# ActuatorBoard.net
KiCad netlist of a schematic drawn in EAGLE
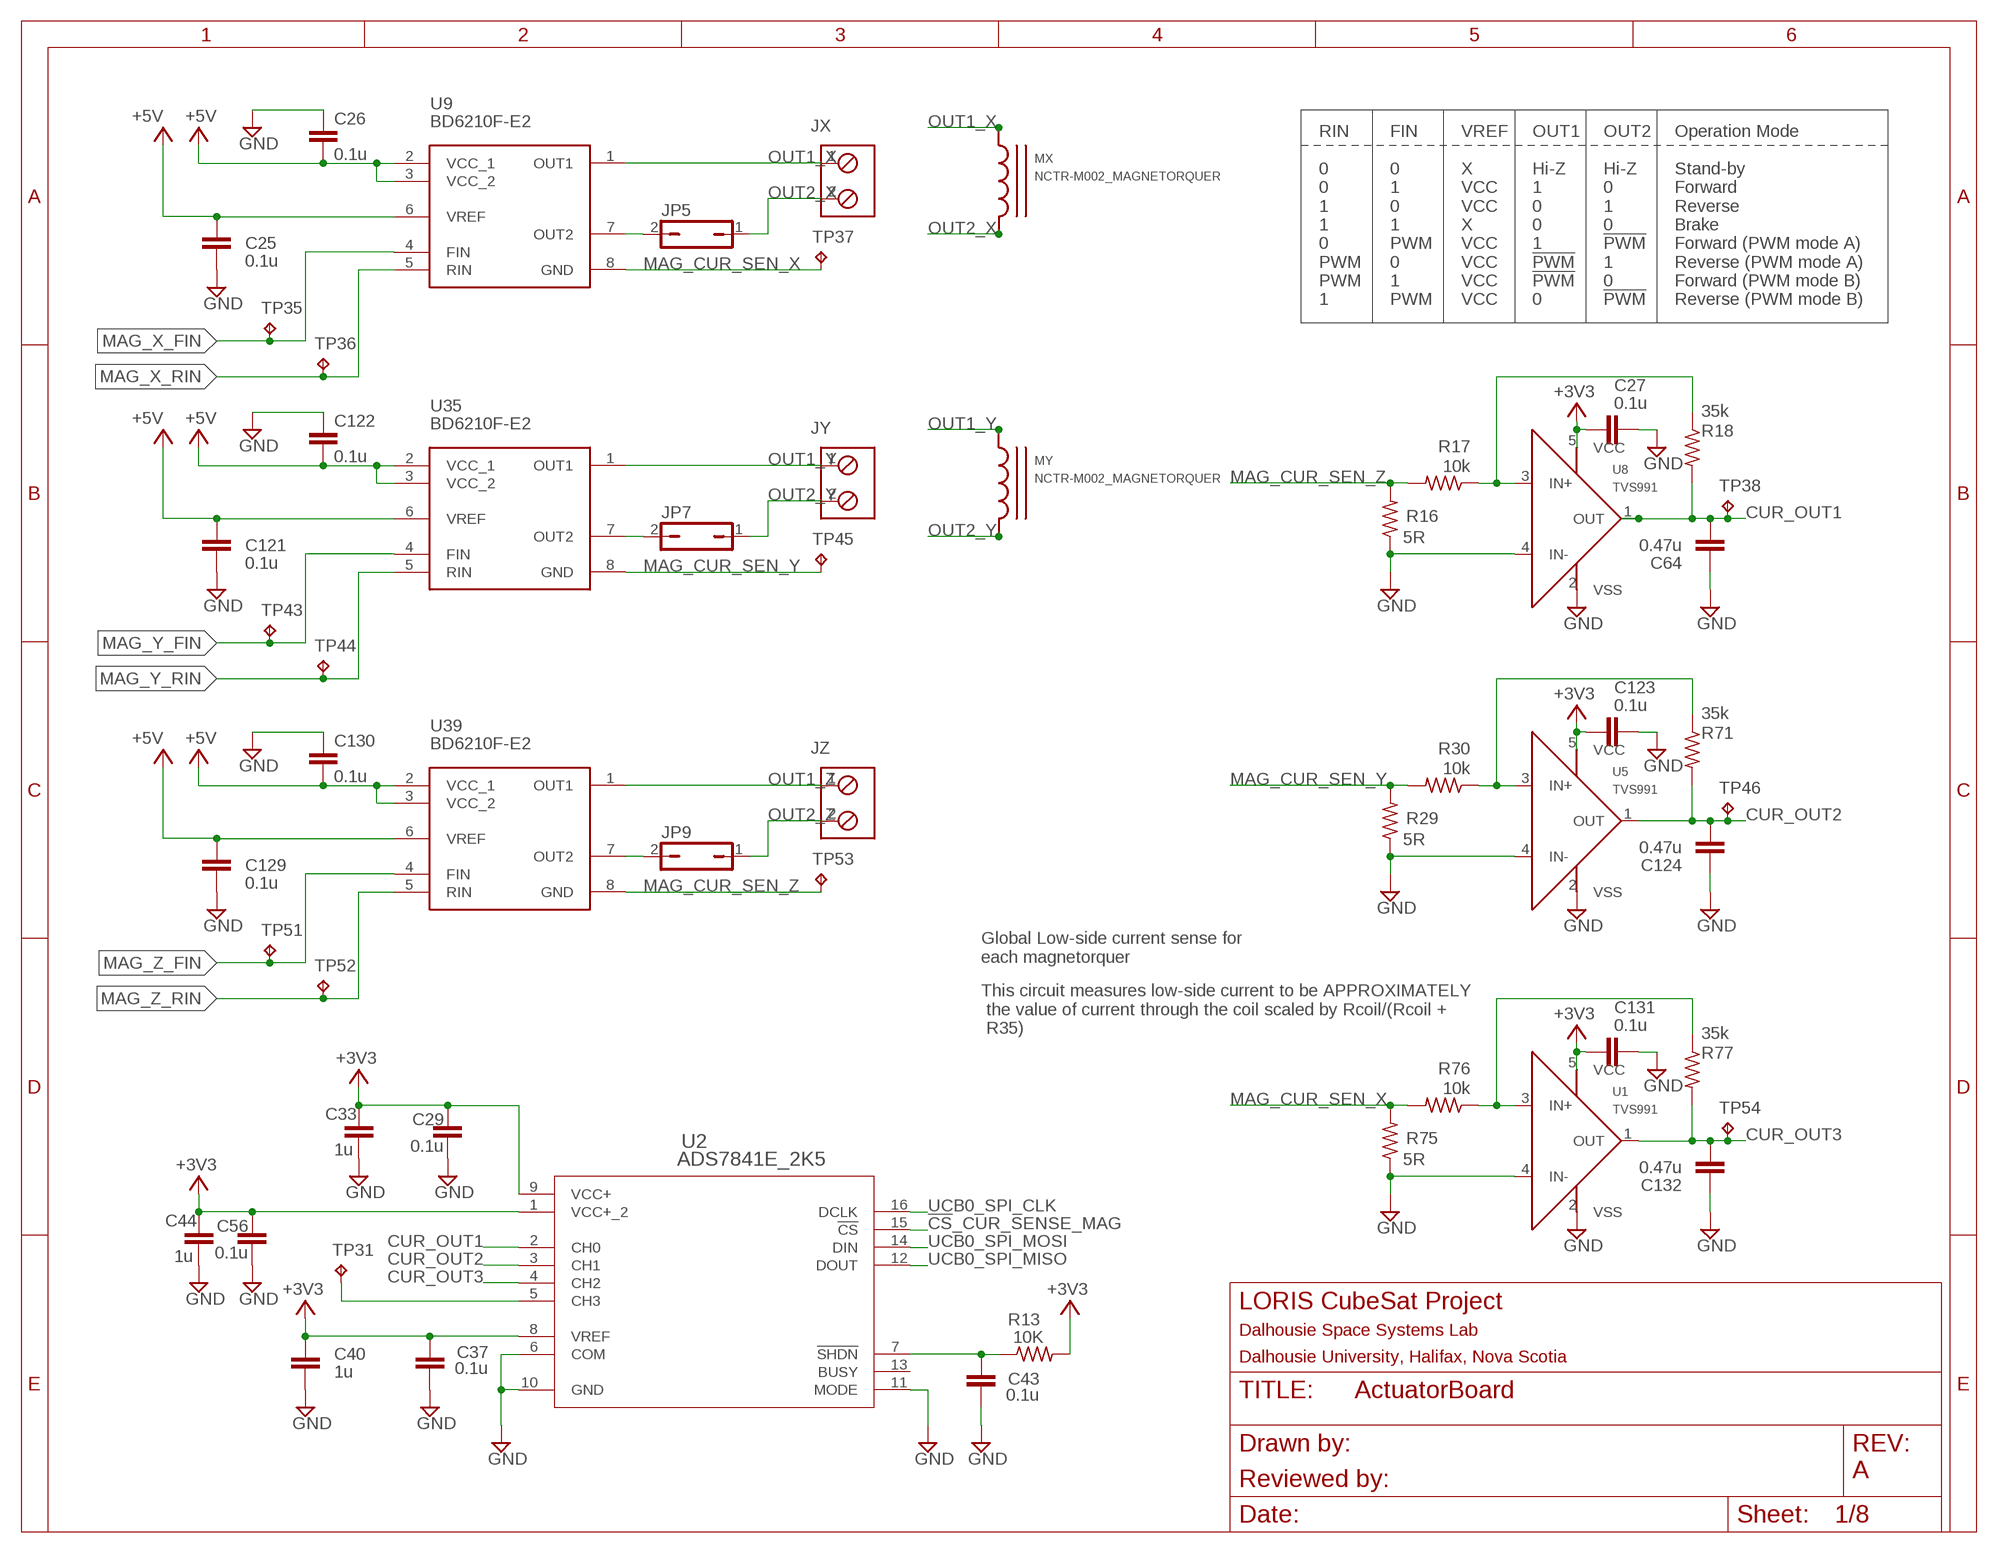
[diagram p0: schematic, sheet 1]
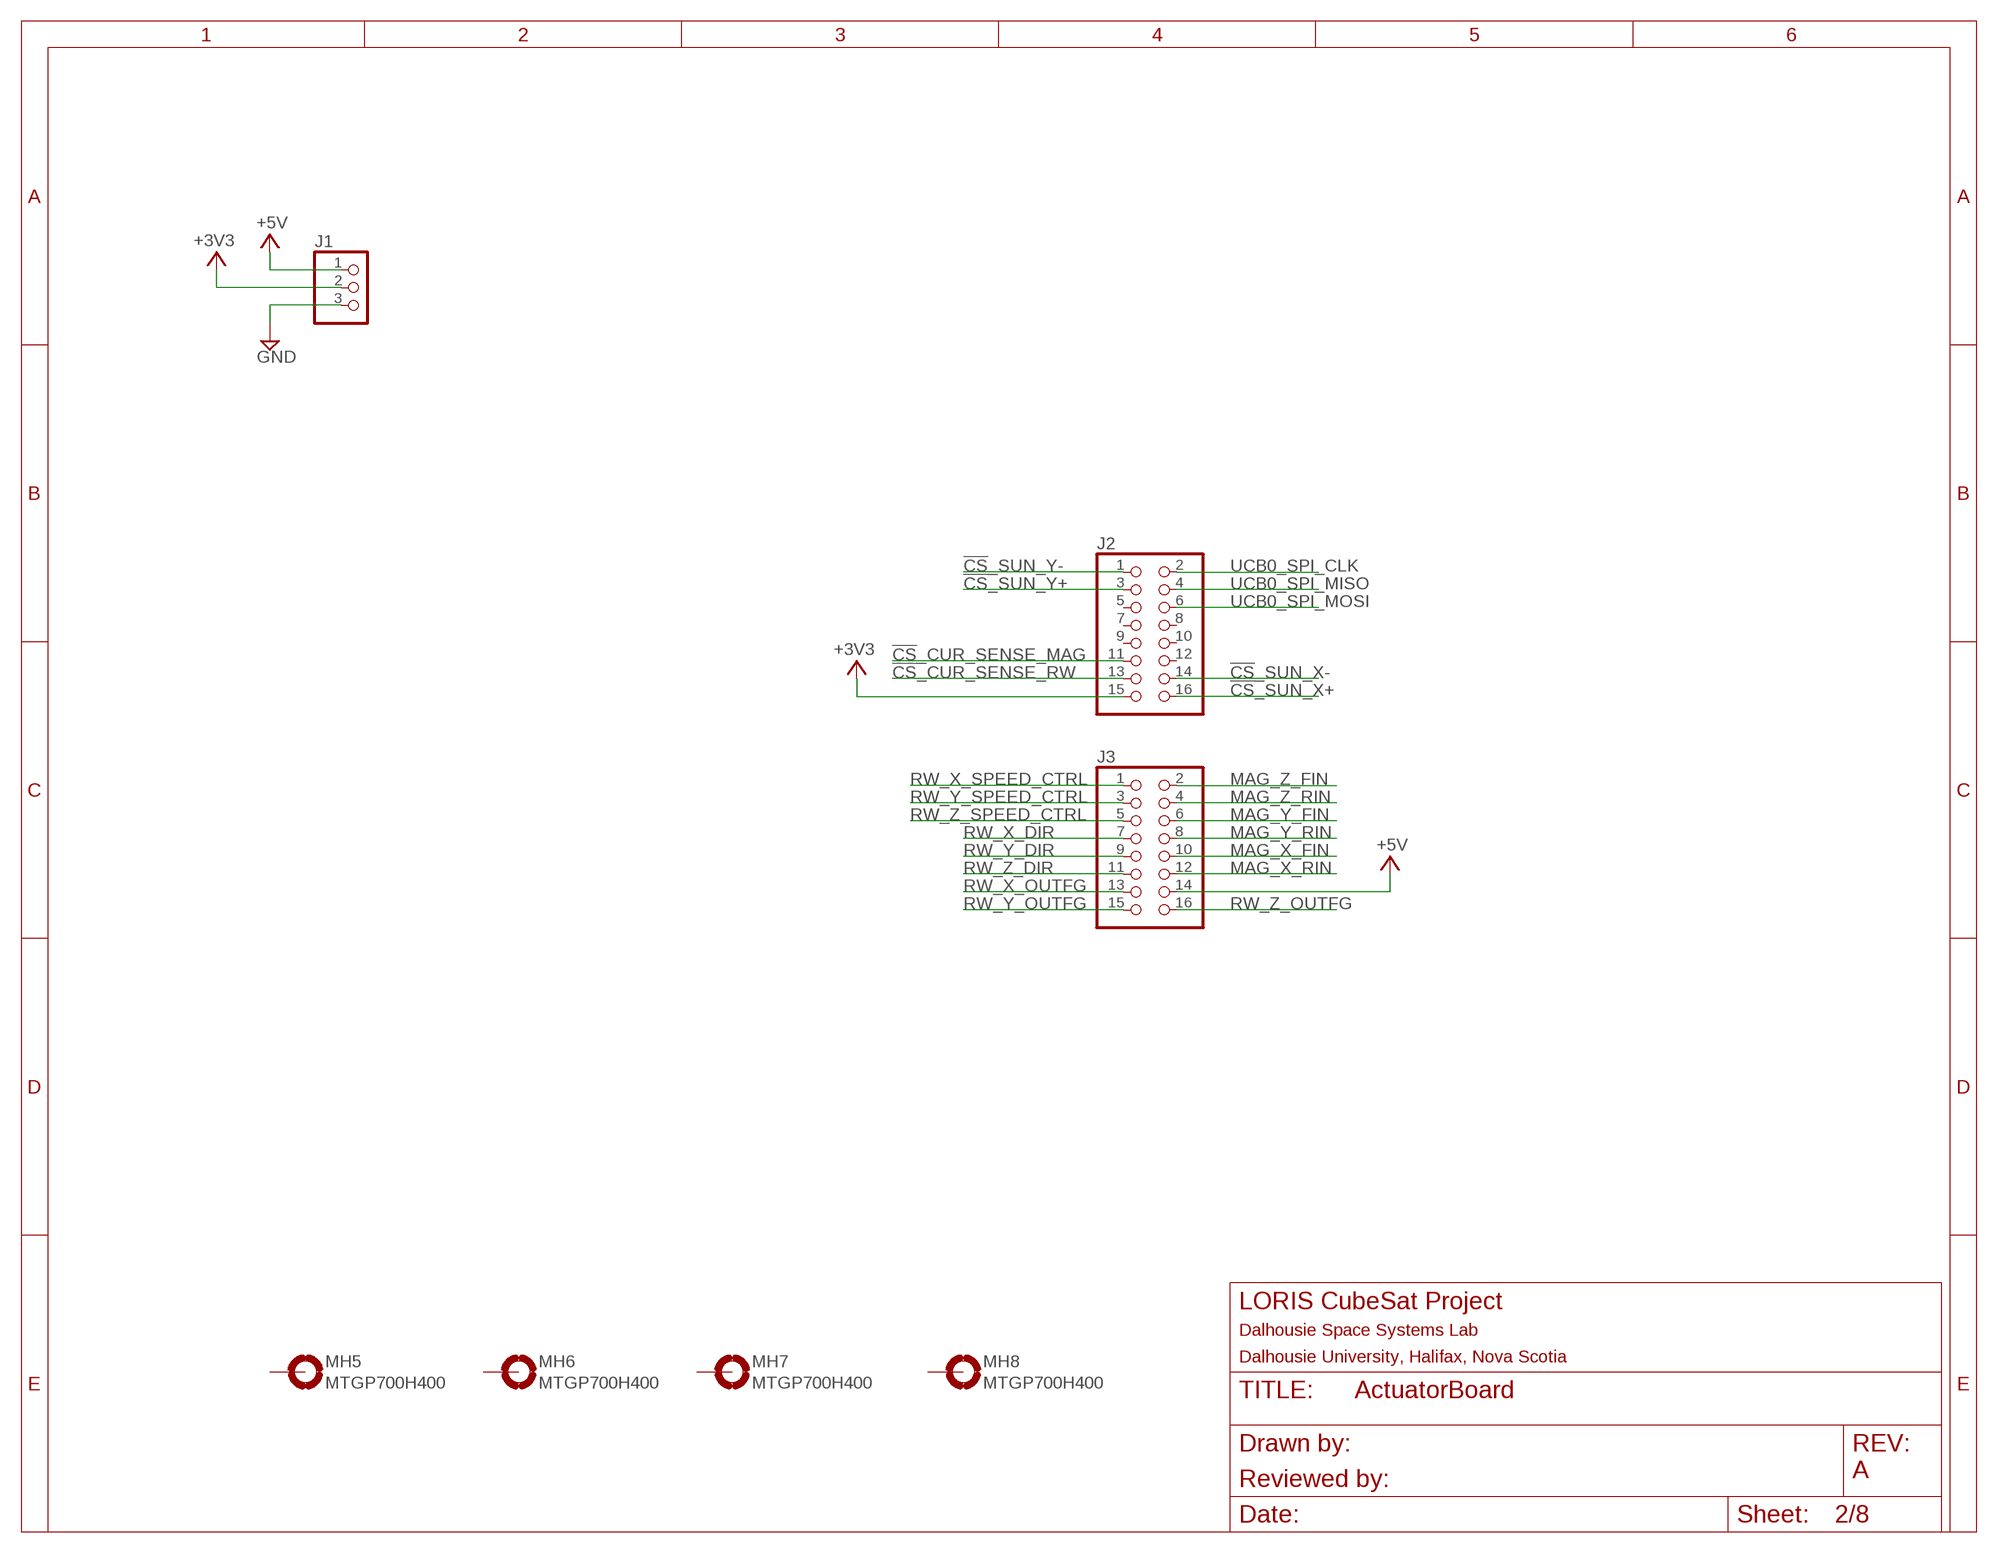
[diagram p1: schematic, sheet 2]
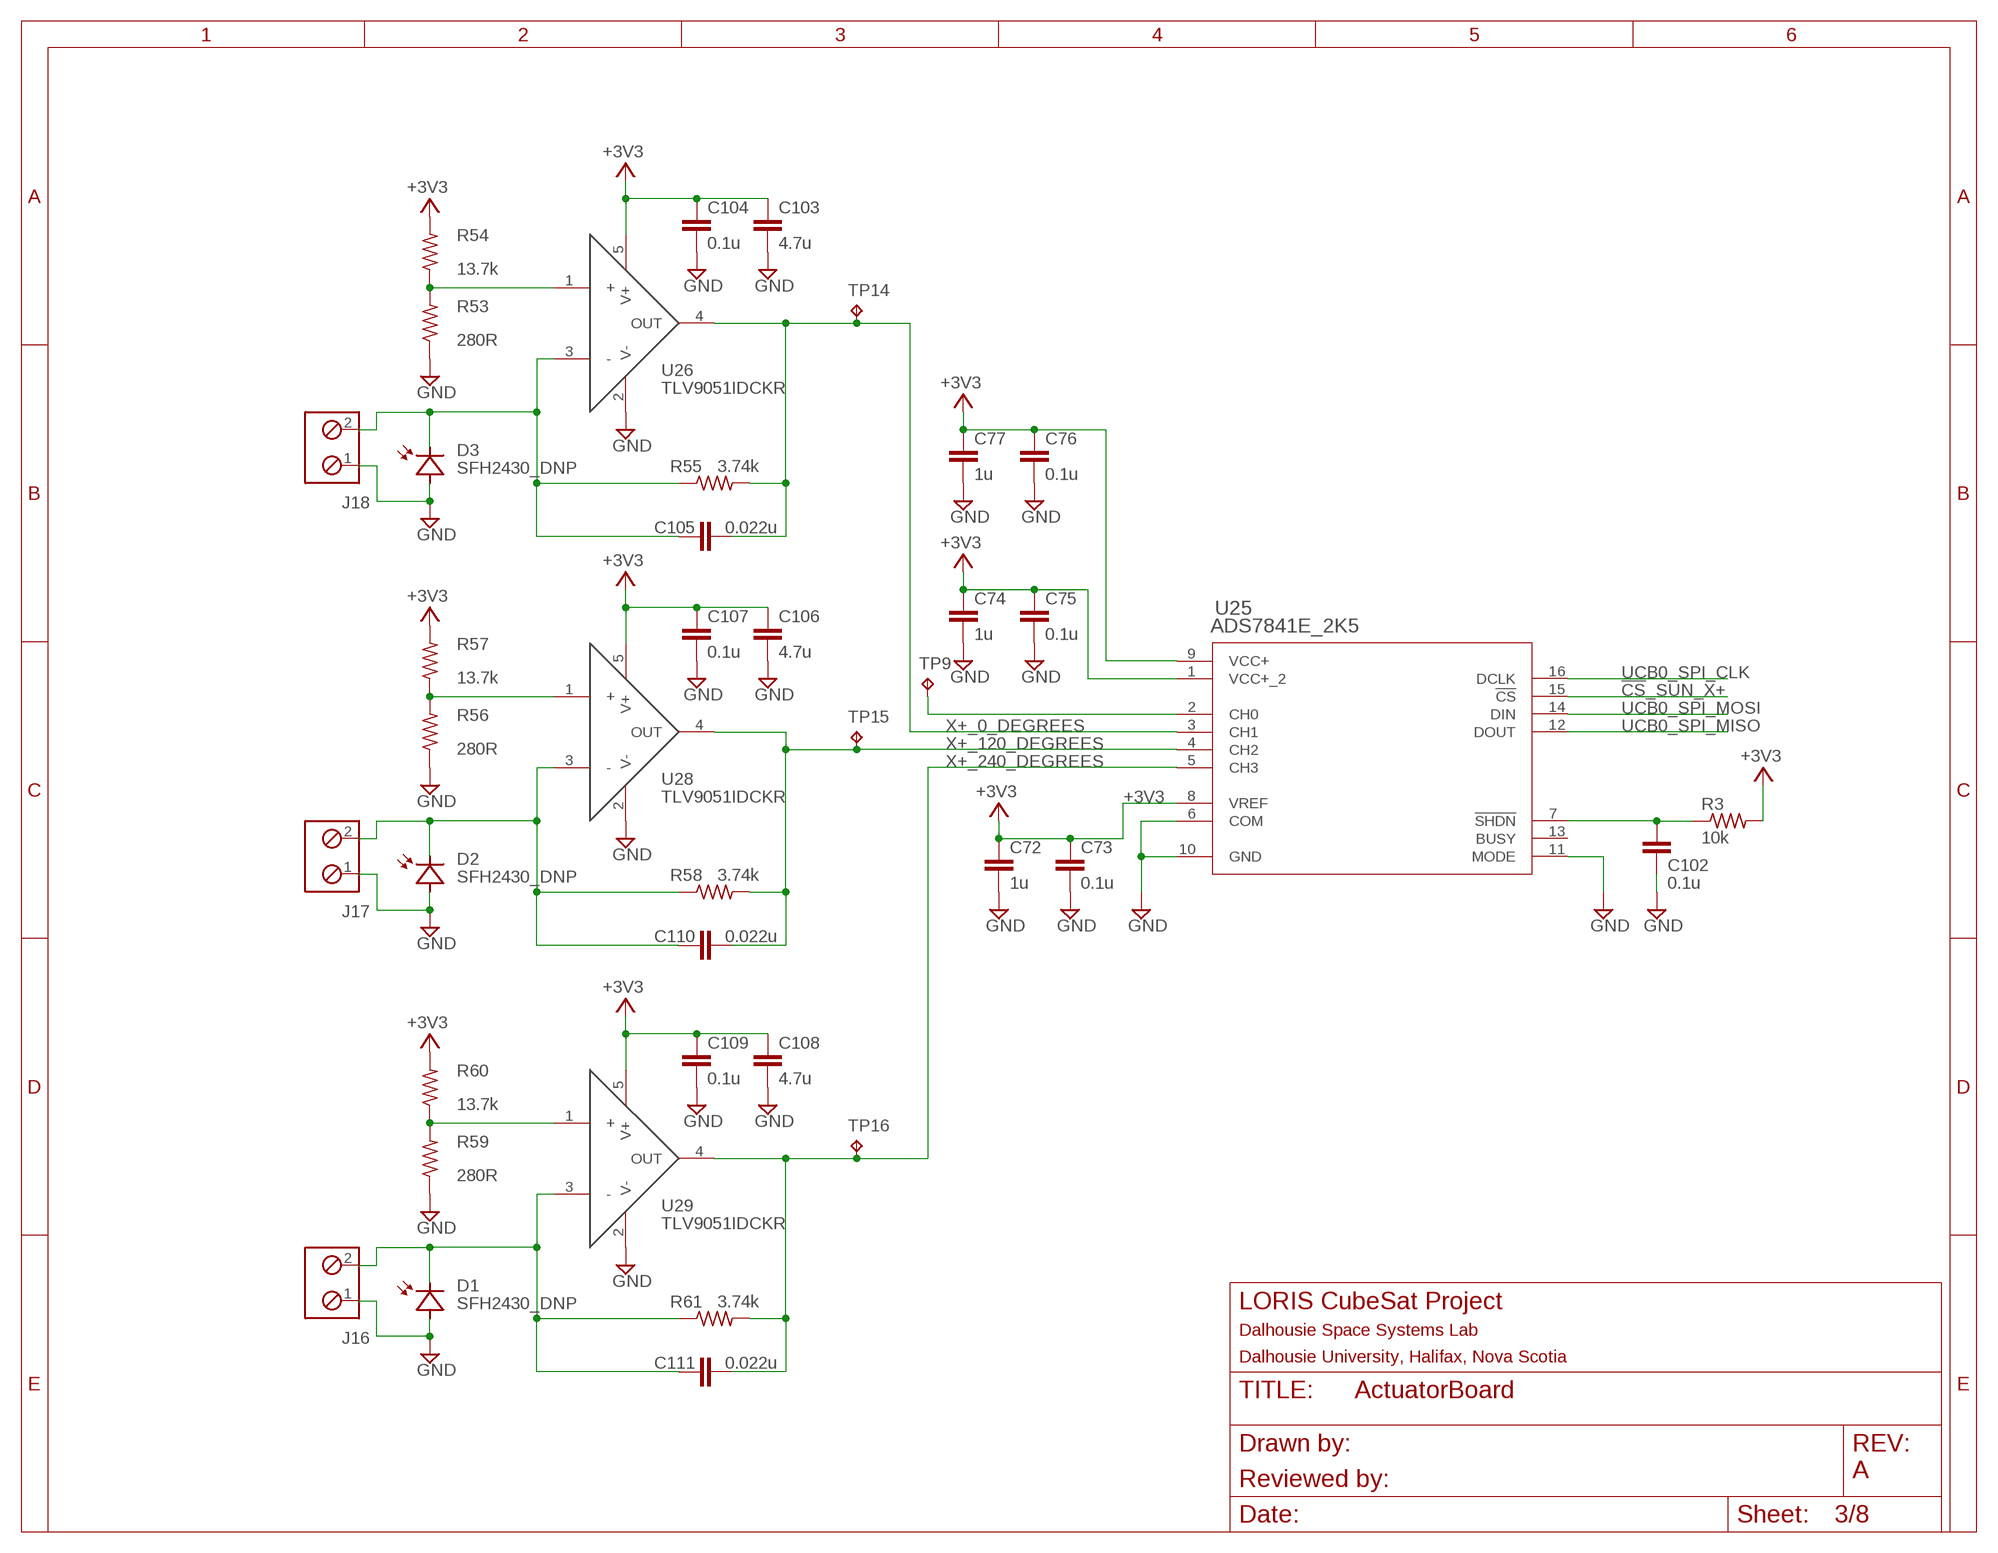
[diagram p2: schematic, sheet 3]
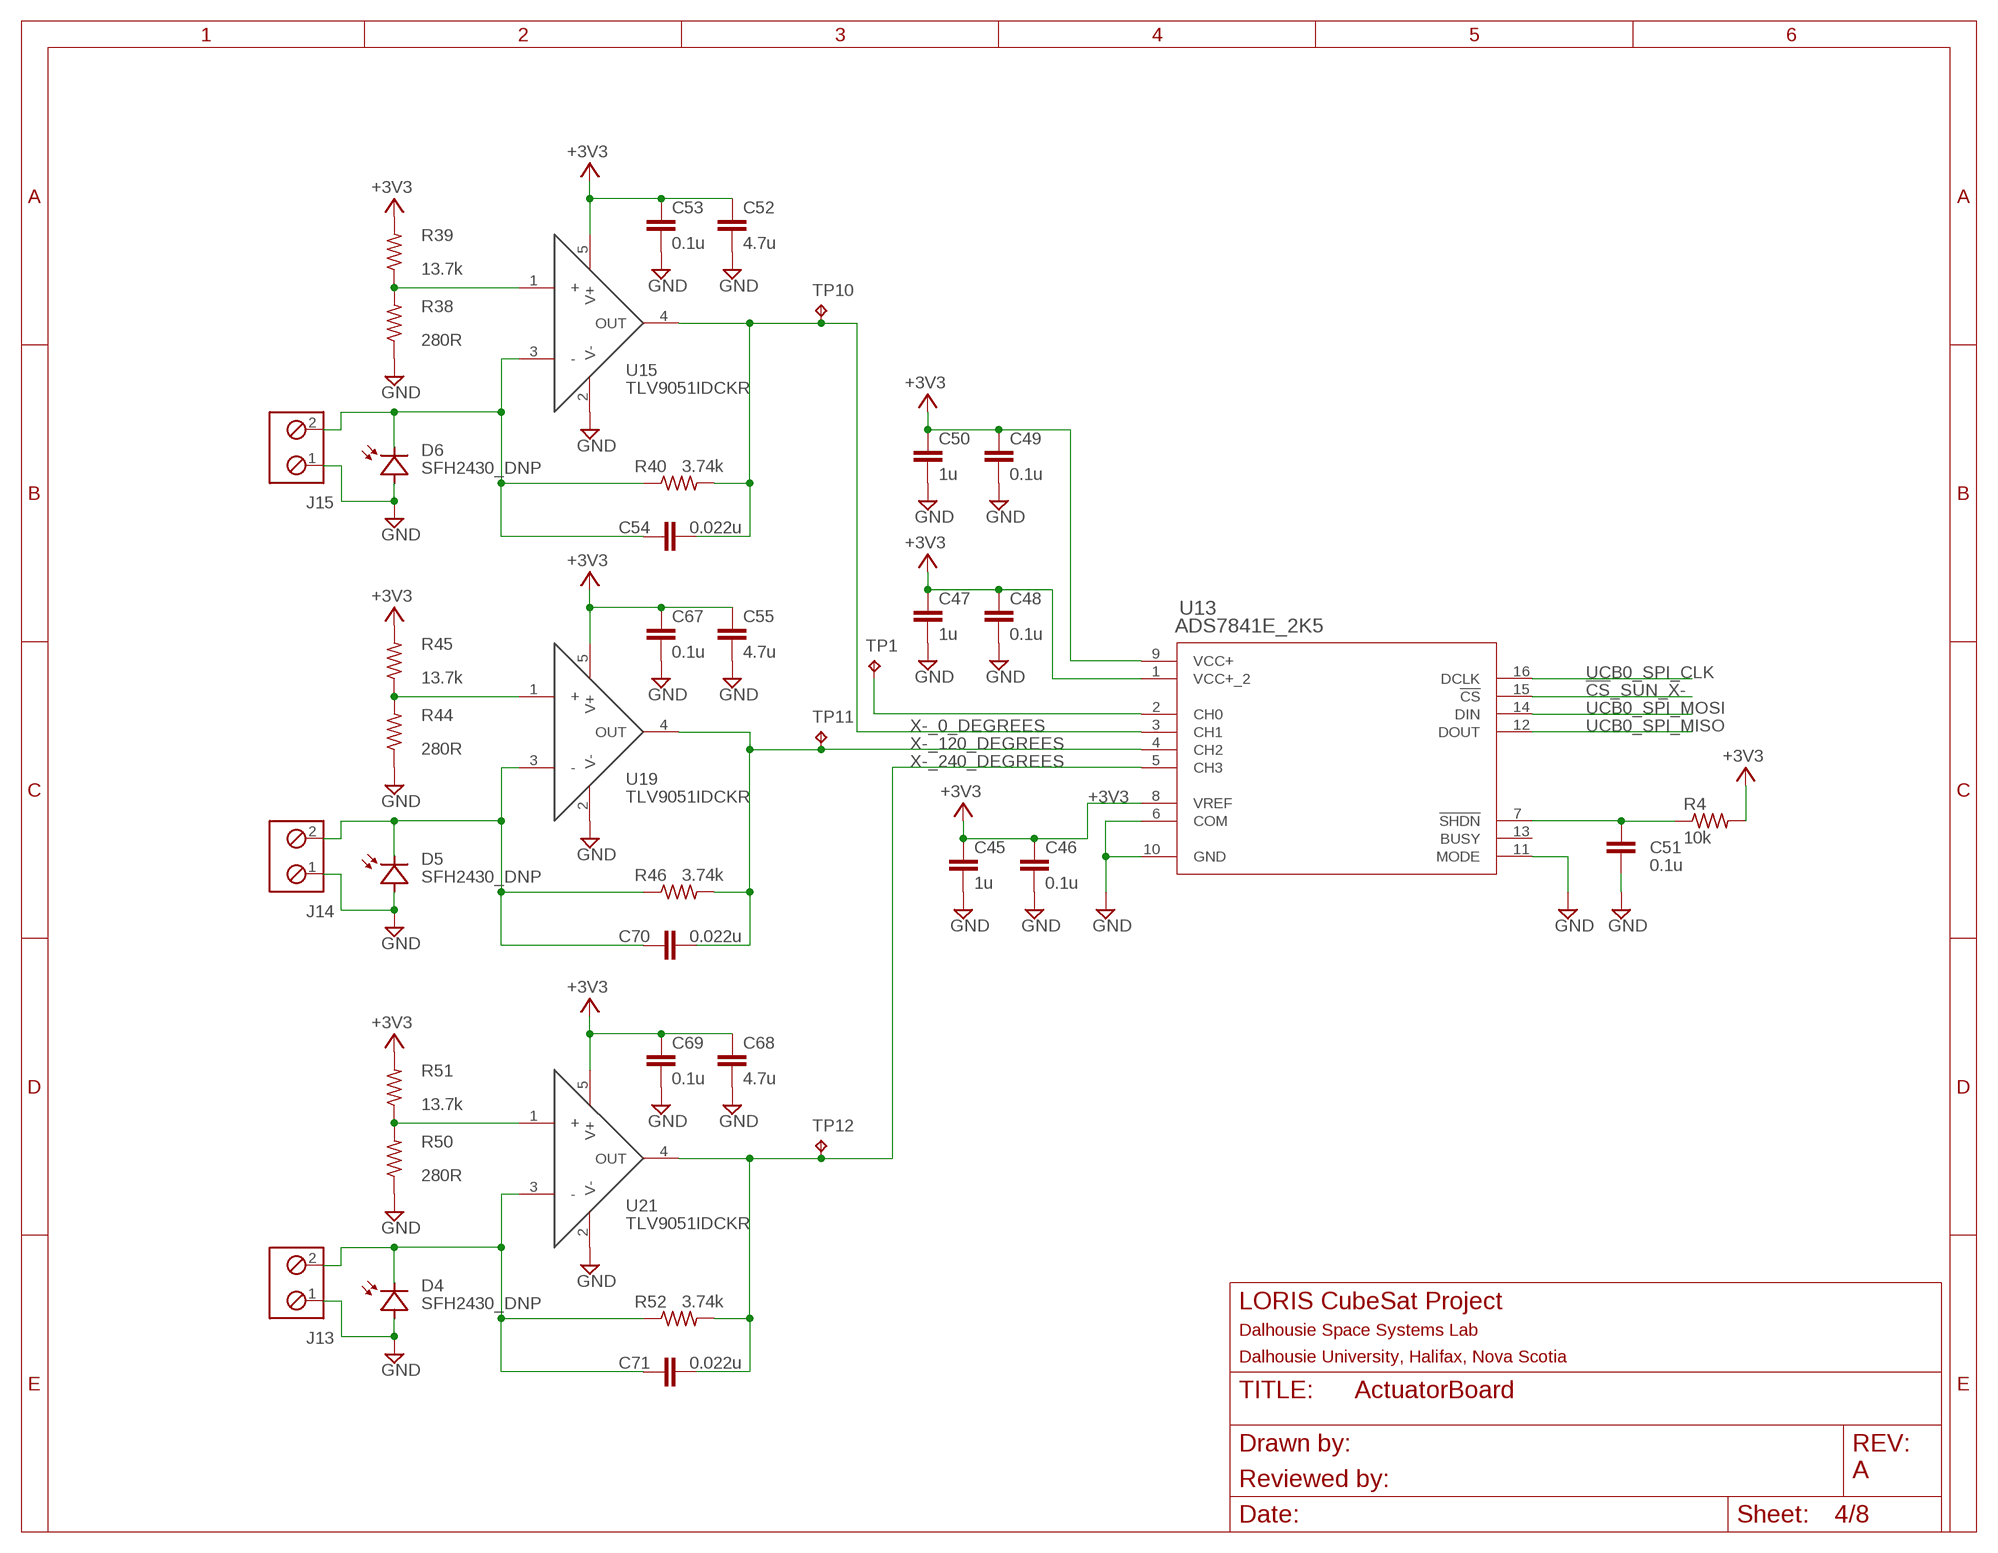
[diagram p3: schematic, sheet 4]
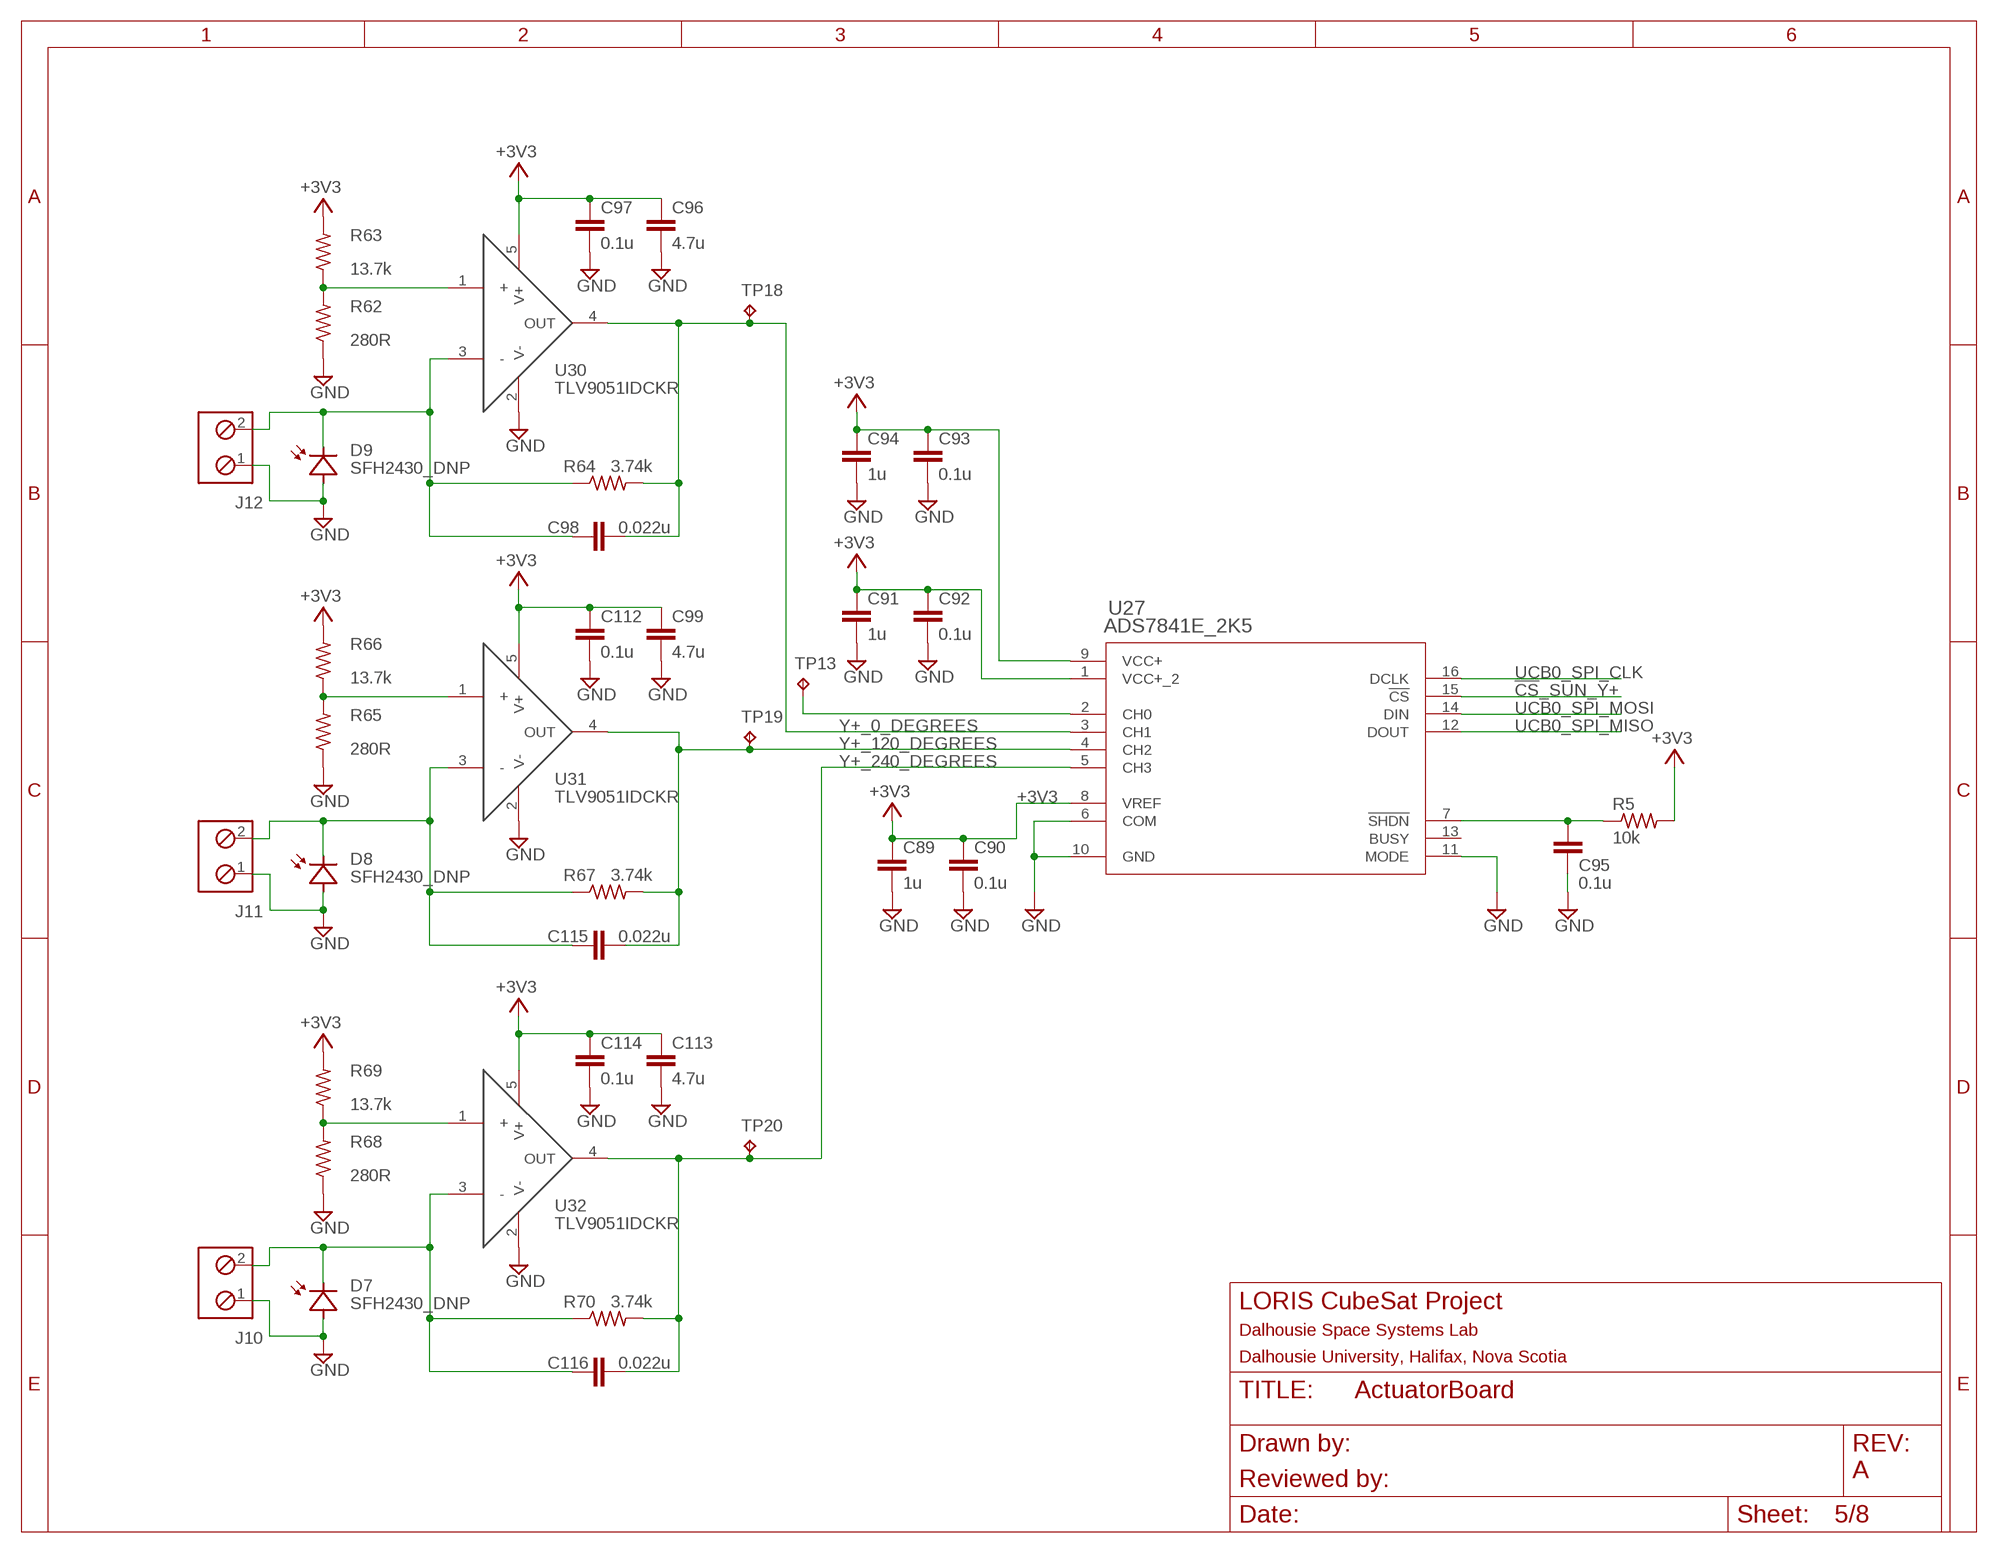
[diagram p4: schematic, sheet 5]
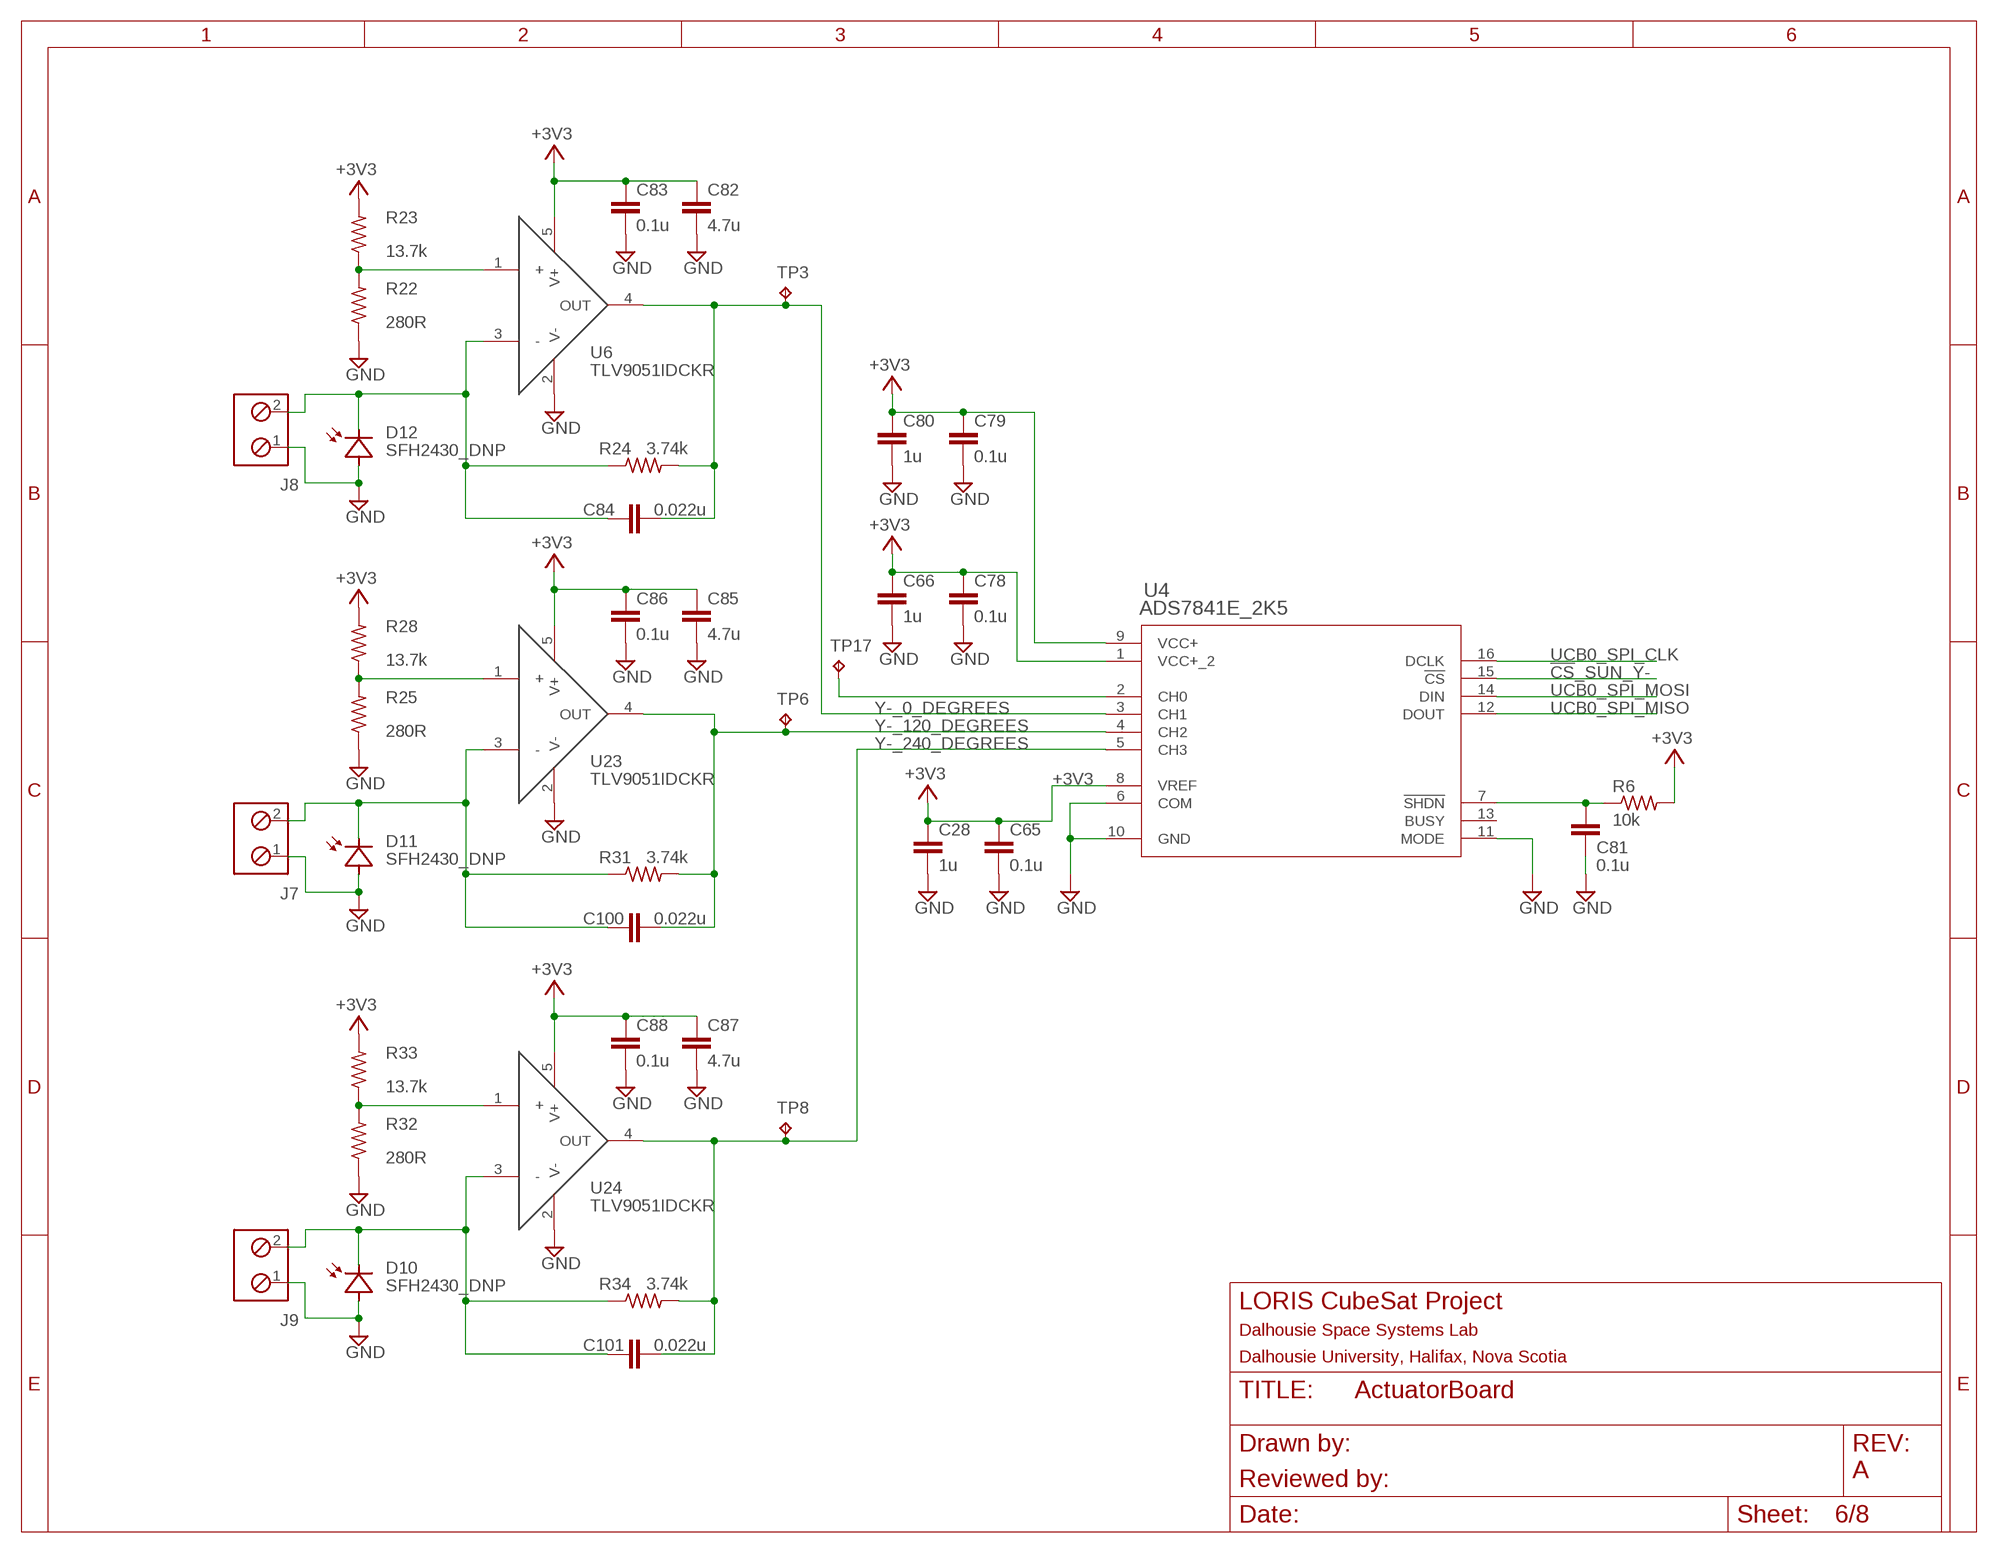
[diagram p5: schematic, sheet 6]
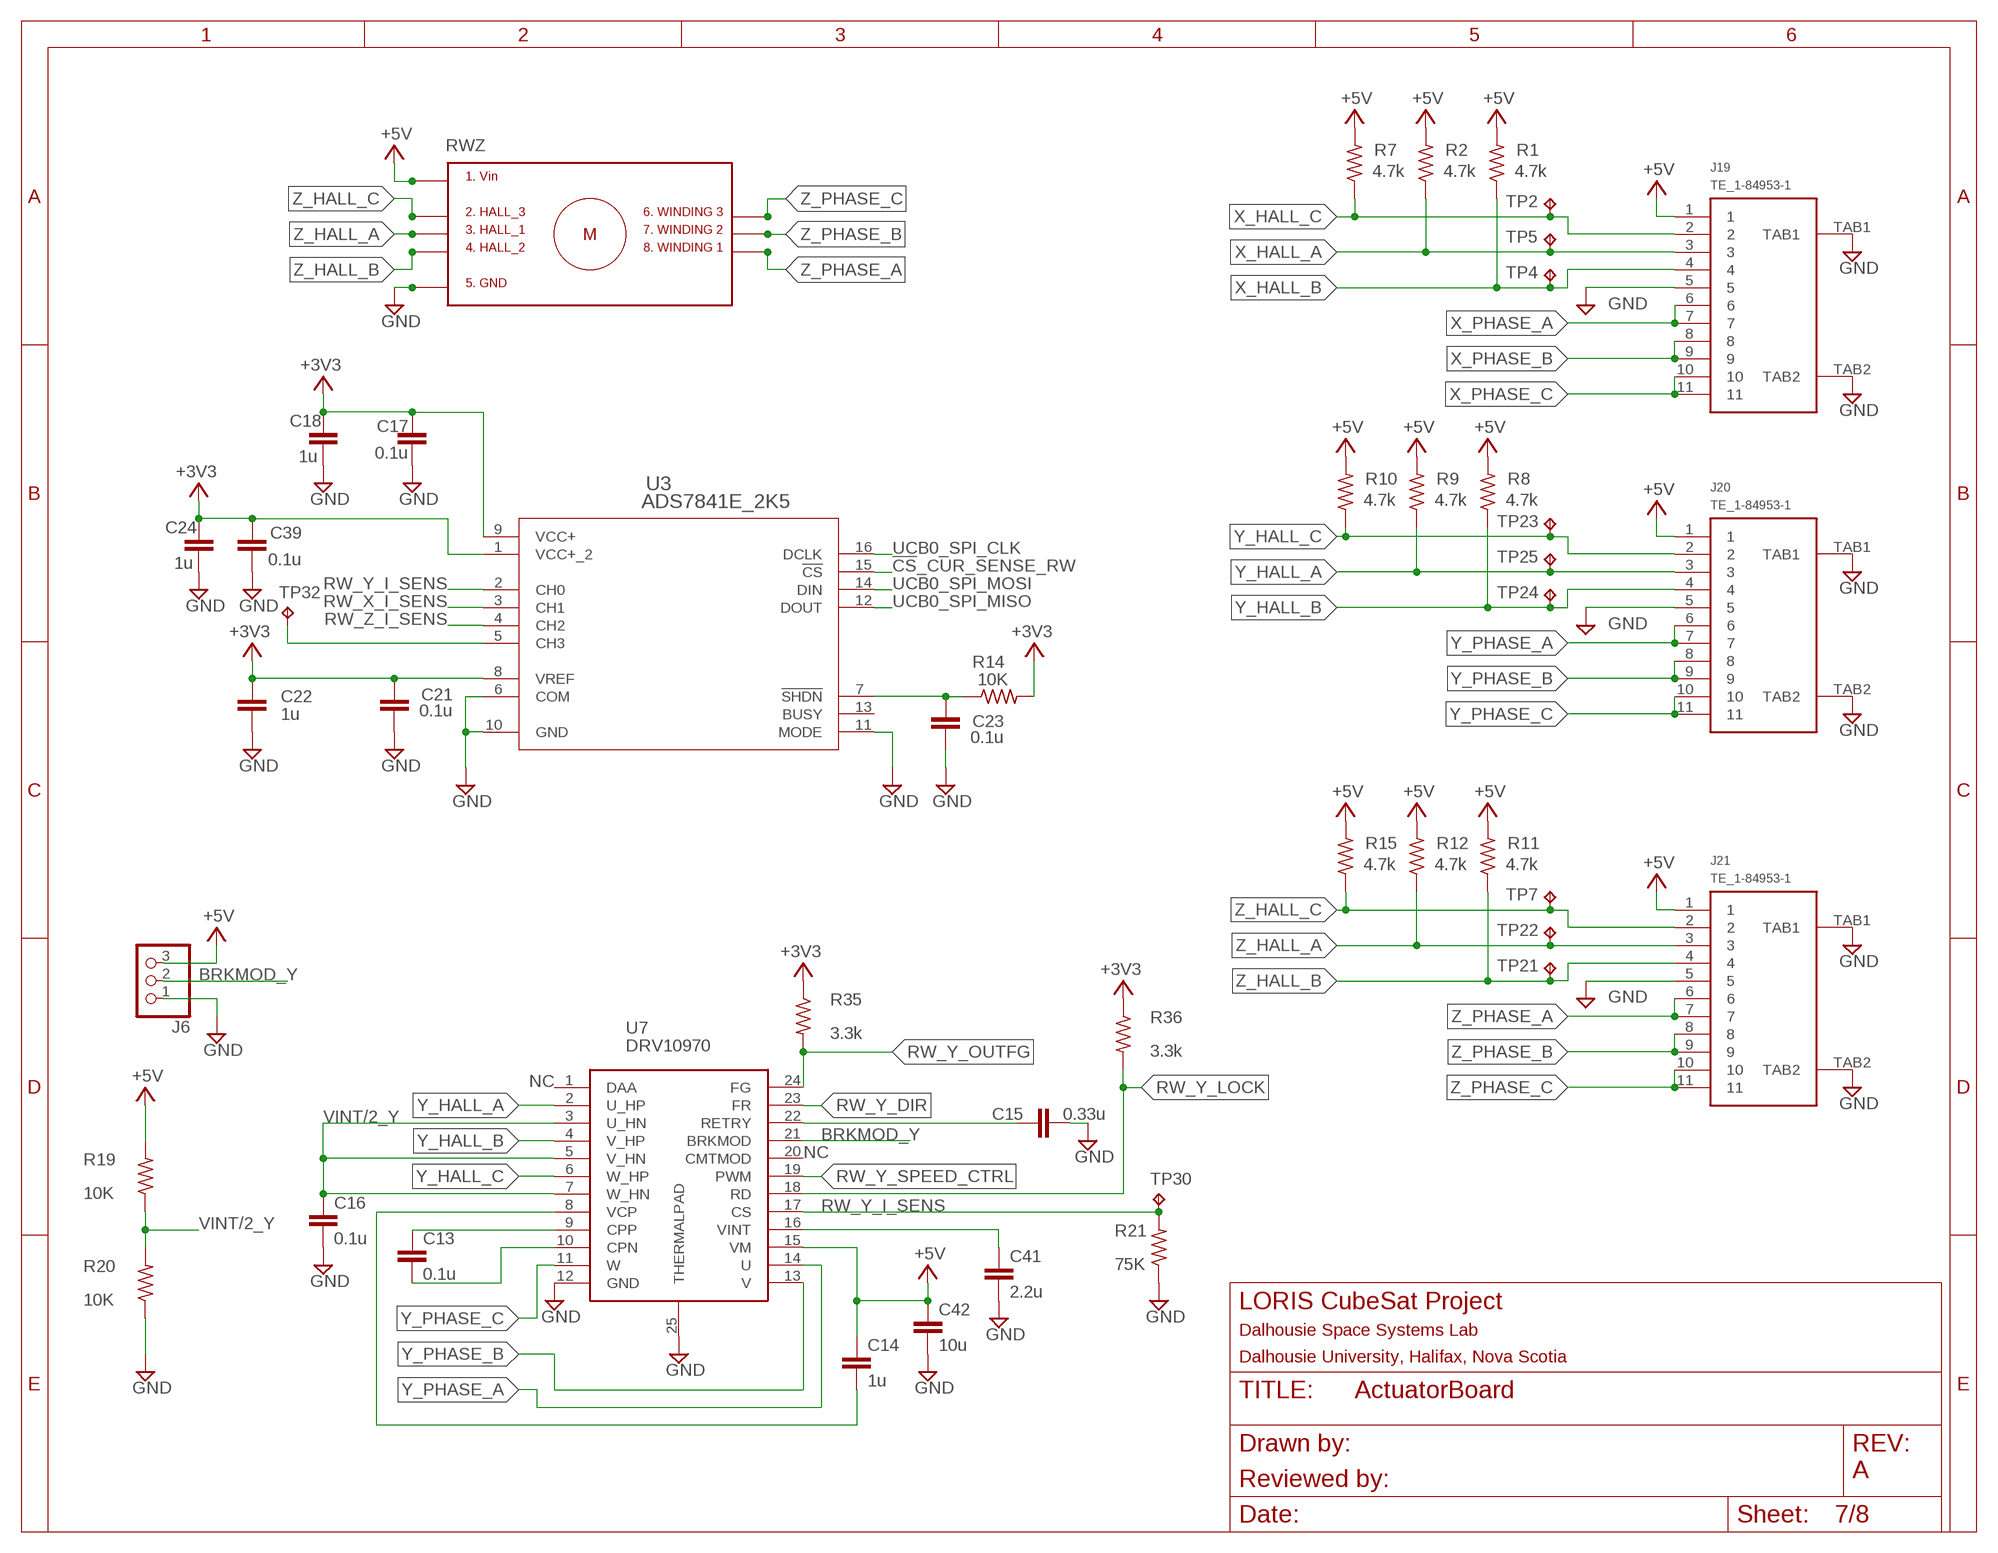
[diagram p6: schematic, sheet 7]
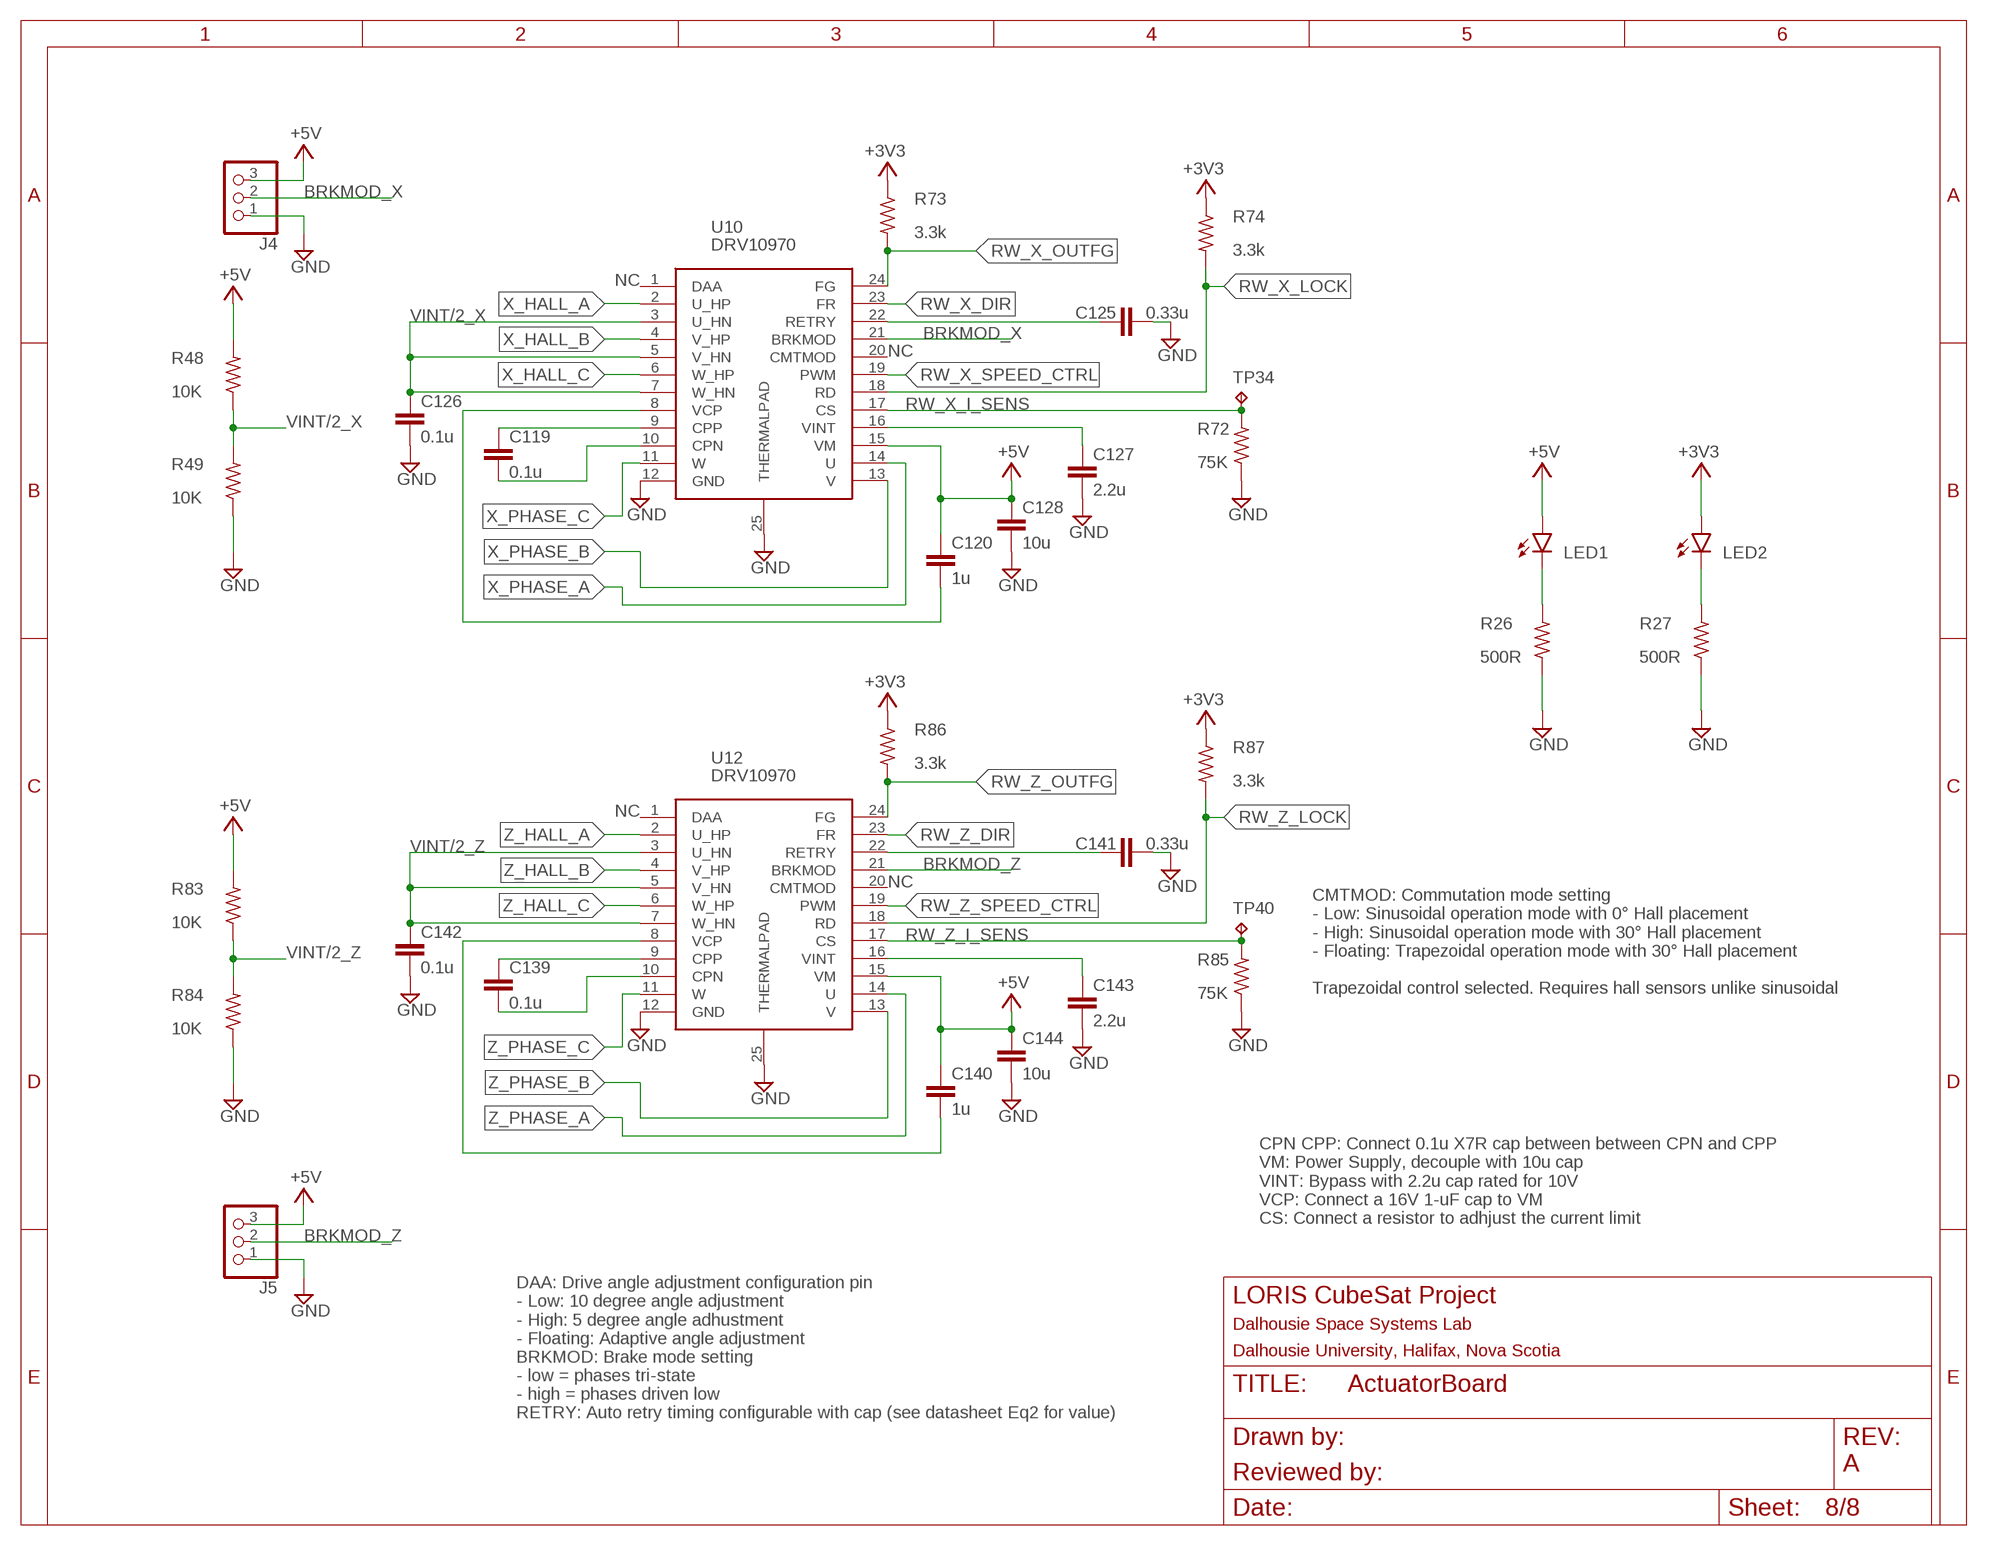
[diagram p7: schematic, sheet 8]

(export (version "E")
  (design (tool "Eeschema 10.0.6"))
  (components
    (comp (ref "C45")
      (value "1u")
      (footprint "eagle-import:C0402")
      (libsource (lib "eagle-import") (part "resistor_348_C-EUC0402"))
    )
    (comp (ref "C46")
      (value "0.1u")
      (footprint "eagle-import:C0402")
      (libsource (lib "eagle-import") (part "resistor_348_C-EUC0402"))
    )
    (comp (ref "C47")
      (value "1u")
      (footprint "eagle-import:C0402")
      (libsource (lib "eagle-import") (part "resistor_348_C-EUC0402"))
    )
    (comp (ref "C48")
      (value "0.1u")
      (footprint "eagle-import:C0402")
      (libsource (lib "eagle-import") (part "resistor_348_C-EUC0402"))
    )
    (comp (ref "C49")
      (value "0.1u")
      (footprint "eagle-import:C0402")
      (libsource (lib "eagle-import") (part "resistor_348_C-EUC0402"))
    )
    (comp (ref "C50")
      (value "1u")
      (footprint "eagle-import:C0402")
      (libsource (lib "eagle-import") (part "resistor_348_C-EUC0402"))
    )
    (comp (ref "C51")
      (value "0.1u")
      (footprint "eagle-import:C0402")
      (libsource (lib "eagle-import") (part "resistor_348_C-EUC0402"))
    )
    (comp (ref "C52")
      (value "4.7u")
      (footprint "eagle-import:C0402")
      (libsource (lib "eagle-import") (part "resistor_348_C-EUC0402"))
    )
    (comp (ref "C53")
      (value "0.1u")
      (footprint "eagle-import:C0402")
      (libsource (lib "eagle-import") (part "resistor_348_C-EUC0402"))
    )
    (comp (ref "C54")
      (value "0.022u")
      (footprint "eagle-import:C0402")
      (libsource (lib "eagle-import") (part "resistor_348_C-EUC0402"))
    )
    (comp (ref "C55")
      (value "4.7u")
      (footprint "eagle-import:C0402")
      (libsource (lib "eagle-import") (part "resistor_348_C-EUC0402"))
    )
    (comp (ref "C67")
      (value "0.1u")
      (footprint "eagle-import:C0402")
      (libsource (lib "eagle-import") (part "resistor_348_C-EUC0402"))
    )
    (comp (ref "C68")
      (value "4.7u")
      (footprint "eagle-import:C0402")
      (libsource (lib "eagle-import") (part "resistor_348_C-EUC0402"))
    )
    (comp (ref "C69")
      (value "0.1u")
      (footprint "eagle-import:C0402")
      (libsource (lib "eagle-import") (part "resistor_348_C-EUC0402"))
    )
    (comp (ref "C70")
      (value "0.022u")
      (footprint "eagle-import:C0402")
      (libsource (lib "eagle-import") (part "resistor_348_C-EUC0402"))
    )
    (comp (ref "C71")
      (value "0.022u")
      (footprint "eagle-import:C0402")
      (libsource (lib "eagle-import") (part "resistor_348_C-EUC0402"))
    )
    (comp (ref "J13")
      (value "TRM_BLK_1X2")
      (footprint "eagle-import:2POL254")
      (libsource (lib "eagle-import") (part "TRM_BLK_1X2"))
    )
    (comp (ref "J14")
      (value "TRM_BLK_1X2")
      (footprint "eagle-import:2POL254")
      (libsource (lib "eagle-import") (part "TRM_BLK_1X2"))
    )
    (comp (ref "J15")
      (value "TRM_BLK_1X2")
      (footprint "eagle-import:2POL254")
      (libsource (lib "eagle-import") (part "TRM_BLK_1X2"))
    )
    (comp (ref "R4")
      (value "10k")
      (footprint "eagle-import:R0402")
      (libsource (lib "eagle-import") (part "R-US_R0402"))
    )
    (comp (ref "R38")
      (value "280R")
      (footprint "eagle-import:R0402")
      (libsource (lib "eagle-import") (part "resistor_348_R-US_R0402"))
    )
    (comp (ref "R39")
      (value "13.7k")
      (footprint "eagle-import:R0402")
      (libsource (lib "eagle-import") (part "resistor_348_R-US_R0402"))
    )
    (comp (ref "R40")
      (value "3.74k")
      (footprint "eagle-import:R0402")
      (libsource (lib "eagle-import") (part "resistor_348_R-US_R0402"))
    )
    (comp (ref "R44")
      (value "280R")
      (footprint "eagle-import:R0402")
      (libsource (lib "eagle-import") (part "resistor_348_R-US_R0402"))
    )
    (comp (ref "R45")
      (value "13.7k")
      (footprint "eagle-import:R0402")
      (libsource (lib "eagle-import") (part "resistor_348_R-US_R0402"))
    )
    (comp (ref "R46")
      (value "3.74k")
      (footprint "eagle-import:R0402")
      (libsource (lib "eagle-import") (part "resistor_348_R-US_R0402"))
    )
    (comp (ref "R50")
      (value "280R")
      (footprint "eagle-import:R0402")
      (libsource (lib "eagle-import") (part "resistor_348_R-US_R0402"))
    )
    (comp (ref "R51")
      (value "13.7k")
      (footprint "eagle-import:R0402")
      (libsource (lib "eagle-import") (part "resistor_348_R-US_R0402"))
    )
    (comp (ref "R52")
      (value "3.74k")
      (footprint "eagle-import:R0402")
      (libsource (lib "eagle-import") (part "resistor_348_R-US_R0402"))
    )
    (comp (ref "TP1")
      (value "TESTPOINT")
      (footprint "eagle-import:TP_P76H50")
      (libsource (lib "eagle-import") (part "TESTPOINT"))
    )
    (comp (ref "TP10")
      (value "TESTPOINT")
      (footprint "eagle-import:TP_P76H50")
      (libsource (lib "eagle-import") (part "TESTPOINT"))
    )
    (comp (ref "TP11")
      (value "TESTPOINT")
      (footprint "eagle-import:TP_P76H50")
      (libsource (lib "eagle-import") (part "TESTPOINT"))
    )
    (comp (ref "TP12")
      (value "TESTPOINT")
      (footprint "eagle-import:TP_P76H50")
      (libsource (lib "eagle-import") (part "TESTPOINT"))
    )
    (comp (ref "U13")
      (value "ADS7841E_2K5")
      (footprint "eagle-import:DBQ16")
      (fields
        (field (name "GENERIC_PART_NUMBER") "ADS7841")
        (field (name "MANUFACTURER") "Texas Instruments")
      )
      (libsource (lib "eagle-import") (part "ADS7841E_2K5"))
    )
    (comp (ref "U15")
      (value "TLV9051IDCKR")
      (footprint "eagle-import:SC70-5P65_210X110L36X22N_TLV9051")
      (libsource (lib "eagle-import") (part "TLV9051IDCKR"))
    )
    (comp (ref "U19")
      (value "TLV9051IDCKR")
      (footprint "eagle-import:SC70-5P65_210X110L36X22N_TLV9051")
      (libsource (lib "eagle-import") (part "TLV9051IDCKR"))
    )
    (comp (ref "U21")
      (value "TLV9051IDCKR")
      (footprint "eagle-import:SC70-5P65_210X110L36X22N_TLV9051")
      (libsource (lib "eagle-import") (part "TLV9051IDCKR"))
    )
    (comp (ref "C13")
      (value "0.1u")
      (footprint "eagle-import:C0603")
      (libsource (lib "eagle-import") (part "C-EUC0603"))
    )
    (comp (ref "C14")
      (value "1u")
      (footprint "eagle-import:C0603")
      (libsource (lib "eagle-import") (part "C-EUC0603"))
    )
    (comp (ref "C15")
      (value "0.33u")
      (footprint "eagle-import:C0603")
      (libsource (lib "eagle-import") (part "C-EUC0603"))
    )
    (comp (ref "C16")
      (value "0.1u")
      (footprint "eagle-import:C0603")
      (libsource (lib "eagle-import") (part "C-EUC0603"))
    )
    (comp (ref "C17")
      (value "0.1u")
      (footprint "eagle-import:C0402")
      (libsource (lib "eagle-import") (part "C-EUC0402"))
    )
    (comp (ref "C18")
      (value "1u")
      (footprint "eagle-import:C0402")
      (libsource (lib "eagle-import") (part "C-EUC0402"))
    )
    (comp (ref "C21")
      (value "0.1u")
      (footprint "eagle-import:C0402")
      (libsource (lib "eagle-import") (part "C-EUC0402"))
    )
    (comp (ref "C22")
      (value "1u")
      (footprint "eagle-import:C0402")
      (libsource (lib "eagle-import") (part "C-EUC0402"))
    )
    (comp (ref "C23")
      (value "0.1u")
      (footprint "eagle-import:C0402")
      (libsource (lib "eagle-import") (part "C-EUC0402"))
    )
    (comp (ref "C24")
      (value "1u")
      (footprint "eagle-import:C0402")
      (libsource (lib "eagle-import") (part "C-EUC0402"))
    )
    (comp (ref "C39")
      (value "0.1u")
      (footprint "eagle-import:C0402")
      (libsource (lib "eagle-import") (part "C-EUC0402"))
    )
    (comp (ref "C41")
      (value "2.2u")
      (footprint "eagle-import:C0603")
      (libsource (lib "eagle-import") (part "C-EUC0603"))
    )
    (comp (ref "C42")
      (value "10u")
      (footprint "eagle-import:C0603")
      (libsource (lib "eagle-import") (part "C-EUC0603"))
    )
    (comp (ref "J6")
      (value "PINHD-1X3")
      (footprint "eagle-import:1X03")
      (libsource (lib "eagle-import") (part "PINHD-1X3"))
    )
    (comp (ref "J19")
      (value "TE_1-84953-1")
      (footprint "eagle-import:TE_1-84953-1")
      (libsource (lib "eagle-import") (part "TE_1-84953-1"))
    )
    (comp (ref "J20")
      (value "TE_1-84953-1")
      (footprint "eagle-import:TE_1-84953-1")
      (libsource (lib "eagle-import") (part "TE_1-84953-1"))
    )
    (comp (ref "J21")
      (value "TE_1-84953-1")
      (footprint "eagle-import:TE_1-84953-1")
      (libsource (lib "eagle-import") (part "TE_1-84953-1"))
    )
    (comp (ref "R1")
      (value "4.7k")
      (footprint "eagle-import:R0402")
      (libsource (lib "eagle-import") (part "R-US_R0402"))
    )
    (comp (ref "R2")
      (value "4.7k")
      (footprint "eagle-import:R0402")
      (libsource (lib "eagle-import") (part "R-US_R0402"))
    )
    (comp (ref "R7")
      (value "4.7k")
      (footprint "eagle-import:R0402")
      (libsource (lib "eagle-import") (part "R-US_R0402"))
    )
    (comp (ref "R8")
      (value "4.7k")
      (footprint "eagle-import:R0402")
      (libsource (lib "eagle-import") (part "R-US_R0402"))
    )
    (comp (ref "R9")
      (value "4.7k")
      (footprint "eagle-import:R0402")
      (libsource (lib "eagle-import") (part "R-US_R0402"))
    )
    (comp (ref "R10")
      (value "4.7k")
      (footprint "eagle-import:R0402")
      (libsource (lib "eagle-import") (part "R-US_R0402"))
    )
    (comp (ref "R11")
      (value "4.7k")
      (footprint "eagle-import:R0402")
      (libsource (lib "eagle-import") (part "R-US_R0402"))
    )
    (comp (ref "R12")
      (value "4.7k")
      (footprint "eagle-import:R0402")
      (libsource (lib "eagle-import") (part "R-US_R0402"))
    )
    (comp (ref "R14")
      (value "10K")
      (footprint "eagle-import:R0402")
      (libsource (lib "eagle-import") (part "R-US_R0402"))
    )
    (comp (ref "R15")
      (value "4.7k")
      (footprint "eagle-import:R0402")
      (libsource (lib "eagle-import") (part "R-US_R0402"))
    )
    (comp (ref "R19")
      (value "10K")
      (footprint "eagle-import:R0603")
      (libsource (lib "eagle-import") (part "R-US_R0603"))
    )
    (comp (ref "R20")
      (value "10K")
      (footprint "eagle-import:R0603")
      (libsource (lib "eagle-import") (part "R-US_R0603"))
    )
    (comp (ref "R21")
      (value "75K")
      (footprint "eagle-import:R0603")
      (libsource (lib "eagle-import") (part "R-US_R0603"))
    )
    (comp (ref "R35")
      (value "3.3k")
      (footprint "eagle-import:R0603")
      (libsource (lib "eagle-import") (part "R-US_R0603"))
    )
    (comp (ref "R36")
      (value "3.3k")
      (footprint "eagle-import:R0603")
      (libsource (lib "eagle-import") (part "R-US_R0603"))
    )
    (comp (ref "RWZ")
      (value "REACTION_WHEEL_NOPINS_MAXON")
      (footprint "eagle-import:RWA_NOPINS")
      (libsource (lib "eagle-import") (part "REACTION_WHEEL_NOPINS_MAXON"))
    )
    (comp (ref "TP2")
      (value "TESTPOINT")
      (footprint "eagle-import:TP_P76H50")
      (libsource (lib "eagle-import") (part "TESTPOINT"))
    )
    (comp (ref "TP4")
      (value "TESTPOINT")
      (footprint "eagle-import:TP_P76H50")
      (libsource (lib "eagle-import") (part "TESTPOINT"))
    )
    (comp (ref "TP5")
      (value "TESTPOINT")
      (footprint "eagle-import:TP_P76H50")
      (libsource (lib "eagle-import") (part "TESTPOINT"))
    )
    (comp (ref "TP7")
      (value "TESTPOINT")
      (footprint "eagle-import:TP_P76H50")
      (libsource (lib "eagle-import") (part "TESTPOINT"))
    )
    (comp (ref "TP21")
      (value "TESTPOINT")
      (footprint "eagle-import:TP_P76H50")
      (libsource (lib "eagle-import") (part "TESTPOINT"))
    )
    (comp (ref "TP22")
      (value "TESTPOINT")
      (footprint "eagle-import:TP_P76H50")
      (libsource (lib "eagle-import") (part "TESTPOINT"))
    )
    (comp (ref "TP23")
      (value "TESTPOINT")
      (footprint "eagle-import:TP_P76H50")
      (libsource (lib "eagle-import") (part "TESTPOINT"))
    )
    (comp (ref "TP24")
      (value "TESTPOINT")
      (footprint "eagle-import:TP_P76H50")
      (libsource (lib "eagle-import") (part "TESTPOINT"))
    )
    (comp (ref "TP25")
      (value "TESTPOINT")
      (footprint "eagle-import:TP_P76H50")
      (libsource (lib "eagle-import") (part "TESTPOINT"))
    )
    (comp (ref "TP30")
      (value "TESTPOINT")
      (footprint "eagle-import:TP_P76H50")
      (libsource (lib "eagle-import") (part "TESTPOINT"))
    )
    (comp (ref "TP32")
      (value "TESTPOINT")
      (footprint "eagle-import:TP_P76H50")
      (libsource (lib "eagle-import") (part "TESTPOINT"))
    )
    (comp (ref "U3")
      (value "ADS7841E_2K5")
      (footprint "eagle-import:DBQ16")
      (fields
        (field (name "GENERIC_PART_NUMBER") "ADS7841")
        (field (name "MANUFACTURER") "Texas Instruments")
      )
      (libsource (lib "eagle-import") (part "ADS7841E_2K5"))
    )
    (comp (ref "U7")
      (value "DRV10970_MOTOR_DRIVERDRV10970")
      (footprint "eagle-import:SOP65P640X120-25T240X328N")
      (libsource (lib "eagle-import") (part "DRV10970_MOTOR_DRIVERDRV10970"))
    )
    (comp (ref "C28")
      (value "1u")
      (footprint "eagle-import:C0402")
      (libsource (lib "eagle-import") (part "resistor_348_C-EUC0402"))
    )
    (comp (ref "C65")
      (value "0.1u")
      (footprint "eagle-import:C0402")
      (libsource (lib "eagle-import") (part "resistor_348_C-EUC0402"))
    )
    (comp (ref "C66")
      (value "1u")
      (footprint "eagle-import:C0402")
      (libsource (lib "eagle-import") (part "resistor_348_C-EUC0402"))
    )
    (comp (ref "C78")
      (value "0.1u")
      (footprint "eagle-import:C0402")
      (libsource (lib "eagle-import") (part "resistor_348_C-EUC0402"))
    )
    (comp (ref "C79")
      (value "0.1u")
      (footprint "eagle-import:C0402")
      (libsource (lib "eagle-import") (part "resistor_348_C-EUC0402"))
    )
    (comp (ref "C80")
      (value "1u")
      (footprint "eagle-import:C0402")
      (libsource (lib "eagle-import") (part "resistor_348_C-EUC0402"))
    )
    (comp (ref "C81")
      (value "0.1u")
      (footprint "eagle-import:C0402")
      (libsource (lib "eagle-import") (part "resistor_348_C-EUC0402"))
    )
    (comp (ref "C82")
      (value "4.7u")
      (footprint "eagle-import:C0402")
      (libsource (lib "eagle-import") (part "resistor_348_C-EUC0402"))
    )
    (comp (ref "C83")
      (value "0.1u")
      (footprint "eagle-import:C0402")
      (libsource (lib "eagle-import") (part "resistor_348_C-EUC0402"))
    )
    (comp (ref "C84")
      (value "0.022u")
      (footprint "eagle-import:C0402")
      (libsource (lib "eagle-import") (part "resistor_348_C-EUC0402"))
    )
    (comp (ref "C85")
      (value "4.7u")
      (footprint "eagle-import:C0402")
      (libsource (lib "eagle-import") (part "resistor_348_C-EUC0402"))
    )
    (comp (ref "C86")
      (value "0.1u")
      (footprint "eagle-import:C0402")
      (libsource (lib "eagle-import") (part "resistor_348_C-EUC0402"))
    )
    (comp (ref "C87")
      (value "4.7u")
      (footprint "eagle-import:C0402")
      (libsource (lib "eagle-import") (part "resistor_348_C-EUC0402"))
    )
    (comp (ref "C88")
      (value "0.1u")
      (footprint "eagle-import:C0402")
      (libsource (lib "eagle-import") (part "resistor_348_C-EUC0402"))
    )
    (comp (ref "C100")
      (value "0.022u")
      (footprint "eagle-import:C0402")
      (libsource (lib "eagle-import") (part "resistor_348_C-EUC0402"))
    )
    (comp (ref "C101")
      (value "0.022u")
      (footprint "eagle-import:C0402")
      (libsource (lib "eagle-import") (part "resistor_348_C-EUC0402"))
    )
    (comp (ref "J7")
      (value "TRM_BLK_1X2")
      (footprint "eagle-import:2POL254")
      (libsource (lib "eagle-import") (part "TRM_BLK_1X2"))
    )
    (comp (ref "J8")
      (value "TRM_BLK_1X2")
      (footprint "eagle-import:2POL254")
      (libsource (lib "eagle-import") (part "TRM_BLK_1X2"))
    )
    (comp (ref "J9")
      (value "TRM_BLK_1X2")
      (footprint "eagle-import:2POL254")
      (libsource (lib "eagle-import") (part "TRM_BLK_1X2"))
    )
    (comp (ref "R6")
      (value "10k")
      (footprint "eagle-import:R0402")
      (libsource (lib "eagle-import") (part "R-US_R0402"))
    )
    (comp (ref "R22")
      (value "280R")
      (footprint "eagle-import:R0402")
      (libsource (lib "eagle-import") (part "resistor_348_R-US_R0402"))
    )
    (comp (ref "R23")
      (value "13.7k")
      (footprint "eagle-import:R0402")
      (libsource (lib "eagle-import") (part "resistor_348_R-US_R0402"))
    )
    (comp (ref "R24")
      (value "3.74k")
      (footprint "eagle-import:R0402")
      (libsource (lib "eagle-import") (part "resistor_348_R-US_R0402"))
    )
    (comp (ref "R25")
      (value "280R")
      (footprint "eagle-import:R0402")
      (libsource (lib "eagle-import") (part "resistor_348_R-US_R0402"))
    )
    (comp (ref "R28")
      (value "13.7k")
      (footprint "eagle-import:R0402")
      (libsource (lib "eagle-import") (part "resistor_348_R-US_R0402"))
    )
    (comp (ref "R31")
      (value "3.74k")
      (footprint "eagle-import:R0402")
      (libsource (lib "eagle-import") (part "resistor_348_R-US_R0402"))
    )
    (comp (ref "R32")
      (value "280R")
      (footprint "eagle-import:R0402")
      (libsource (lib "eagle-import") (part "resistor_348_R-US_R0402"))
    )
    (comp (ref "R33")
      (value "13.7k")
      (footprint "eagle-import:R0402")
      (libsource (lib "eagle-import") (part "resistor_348_R-US_R0402"))
    )
    (comp (ref "R34")
      (value "3.74k")
      (footprint "eagle-import:R0402")
      (libsource (lib "eagle-import") (part "resistor_348_R-US_R0402"))
    )
    (comp (ref "TP3")
      (value "TESTPOINT")
      (footprint "eagle-import:TP_P76H50")
      (libsource (lib "eagle-import") (part "TESTPOINT"))
    )
    (comp (ref "TP6")
      (value "TESTPOINT")
      (footprint "eagle-import:TP_P76H50")
      (libsource (lib "eagle-import") (part "TESTPOINT"))
    )
    (comp (ref "TP8")
      (value "TESTPOINT")
      (footprint "eagle-import:TP_P76H50")
      (libsource (lib "eagle-import") (part "TESTPOINT"))
    )
    (comp (ref "TP17")
      (value "TESTPOINT")
      (footprint "eagle-import:TP_P76H50")
      (libsource (lib "eagle-import") (part "TESTPOINT"))
    )
    (comp (ref "U4")
      (value "ADS7841E_2K5")
      (footprint "eagle-import:DBQ16")
      (fields
        (field (name "GENERIC_PART_NUMBER") "ADS7841")
        (field (name "MANUFACTURER") "Texas Instruments")
      )
      (libsource (lib "eagle-import") (part "ADS7841E_2K5"))
    )
    (comp (ref "U6")
      (value "TLV9051IDCKR")
      (footprint "eagle-import:SC70-5P65_210X110L36X22N_TLV9051")
      (libsource (lib "eagle-import") (part "TLV9051IDCKR"))
    )
    (comp (ref "U23")
      (value "TLV9051IDCKR")
      (footprint "eagle-import:SC70-5P65_210X110L36X22N_TLV9051")
      (libsource (lib "eagle-import") (part "TLV9051IDCKR"))
    )
    (comp (ref "U24")
      (value "TLV9051IDCKR")
      (footprint "eagle-import:SC70-5P65_210X110L36X22N_TLV9051")
      (libsource (lib "eagle-import") (part "TLV9051IDCKR"))
    )
    (comp (ref "C72")
      (value "1u")
      (footprint "eagle-import:C0402")
      (libsource (lib "eagle-import") (part "resistor_348_C-EUC0402"))
    )
    (comp (ref "C73")
      (value "0.1u")
      (footprint "eagle-import:C0402")
      (libsource (lib "eagle-import") (part "resistor_348_C-EUC0402"))
    )
    (comp (ref "C74")
      (value "1u")
      (footprint "eagle-import:C0402")
      (libsource (lib "eagle-import") (part "resistor_348_C-EUC0402"))
    )
    (comp (ref "C75")
      (value "0.1u")
      (footprint "eagle-import:C0402")
      (libsource (lib "eagle-import") (part "resistor_348_C-EUC0402"))
    )
    (comp (ref "C76")
      (value "0.1u")
      (footprint "eagle-import:C0402")
      (libsource (lib "eagle-import") (part "resistor_348_C-EUC0402"))
    )
    (comp (ref "C77")
      (value "1u")
      (footprint "eagle-import:C0402")
      (libsource (lib "eagle-import") (part "resistor_348_C-EUC0402"))
    )
    (comp (ref "C102")
      (value "0.1u")
      (footprint "eagle-import:C0402")
      (libsource (lib "eagle-import") (part "resistor_348_C-EUC0402"))
    )
    (comp (ref "C103")
      (value "4.7u")
      (footprint "eagle-import:C0402")
      (libsource (lib "eagle-import") (part "resistor_348_C-EUC0402"))
    )
    (comp (ref "C104")
      (value "0.1u")
      (footprint "eagle-import:C0402")
      (libsource (lib "eagle-import") (part "resistor_348_C-EUC0402"))
    )
    (comp (ref "C105")
      (value "0.022u")
      (footprint "eagle-import:C0402")
      (libsource (lib "eagle-import") (part "resistor_348_C-EUC0402"))
    )
    (comp (ref "C106")
      (value "4.7u")
      (footprint "eagle-import:C0402")
      (libsource (lib "eagle-import") (part "resistor_348_C-EUC0402"))
    )
    (comp (ref "C107")
      (value "0.1u")
      (footprint "eagle-import:C0402")
      (libsource (lib "eagle-import") (part "resistor_348_C-EUC0402"))
    )
    (comp (ref "C108")
      (value "4.7u")
      (footprint "eagle-import:C0402")
      (libsource (lib "eagle-import") (part "resistor_348_C-EUC0402"))
    )
    (comp (ref "C109")
      (value "0.1u")
      (footprint "eagle-import:C0402")
      (libsource (lib "eagle-import") (part "resistor_348_C-EUC0402"))
    )
    (comp (ref "C110")
      (value "0.022u")
      (footprint "eagle-import:C0402")
      (libsource (lib "eagle-import") (part "resistor_348_C-EUC0402"))
    )
    (comp (ref "C111")
      (value "0.022u")
      (footprint "eagle-import:C0402")
      (libsource (lib "eagle-import") (part "resistor_348_C-EUC0402"))
    )
    (comp (ref "J16")
      (value "TRM_BLK_1X2")
      (footprint "eagle-import:2POL254")
      (libsource (lib "eagle-import") (part "TRM_BLK_1X2"))
    )
    (comp (ref "J17")
      (value "TRM_BLK_1X2")
      (footprint "eagle-import:2POL254")
      (libsource (lib "eagle-import") (part "TRM_BLK_1X2"))
    )
    (comp (ref "J18")
      (value "TRM_BLK_1X2")
      (footprint "eagle-import:2POL254")
      (libsource (lib "eagle-import") (part "TRM_BLK_1X2"))
    )
    (comp (ref "R3")
      (value "10k")
      (footprint "eagle-import:R0402")
      (libsource (lib "eagle-import") (part "R-US_R0402"))
    )
    (comp (ref "R53")
      (value "280R")
      (footprint "eagle-import:R0402")
      (libsource (lib "eagle-import") (part "resistor_348_R-US_R0402"))
    )
    (comp (ref "R54")
      (value "13.7k")
      (footprint "eagle-import:R0402")
      (libsource (lib "eagle-import") (part "resistor_348_R-US_R0402"))
    )
    (comp (ref "R55")
      (value "3.74k")
      (footprint "eagle-import:R0402")
      (libsource (lib "eagle-import") (part "resistor_348_R-US_R0402"))
    )
    (comp (ref "R56")
      (value "280R")
      (footprint "eagle-import:R0402")
      (libsource (lib "eagle-import") (part "resistor_348_R-US_R0402"))
    )
    (comp (ref "R57")
      (value "13.7k")
      (footprint "eagle-import:R0402")
      (libsource (lib "eagle-import") (part "resistor_348_R-US_R0402"))
    )
    (comp (ref "R58")
      (value "3.74k")
      (footprint "eagle-import:R0402")
      (libsource (lib "eagle-import") (part "resistor_348_R-US_R0402"))
    )
    (comp (ref "R59")
      (value "280R")
      (footprint "eagle-import:R0402")
      (libsource (lib "eagle-import") (part "resistor_348_R-US_R0402"))
    )
    (comp (ref "R60")
      (value "13.7k")
      (footprint "eagle-import:R0402")
      (libsource (lib "eagle-import") (part "resistor_348_R-US_R0402"))
    )
    (comp (ref "R61")
      (value "3.74k")
      (footprint "eagle-import:R0402")
      (libsource (lib "eagle-import") (part "resistor_348_R-US_R0402"))
    )
    (comp (ref "TP9")
      (value "TESTPOINT")
      (footprint "eagle-import:TP_P76H50")
      (libsource (lib "eagle-import") (part "TESTPOINT"))
    )
    (comp (ref "TP14")
      (value "TESTPOINT")
      (footprint "eagle-import:TP_P76H50")
      (libsource (lib "eagle-import") (part "TESTPOINT"))
    )
    (comp (ref "TP15")
      (value "TESTPOINT")
      (footprint "eagle-import:TP_P76H50")
      (libsource (lib "eagle-import") (part "TESTPOINT"))
    )
    (comp (ref "TP16")
      (value "TESTPOINT")
      (footprint "eagle-import:TP_P76H50")
      (libsource (lib "eagle-import") (part "TESTPOINT"))
    )
    (comp (ref "U25")
      (value "ADS7841E_2K5")
      (footprint "eagle-import:DBQ16")
      (fields
        (field (name "GENERIC_PART_NUMBER") "ADS7841")
        (field (name "MANUFACTURER") "Texas Instruments")
      )
      (libsource (lib "eagle-import") (part "ADS7841E_2K5"))
    )
    (comp (ref "U26")
      (value "TLV9051IDCKR")
      (footprint "eagle-import:SC70-5P65_210X110L36X22N_TLV9051")
      (libsource (lib "eagle-import") (part "TLV9051IDCKR"))
    )
    (comp (ref "U28")
      (value "TLV9051IDCKR")
      (footprint "eagle-import:SC70-5P65_210X110L36X22N_TLV9051")
      (libsource (lib "eagle-import") (part "TLV9051IDCKR"))
    )
    (comp (ref "U29")
      (value "TLV9051IDCKR")
      (footprint "eagle-import:SC70-5P65_210X110L36X22N_TLV9051")
      (libsource (lib "eagle-import") (part "TLV9051IDCKR"))
    )
    (comp (ref "C25")
      (value "0.1u")
      (footprint "eagle-import:C0603")
      (libsource (lib "eagle-import") (part "C-EUC0603"))
    )
    (comp (ref "C26")
      (value "0.1u")
      (footprint "eagle-import:C0603")
      (libsource (lib "eagle-import") (part "C-EUC0603"))
    )
    (comp (ref "C27")
      (value "0.1u")
      (footprint "eagle-import:C0402")
      (libsource (lib "eagle-import") (part "C-EUC0402"))
    )
    (comp (ref "C29")
      (value "0.1u")
      (footprint "eagle-import:C0402")
      (libsource (lib "eagle-import") (part "C-EUC0402"))
    )
    (comp (ref "C33")
      (value "1u")
      (footprint "eagle-import:C0402")
      (libsource (lib "eagle-import") (part "C-EUC0402"))
    )
    (comp (ref "C37")
      (value "0.1u")
      (footprint "eagle-import:C0402")
      (libsource (lib "eagle-import") (part "C-EUC0402"))
    )
    (comp (ref "C40")
      (value "1u")
      (footprint "eagle-import:C0402")
      (libsource (lib "eagle-import") (part "C-EUC0402"))
    )
    (comp (ref "C43")
      (value "0.1u")
      (footprint "eagle-import:C0402")
      (libsource (lib "eagle-import") (part "C-EUC0402"))
    )
    (comp (ref "C44")
      (value "1u")
      (footprint "eagle-import:C0402")
      (libsource (lib "eagle-import") (part "C-EUC0402"))
    )
    (comp (ref "C56")
      (value "0.1u")
      (footprint "eagle-import:C0402")
      (libsource (lib "eagle-import") (part "C-EUC0402"))
    )
    (comp (ref "C64")
      (value "0.47u")
      (footprint "eagle-import:C0603")
      (libsource (lib "eagle-import") (part "C-EUC0603"))
    )
    (comp (ref "C121")
      (value "0.1u")
      (footprint "eagle-import:C0603")
      (libsource (lib "eagle-import") (part "C-EUC0603"))
    )
    (comp (ref "C122")
      (value "0.1u")
      (footprint "eagle-import:C0603")
      (libsource (lib "eagle-import") (part "C-EUC0603"))
    )
    (comp (ref "C123")
      (value "0.1u")
      (footprint "eagle-import:C0402")
      (libsource (lib "eagle-import") (part "C-EUC0402"))
    )
    (comp (ref "C124")
      (value "0.47u")
      (footprint "eagle-import:C0603")
      (libsource (lib "eagle-import") (part "C-EUC0603"))
    )
    (comp (ref "C129")
      (value "0.1u")
      (footprint "eagle-import:C0603")
      (libsource (lib "eagle-import") (part "C-EUC0603"))
    )
    (comp (ref "C130")
      (value "0.1u")
      (footprint "eagle-import:C0603")
      (libsource (lib "eagle-import") (part "C-EUC0603"))
    )
    (comp (ref "C131")
      (value "0.1u")
      (footprint "eagle-import:C0402")
      (libsource (lib "eagle-import") (part "C-EUC0402"))
    )
    (comp (ref "C132")
      (value "0.47u")
      (footprint "eagle-import:C0603")
      (libsource (lib "eagle-import") (part "C-EUC0603"))
    )
    (comp (ref "JP5")
      (value "JP1Q_")
      (footprint "eagle-import:1X02")
      (libsource (lib "eagle-import") (part "JP1Q_"))
    )
    (comp (ref "JP7")
      (value "JP1Q_")
      (footprint "eagle-import:1X02")
      (libsource (lib "eagle-import") (part "JP1Q_"))
    )
    (comp (ref "JP9")
      (value "JP1Q_")
      (footprint "eagle-import:1X02")
      (libsource (lib "eagle-import") (part "JP1Q_"))
    )
    (comp (ref "JX")
      (value "TRM_BLK_1X2")
      (footprint "eagle-import:2POL254")
      (libsource (lib "eagle-import") (part "TRM_BLK_1X2"))
    )
    (comp (ref "JY")
      (value "TRM_BLK_1X2")
      (footprint "eagle-import:2POL254")
      (libsource (lib "eagle-import") (part "TRM_BLK_1X2"))
    )
    (comp (ref "JZ")
      (value "TRM_BLK_1X2")
      (footprint "eagle-import:2POL254")
      (libsource (lib "eagle-import") (part "TRM_BLK_1X2"))
    )
    (comp (ref "MX")
      (value "NCTR-M002_MAGNETORQUER")
      (footprint "eagle-import:MAG_MOUNT_V3")
      (libsource (lib "eagle-import") (part "NCTR-M002_MAGNETORQUER"))
    )
    (comp (ref "MY")
      (value "NCTR-M002_MAGNETORQUER")
      (footprint "eagle-import:MAG_MOUNT_V3")
      (libsource (lib "eagle-import") (part "NCTR-M002_MAGNETORQUER"))
    )
    (comp (ref "R13")
      (value "10K")
      (footprint "eagle-import:R0402")
      (libsource (lib "eagle-import") (part "R-US_R0402"))
    )
    (comp (ref "R16")
      (value "5R")
      (footprint "eagle-import:R0402")
      (libsource (lib "eagle-import") (part "R-US_R0402"))
    )
    (comp (ref "R17")
      (value "10k")
      (footprint "eagle-import:R0402")
      (libsource (lib "eagle-import") (part "R-US_R0402"))
    )
    (comp (ref "R18")
      (value "35k")
      (footprint "eagle-import:R0402")
      (libsource (lib "eagle-import") (part "R-US_R0402"))
    )
    (comp (ref "R29")
      (value "5R")
      (footprint "eagle-import:R0402")
      (libsource (lib "eagle-import") (part "R-US_R0402"))
    )
    (comp (ref "R30")
      (value "10k")
      (footprint "eagle-import:R0402")
      (libsource (lib "eagle-import") (part "R-US_R0402"))
    )
    (comp (ref "R71")
      (value "35k")
      (footprint "eagle-import:R0402")
      (libsource (lib "eagle-import") (part "R-US_R0402"))
    )
    (comp (ref "R75")
      (value "5R")
      (footprint "eagle-import:R0402")
      (libsource (lib "eagle-import") (part "R-US_R0402"))
    )
    (comp (ref "R76")
      (value "10k")
      (footprint "eagle-import:R0402")
      (libsource (lib "eagle-import") (part "R-US_R0402"))
    )
    (comp (ref "R77")
      (value "35k")
      (footprint "eagle-import:R0402")
      (libsource (lib "eagle-import") (part "R-US_R0402"))
    )
    (comp (ref "TP31")
      (value "TESTPOINT")
      (footprint "eagle-import:TP_P76H50")
      (libsource (lib "eagle-import") (part "TESTPOINT"))
    )
    (comp (ref "TP35")
      (value "TESTPOINT")
      (footprint "eagle-import:TP_P76H50")
      (libsource (lib "eagle-import") (part "TESTPOINT"))
    )
    (comp (ref "TP36")
      (value "TESTPOINT")
      (footprint "eagle-import:TP_P76H50")
      (libsource (lib "eagle-import") (part "TESTPOINT"))
    )
    (comp (ref "TP37")
      (value "TESTPOINT")
      (footprint "eagle-import:TP_P76H50")
      (libsource (lib "eagle-import") (part "TESTPOINT"))
    )
    (comp (ref "TP38")
      (value "TESTPOINT")
      (footprint "eagle-import:TP_P76H50")
      (libsource (lib "eagle-import") (part "TESTPOINT"))
    )
    (comp (ref "TP43")
      (value "TESTPOINT")
      (footprint "eagle-import:TP_P76H50")
      (libsource (lib "eagle-import") (part "TESTPOINT"))
    )
    (comp (ref "TP44")
      (value "TESTPOINT")
      (footprint "eagle-import:TP_P76H50")
      (libsource (lib "eagle-import") (part "TESTPOINT"))
    )
    (comp (ref "TP45")
      (value "TESTPOINT")
      (footprint "eagle-import:TP_P76H50")
      (libsource (lib "eagle-import") (part "TESTPOINT"))
    )
    (comp (ref "TP46")
      (value "TESTPOINT")
      (footprint "eagle-import:TP_P76H50")
      (libsource (lib "eagle-import") (part "TESTPOINT"))
    )
    (comp (ref "TP51")
      (value "TESTPOINT")
      (footprint "eagle-import:TP_P76H50")
      (libsource (lib "eagle-import") (part "TESTPOINT"))
    )
    (comp (ref "TP52")
      (value "TESTPOINT")
      (footprint "eagle-import:TP_P76H50")
      (libsource (lib "eagle-import") (part "TESTPOINT"))
    )
    (comp (ref "TP53")
      (value "TESTPOINT")
      (footprint "eagle-import:TP_P76H50")
      (libsource (lib "eagle-import") (part "TESTPOINT"))
    )
    (comp (ref "TP54")
      (value "TESTPOINT")
      (footprint "eagle-import:TP_P76H50")
      (libsource (lib "eagle-import") (part "TESTPOINT"))
    )
    (comp (ref "U1")
      (value "TVS991")
      (footprint "eagle-import:SOT95P280X145-5N")
      (libsource (lib "eagle-import") (part "TVS991"))
    )
    (comp (ref "U2")
      (value "ADS7841E_2K5")
      (footprint "eagle-import:DBQ16")
      (fields
        (field (name "GENERIC_PART_NUMBER") "ADS7841")
        (field (name "MANUFACTURER") "Texas Instruments")
      )
      (libsource (lib "eagle-import") (part "ADS7841E_2K5"))
    )
    (comp (ref "U5")
      (value "TVS991")
      (footprint "eagle-import:SOT95P280X145-5N")
      (libsource (lib "eagle-import") (part "TVS991"))
    )
    (comp (ref "U8")
      (value "TVS991")
      (footprint "eagle-import:SOT95P280X145-5N")
      (libsource (lib "eagle-import") (part "TVS991"))
    )
    (comp (ref "U9")
      (value "BD6210F-E2")
      (footprint "eagle-import:BD6221F-E2_SOIC8P127_500X620X171L30X42N")
      (libsource (lib "eagle-import") (part "BD6210F-E2"))
    )
    (comp (ref "U35")
      (value "BD6210F-E2")
      (footprint "eagle-import:BD6221F-E2_SOIC8P127_500X620X171L30X42N")
      (libsource (lib "eagle-import") (part "BD6210F-E2"))
    )
    (comp (ref "U39")
      (value "BD6210F-E2")
      (footprint "eagle-import:BD6221F-E2_SOIC8P127_500X620X171L30X42N")
      (libsource (lib "eagle-import") (part "BD6210F-E2"))
    )
    (comp (ref "C89")
      (value "1u")
      (footprint "eagle-import:C0402")
      (libsource (lib "eagle-import") (part "resistor_348_C-EUC0402"))
    )
    (comp (ref "C90")
      (value "0.1u")
      (footprint "eagle-import:C0402")
      (libsource (lib "eagle-import") (part "resistor_348_C-EUC0402"))
    )
    (comp (ref "C91")
      (value "1u")
      (footprint "eagle-import:C0402")
      (libsource (lib "eagle-import") (part "resistor_348_C-EUC0402"))
    )
    (comp (ref "C92")
      (value "0.1u")
      (footprint "eagle-import:C0402")
      (libsource (lib "eagle-import") (part "resistor_348_C-EUC0402"))
    )
    (comp (ref "C93")
      (value "0.1u")
      (footprint "eagle-import:C0402")
      (libsource (lib "eagle-import") (part "resistor_348_C-EUC0402"))
    )
    (comp (ref "C94")
      (value "1u")
      (footprint "eagle-import:C0402")
      (libsource (lib "eagle-import") (part "resistor_348_C-EUC0402"))
    )
    (comp (ref "C95")
      (value "0.1u")
      (footprint "eagle-import:C0402")
      (libsource (lib "eagle-import") (part "resistor_348_C-EUC0402"))
    )
    (comp (ref "C96")
      (value "4.7u")
      (footprint "eagle-import:C0402")
      (libsource (lib "eagle-import") (part "resistor_348_C-EUC0402"))
    )
    (comp (ref "C97")
      (value "0.1u")
      (footprint "eagle-import:C0402")
      (libsource (lib "eagle-import") (part "resistor_348_C-EUC0402"))
    )
    (comp (ref "C98")
      (value "0.022u")
      (footprint "eagle-import:C0402")
      (libsource (lib "eagle-import") (part "resistor_348_C-EUC0402"))
    )
    (comp (ref "C99")
      (value "4.7u")
      (footprint "eagle-import:C0402")
      (libsource (lib "eagle-import") (part "resistor_348_C-EUC0402"))
    )
    (comp (ref "C112")
      (value "0.1u")
      (footprint "eagle-import:C0402")
      (libsource (lib "eagle-import") (part "resistor_348_C-EUC0402"))
    )
    (comp (ref "C113")
      (value "4.7u")
      (footprint "eagle-import:C0402")
      (libsource (lib "eagle-import") (part "resistor_348_C-EUC0402"))
    )
    (comp (ref "C114")
      (value "0.1u")
      (footprint "eagle-import:C0402")
      (libsource (lib "eagle-import") (part "resistor_348_C-EUC0402"))
    )
    (comp (ref "C115")
      (value "0.022u")
      (footprint "eagle-import:C0402")
      (libsource (lib "eagle-import") (part "resistor_348_C-EUC0402"))
    )
    (comp (ref "C116")
      (value "0.022u")
      (footprint "eagle-import:C0402")
      (libsource (lib "eagle-import") (part "resistor_348_C-EUC0402"))
    )
    (comp (ref "J10")
      (value "TRM_BLK_1X2")
      (footprint "eagle-import:2POL254")
      (libsource (lib "eagle-import") (part "TRM_BLK_1X2"))
    )
    (comp (ref "J11")
      (value "TRM_BLK_1X2")
      (footprint "eagle-import:2POL254")
      (libsource (lib "eagle-import") (part "TRM_BLK_1X2"))
    )
    (comp (ref "J12")
      (value "TRM_BLK_1X2")
      (footprint "eagle-import:2POL254")
      (libsource (lib "eagle-import") (part "TRM_BLK_1X2"))
    )
    (comp (ref "R5")
      (value "10k")
      (footprint "eagle-import:R0402")
      (libsource (lib "eagle-import") (part "R-US_R0402"))
    )
    (comp (ref "R62")
      (value "280R")
      (footprint "eagle-import:R0402")
      (libsource (lib "eagle-import") (part "resistor_348_R-US_R0402"))
    )
    (comp (ref "R63")
      (value "13.7k")
      (footprint "eagle-import:R0402")
      (libsource (lib "eagle-import") (part "resistor_348_R-US_R0402"))
    )
    (comp (ref "R64")
      (value "3.74k")
      (footprint "eagle-import:R0402")
      (libsource (lib "eagle-import") (part "resistor_348_R-US_R0402"))
    )
    (comp (ref "R65")
      (value "280R")
      (footprint "eagle-import:R0402")
      (libsource (lib "eagle-import") (part "resistor_348_R-US_R0402"))
    )
    (comp (ref "R66")
      (value "13.7k")
      (footprint "eagle-import:R0402")
      (libsource (lib "eagle-import") (part "resistor_348_R-US_R0402"))
    )
    (comp (ref "R67")
      (value "3.74k")
      (footprint "eagle-import:R0402")
      (libsource (lib "eagle-import") (part "resistor_348_R-US_R0402"))
    )
    (comp (ref "R68")
      (value "280R")
      (footprint "eagle-import:R0402")
      (libsource (lib "eagle-import") (part "resistor_348_R-US_R0402"))
    )
    (comp (ref "R69")
      (value "13.7k")
      (footprint "eagle-import:R0402")
      (libsource (lib "eagle-import") (part "resistor_348_R-US_R0402"))
    )
    (comp (ref "R70")
      (value "3.74k")
      (footprint "eagle-import:R0402")
      (libsource (lib "eagle-import") (part "resistor_348_R-US_R0402"))
    )
    (comp (ref "TP13")
      (value "TESTPOINT")
      (footprint "eagle-import:TP_P76H50")
      (libsource (lib "eagle-import") (part "TESTPOINT"))
    )
    (comp (ref "TP18")
      (value "TESTPOINT")
      (footprint "eagle-import:TP_P76H50")
      (libsource (lib "eagle-import") (part "TESTPOINT"))
    )
    (comp (ref "TP19")
      (value "TESTPOINT")
      (footprint "eagle-import:TP_P76H50")
      (libsource (lib "eagle-import") (part "TESTPOINT"))
    )
    (comp (ref "TP20")
      (value "TESTPOINT")
      (footprint "eagle-import:TP_P76H50")
      (libsource (lib "eagle-import") (part "TESTPOINT"))
    )
    (comp (ref "U27")
      (value "ADS7841E_2K5")
      (footprint "eagle-import:DBQ16")
      (fields
        (field (name "GENERIC_PART_NUMBER") "ADS7841")
        (field (name "MANUFACTURER") "Texas Instruments")
      )
      (libsource (lib "eagle-import") (part "ADS7841E_2K5"))
    )
    (comp (ref "U30")
      (value "TLV9051IDCKR")
      (footprint "eagle-import:SC70-5P65_210X110L36X22N_TLV9051")
      (libsource (lib "eagle-import") (part "TLV9051IDCKR"))
    )
    (comp (ref "U31")
      (value "TLV9051IDCKR")
      (footprint "eagle-import:SC70-5P65_210X110L36X22N_TLV9051")
      (libsource (lib "eagle-import") (part "TLV9051IDCKR"))
    )
    (comp (ref "U32")
      (value "TLV9051IDCKR")
      (footprint "eagle-import:SC70-5P65_210X110L36X22N_TLV9051")
      (libsource (lib "eagle-import") (part "TLV9051IDCKR"))
    )
    (comp (ref "C119")
      (value "0.1u")
      (footprint "eagle-import:C0603")
      (libsource (lib "eagle-import") (part "C-EUC0603"))
    )
    (comp (ref "C120")
      (value "1u")
      (footprint "eagle-import:C0603")
      (libsource (lib "eagle-import") (part "C-EUC0603"))
    )
    (comp (ref "C125")
      (value "0.33u")
      (footprint "eagle-import:C0603")
      (libsource (lib "eagle-import") (part "C-EUC0603"))
    )
    (comp (ref "C126")
      (value "0.1u")
      (footprint "eagle-import:C0603")
      (libsource (lib "eagle-import") (part "C-EUC0603"))
    )
    (comp (ref "C127")
      (value "2.2u")
      (footprint "eagle-import:C0603")
      (libsource (lib "eagle-import") (part "C-EUC0603"))
    )
    (comp (ref "C128")
      (value "10u")
      (footprint "eagle-import:C0603")
      (libsource (lib "eagle-import") (part "C-EUC0603"))
    )
    (comp (ref "C139")
      (value "0.1u")
      (footprint "eagle-import:C0603")
      (libsource (lib "eagle-import") (part "C-EUC0603"))
    )
    (comp (ref "C140")
      (value "1u")
      (footprint "eagle-import:C0603")
      (libsource (lib "eagle-import") (part "C-EUC0603"))
    )
    (comp (ref "C141")
      (value "0.33u")
      (footprint "eagle-import:C0603")
      (libsource (lib "eagle-import") (part "C-EUC0603"))
    )
    (comp (ref "C142")
      (value "0.1u")
      (footprint "eagle-import:C0603")
      (libsource (lib "eagle-import") (part "C-EUC0603"))
    )
    (comp (ref "C143")
      (value "2.2u")
      (footprint "eagle-import:C0603")
      (libsource (lib "eagle-import") (part "C-EUC0603"))
    )
    (comp (ref "C144")
      (value "10u")
      (footprint "eagle-import:C0603")
      (libsource (lib "eagle-import") (part "C-EUC0603"))
    )
    (comp (ref "J4")
      (value "PINHD-1X3")
      (footprint "eagle-import:1X03")
      (libsource (lib "eagle-import") (part "PINHD-1X3"))
    )
    (comp (ref "J5")
      (value "PINHD-1X3")
      (footprint "eagle-import:1X03")
      (libsource (lib "eagle-import") (part "PINHD-1X3"))
    )
    (comp (ref "LED1")
      (value "LEDCHIPLED_0603")
      (footprint "eagle-import:CHIPLED_0603")
      (libsource (lib "eagle-import") (part "LEDCHIPLED_0603"))
    )
    (comp (ref "LED2")
      (value "LEDCHIPLED_0603")
      (footprint "eagle-import:CHIPLED_0603")
      (libsource (lib "eagle-import") (part "LEDCHIPLED_0603"))
    )
    (comp (ref "R26")
      (value "500R")
      (footprint "eagle-import:R0603")
      (libsource (lib "eagle-import") (part "R-US_R0603"))
    )
    (comp (ref "R27")
      (value "500R")
      (footprint "eagle-import:R0603")
      (libsource (lib "eagle-import") (part "R-US_R0603"))
    )
    (comp (ref "R48")
      (value "10K")
      (footprint "eagle-import:R0603")
      (libsource (lib "eagle-import") (part "R-US_R0603"))
    )
    (comp (ref "R49")
      (value "10K")
      (footprint "eagle-import:R0603")
      (libsource (lib "eagle-import") (part "R-US_R0603"))
    )
    (comp (ref "R72")
      (value "75K")
      (footprint "eagle-import:R0603")
      (libsource (lib "eagle-import") (part "R-US_R0603"))
    )
    (comp (ref "R73")
      (value "3.3k")
      (footprint "eagle-import:R0603")
      (libsource (lib "eagle-import") (part "R-US_R0603"))
    )
    (comp (ref "R74")
      (value "3.3k")
      (footprint "eagle-import:R0603")
      (libsource (lib "eagle-import") (part "R-US_R0603"))
    )
    (comp (ref "R83")
      (value "10K")
      (footprint "eagle-import:R0603")
      (libsource (lib "eagle-import") (part "R-US_R0603"))
    )
    (comp (ref "R84")
      (value "10K")
      (footprint "eagle-import:R0603")
      (libsource (lib "eagle-import") (part "R-US_R0603"))
    )
    (comp (ref "R85")
      (value "75K")
      (footprint "eagle-import:R0603")
      (libsource (lib "eagle-import") (part "R-US_R0603"))
    )
    (comp (ref "R86")
      (value "3.3k")
      (footprint "eagle-import:R0603")
      (libsource (lib "eagle-import") (part "R-US_R0603"))
    )
    (comp (ref "R87")
      (value "3.3k")
      (footprint "eagle-import:R0603")
      (libsource (lib "eagle-import") (part "R-US_R0603"))
    )
    (comp (ref "TP34")
      (value "TESTPOINT")
      (footprint "eagle-import:TP_P76H50")
      (libsource (lib "eagle-import") (part "TESTPOINT"))
    )
    (comp (ref "TP40")
      (value "TESTPOINT")
      (footprint "eagle-import:TP_P76H50")
      (libsource (lib "eagle-import") (part "TESTPOINT"))
    )
    (comp (ref "U10")
      (value "DRV10970_MOTOR_DRIVERDRV10970")
      (footprint "eagle-import:SOP65P640X120-25T240X328N")
      (libsource (lib "eagle-import") (part "DRV10970_MOTOR_DRIVERDRV10970"))
    )
    (comp (ref "U12")
      (value "DRV10970_MOTOR_DRIVERDRV10970")
      (footprint "eagle-import:SOP65P640X120-25T240X328N")
      (libsource (lib "eagle-import") (part "DRV10970_MOTOR_DRIVERDRV10970"))
    )
    (comp (ref "J1")
      (value "PINHD-1X3")
      (footprint "eagle-import:1X03")
      (libsource (lib "eagle-import") (part "PINHD-1X3"))
    )
    (comp (ref "J2")
      (value "PINHD-2X8_TXT-MOVED")
      (footprint "eagle-import:2X08_TXT-MOVED")
      (libsource (lib "eagle-import") (part "PINHD-2X8_TXT-MOVED"))
    )
    (comp (ref "J3")
      (value "PINHD-2X8_TXT-MOVED")
      (footprint "eagle-import:2X08_TXT-MOVED")
      (libsource (lib "eagle-import") (part "PINHD-2X8_TXT-MOVED"))
    )
    (comp (ref "MH5")
      (value "MTGP700H400")
      (footprint "eagle-import:MTGP700H400")
      (libsource (lib "eagle-import") (part "MTGP700H400"))
    )
    (comp (ref "MH6")
      (value "MTGP700H400")
      (footprint "eagle-import:MTGP700H400")
      (libsource (lib "eagle-import") (part "MTGP700H400"))
    )
    (comp (ref "MH7")
      (value "MTGP700H400")
      (footprint "eagle-import:MTGP700H400")
      (libsource (lib "eagle-import") (part "MTGP700H400"))
    )
    (comp (ref "MH8")
      (value "MTGP700H400")
      (footprint "eagle-import:MTGP700H400")
      (libsource (lib "eagle-import") (part "MTGP700H400"))
    )
  )
  (nets
    (net (code "1") (name "+3V3") (class "Default")
      (node (ref "C103") (pin "1") (pinfunction "1_1") (pintype "passive"))
      (node (ref "C104") (pin "1") (pinfunction "1_1") (pintype "passive"))
      (node (ref "C106") (pin "1") (pinfunction "1_1") (pintype "passive"))
      (node (ref "C107") (pin "1") (pinfunction "1_1") (pintype "passive"))
      (node (ref "C108") (pin "1") (pinfunction "1_1") (pintype "passive"))
      (node (ref "C109") (pin "1") (pinfunction "1_1") (pintype "passive"))
      (node (ref "C112") (pin "1") (pinfunction "1_1") (pintype "passive"))
      (node (ref "C113") (pin "1") (pinfunction "1_1") (pintype "passive"))
      (node (ref "C114") (pin "1") (pinfunction "1_1") (pintype "passive"))
      (node (ref "C123") (pin "1") (pinfunction "1_1") (pintype "passive"))
      (node (ref "C131") (pin "1") (pinfunction "1_1") (pintype "passive"))
      (node (ref "C17") (pin "1") (pinfunction "1_1") (pintype "passive"))
      (node (ref "C18") (pin "1") (pinfunction "1_1") (pintype "passive"))
      (node (ref "C21") (pin "1") (pinfunction "1_1") (pintype "passive"))
      (node (ref "C22") (pin "1") (pinfunction "1_1") (pintype "passive"))
      (node (ref "C24") (pin "1") (pinfunction "1_1") (pintype "passive"))
      (node (ref "C27") (pin "1") (pinfunction "1_1") (pintype "passive"))
      (node (ref "C28") (pin "1") (pinfunction "1_1") (pintype "passive"))
      (node (ref "C29") (pin "1") (pinfunction "1_1") (pintype "passive"))
      (node (ref "C33") (pin "1") (pinfunction "1_1") (pintype "passive"))
      (node (ref "C37") (pin "1") (pinfunction "1_1") (pintype "passive"))
      (node (ref "C39") (pin "1") (pinfunction "1_1") (pintype "passive"))
      (node (ref "C40") (pin "1") (pinfunction "1_1") (pintype "passive"))
      (node (ref "C44") (pin "1") (pinfunction "1_1") (pintype "passive"))
      (node (ref "C45") (pin "1") (pinfunction "1_1") (pintype "passive"))
      (node (ref "C46") (pin "1") (pinfunction "1_1") (pintype "passive"))
      (node (ref "C47") (pin "1") (pinfunction "1_1") (pintype "passive"))
      (node (ref "C48") (pin "1") (pinfunction "1_1") (pintype "passive"))
      (node (ref "C49") (pin "1") (pinfunction "1_1") (pintype "passive"))
      (node (ref "C50") (pin "1") (pinfunction "1_1") (pintype "passive"))
      (node (ref "C52") (pin "1") (pinfunction "1_1") (pintype "passive"))
      (node (ref "C53") (pin "1") (pinfunction "1_1") (pintype "passive"))
      (node (ref "C55") (pin "1") (pinfunction "1_1") (pintype "passive"))
      (node (ref "C56") (pin "1") (pinfunction "1_1") (pintype "passive"))
      (node (ref "C65") (pin "1") (pinfunction "1_1") (pintype "passive"))
      (node (ref "C66") (pin "1") (pinfunction "1_1") (pintype "passive"))
      (node (ref "C67") (pin "1") (pinfunction "1_1") (pintype "passive"))
      (node (ref "C68") (pin "1") (pinfunction "1_1") (pintype "passive"))
      (node (ref "C69") (pin "1") (pinfunction "1_1") (pintype "passive"))
      (node (ref "C72") (pin "1") (pinfunction "1_1") (pintype "passive"))
      (node (ref "C73") (pin "1") (pinfunction "1_1") (pintype "passive"))
      (node (ref "C74") (pin "1") (pinfunction "1_1") (pintype "passive"))
      (node (ref "C75") (pin "1") (pinfunction "1_1") (pintype "passive"))
      (node (ref "C76") (pin "1") (pinfunction "1_1") (pintype "passive"))
      (node (ref "C77") (pin "1") (pinfunction "1_1") (pintype "passive"))
      (node (ref "C78") (pin "1") (pinfunction "1_1") (pintype "passive"))
      (node (ref "C79") (pin "1") (pinfunction "1_1") (pintype "passive"))
      (node (ref "C80") (pin "1") (pinfunction "1_1") (pintype "passive"))
      (node (ref "C82") (pin "1") (pinfunction "1_1") (pintype "passive"))
      (node (ref "C83") (pin "1") (pinfunction "1_1") (pintype "passive"))
      (node (ref "C85") (pin "1") (pinfunction "1_1") (pintype "passive"))
      (node (ref "C86") (pin "1") (pinfunction "1_1") (pintype "passive"))
      (node (ref "C87") (pin "1") (pinfunction "1_1") (pintype "passive"))
      (node (ref "C88") (pin "1") (pinfunction "1_1") (pintype "passive"))
      (node (ref "C89") (pin "1") (pinfunction "1_1") (pintype "passive"))
      (node (ref "C90") (pin "1") (pinfunction "1_1") (pintype "passive"))
      (node (ref "C91") (pin "1") (pinfunction "1_1") (pintype "passive"))
      (node (ref "C92") (pin "1") (pinfunction "1_1") (pintype "passive"))
      (node (ref "C93") (pin "1") (pinfunction "1_1") (pintype "passive"))
      (node (ref "C94") (pin "1") (pinfunction "1_1") (pintype "passive"))
      (node (ref "C96") (pin "1") (pinfunction "1_1") (pintype "passive"))
      (node (ref "C97") (pin "1") (pinfunction "1_1") (pintype "passive"))
      (node (ref "C99") (pin "1") (pinfunction "1_1") (pintype "passive"))
      (node (ref "J1") (pin "2") (pinfunction "2_2") (pintype "passive"))
      (node (ref "J2") (pin "15") (pinfunction "15_15") (pintype "passive"))
      (node (ref "LED2") (pin "A") (pinfunction "A_A") (pintype "passive"))
      (node (ref "R13") (pin "2") (pinfunction "2_2") (pintype "passive"))
      (node (ref "R14") (pin "2") (pinfunction "2_2") (pintype "passive"))
      (node (ref "R23") (pin "2") (pinfunction "2_2") (pintype "passive"))
      (node (ref "R28") (pin "2") (pinfunction "2_2") (pintype "passive"))
      (node (ref "R3") (pin "2") (pinfunction "2_2") (pintype "passive"))
      (node (ref "R33") (pin "2") (pinfunction "2_2") (pintype "passive"))
      (node (ref "R35") (pin "1") (pinfunction "1_1") (pintype "passive"))
      (node (ref "R36") (pin "1") (pinfunction "1_1") (pintype "passive"))
      (node (ref "R39") (pin "2") (pinfunction "2_2") (pintype "passive"))
      (node (ref "R4") (pin "2") (pinfunction "2_2") (pintype "passive"))
      (node (ref "R45") (pin "2") (pinfunction "2_2") (pintype "passive"))
      (node (ref "R5") (pin "2") (pinfunction "2_2") (pintype "passive"))
      (node (ref "R51") (pin "2") (pinfunction "2_2") (pintype "passive"))
      (node (ref "R54") (pin "2") (pinfunction "2_2") (pintype "passive"))
      (node (ref "R57") (pin "2") (pinfunction "2_2") (pintype "passive"))
      (node (ref "R6") (pin "2") (pinfunction "2_2") (pintype "passive"))
      (node (ref "R60") (pin "2") (pinfunction "2_2") (pintype "passive"))
      (node (ref "R63") (pin "2") (pinfunction "2_2") (pintype "passive"))
      (node (ref "R66") (pin "2") (pinfunction "2_2") (pintype "passive"))
      (node (ref "R69") (pin "2") (pinfunction "2_2") (pintype "passive"))
      (node (ref "R73") (pin "1") (pinfunction "1_1") (pintype "passive"))
      (node (ref "R74") (pin "1") (pinfunction "1_1") (pintype "passive"))
      (node (ref "R86") (pin "1") (pinfunction "1_1") (pintype "passive"))
      (node (ref "R87") (pin "1") (pinfunction "1_1") (pintype "passive"))
      (node (ref "U1") (pin "5") (pinfunction "VCC_5") (pintype "power_in"))
      (node (ref "U13") (pin "1") (pinfunction "VCC+_2_1") (pintype "power_in"))
      (node (ref "U13") (pin "8") (pinfunction "VREF_8") (pintype "input"))
      (node (ref "U13") (pin "9") (pinfunction "VCC+_9") (pintype "power_in"))
      (node (ref "U15") (pin "5") (pinfunction "V+_5") (pintype "bidirectional"))
      (node (ref "U19") (pin "5") (pinfunction "V+_5") (pintype "bidirectional"))
      (node (ref "U2") (pin "1") (pinfunction "VCC+_2_1") (pintype "power_in"))
      (node (ref "U2") (pin "8") (pinfunction "VREF_8") (pintype "input"))
      (node (ref "U2") (pin "9") (pinfunction "VCC+_9") (pintype "power_in"))
      (node (ref "U21") (pin "5") (pinfunction "V+_5") (pintype "bidirectional"))
      (node (ref "U23") (pin "5") (pinfunction "V+_5") (pintype "bidirectional"))
      (node (ref "U24") (pin "5") (pinfunction "V+_5") (pintype "bidirectional"))
      (node (ref "U25") (pin "1") (pinfunction "VCC+_2_1") (pintype "power_in"))
      (node (ref "U25") (pin "8") (pinfunction "VREF_8") (pintype "input"))
      (node (ref "U25") (pin "9") (pinfunction "VCC+_9") (pintype "power_in"))
      (node (ref "U26") (pin "5") (pinfunction "V+_5") (pintype "bidirectional"))
      (node (ref "U27") (pin "1") (pinfunction "VCC+_2_1") (pintype "power_in"))
      (node (ref "U27") (pin "8") (pinfunction "VREF_8") (pintype "input"))
      (node (ref "U27") (pin "9") (pinfunction "VCC+_9") (pintype "power_in"))
      (node (ref "U28") (pin "5") (pinfunction "V+_5") (pintype "bidirectional"))
      (node (ref "U29") (pin "5") (pinfunction "V+_5") (pintype "bidirectional"))
      (node (ref "U3") (pin "1") (pinfunction "VCC+_2_1") (pintype "power_in"))
      (node (ref "U3") (pin "8") (pinfunction "VREF_8") (pintype "input"))
      (node (ref "U3") (pin "9") (pinfunction "VCC+_9") (pintype "power_in"))
      (node (ref "U30") (pin "5") (pinfunction "V+_5") (pintype "bidirectional"))
      (node (ref "U31") (pin "5") (pinfunction "V+_5") (pintype "bidirectional"))
      (node (ref "U32") (pin "5") (pinfunction "V+_5") (pintype "bidirectional"))
      (node (ref "U4") (pin "1") (pinfunction "VCC+_2_1") (pintype "power_in"))
      (node (ref "U4") (pin "8") (pinfunction "VREF_8") (pintype "input"))
      (node (ref "U4") (pin "9") (pinfunction "VCC+_9") (pintype "power_in"))
      (node (ref "U5") (pin "5") (pinfunction "VCC_5") (pintype "power_in"))
      (node (ref "U6") (pin "5") (pinfunction "V+_5") (pintype "bidirectional"))
      (node (ref "U8") (pin "5") (pinfunction "VCC_5") (pintype "power_in"))
    )
    (net (code "2") (name "+5V") (class "Default")
      (node (ref "C120") (pin "1") (pinfunction "1_1") (pintype "passive"))
      (node (ref "C121") (pin "1") (pinfunction "1_1") (pintype "passive"))
      (node (ref "C122") (pin "2") (pinfunction "2_2") (pintype "passive"))
      (node (ref "C128") (pin "1") (pinfunction "1_1") (pintype "passive"))
      (node (ref "C129") (pin "1") (pinfunction "1_1") (pintype "passive"))
      (node (ref "C130") (pin "2") (pinfunction "2_2") (pintype "passive"))
      (node (ref "C14") (pin "1") (pinfunction "1_1") (pintype "passive"))
      (node (ref "C140") (pin "1") (pinfunction "1_1") (pintype "passive"))
      (node (ref "C144") (pin "1") (pinfunction "1_1") (pintype "passive"))
      (node (ref "C25") (pin "1") (pinfunction "1_1") (pintype "passive"))
      (node (ref "C26") (pin "2") (pinfunction "2_2") (pintype "passive"))
      (node (ref "C42") (pin "1") (pinfunction "1_1") (pintype "passive"))
      (node (ref "J1") (pin "1") (pinfunction "1_1") (pintype "passive"))
      (node (ref "J19") (pin "1") (pinfunction "1_1") (pintype "bidirectional"))
      (node (ref "J20") (pin "1") (pinfunction "1_1") (pintype "bidirectional"))
      (node (ref "J21") (pin "1") (pinfunction "1_1") (pintype "bidirectional"))
      (node (ref "J3") (pin "14") (pinfunction "14_14") (pintype "passive"))
      (node (ref "J4") (pin "3") (pinfunction "3_3") (pintype "passive"))
      (node (ref "J5") (pin "3") (pinfunction "3_3") (pintype "passive"))
      (node (ref "J6") (pin "3") (pinfunction "3_3") (pintype "passive"))
      (node (ref "LED1") (pin "A") (pinfunction "A_A") (pintype "passive"))
      (node (ref "R1") (pin "2") (pinfunction "2_2") (pintype "passive"))
      (node (ref "R10") (pin "2") (pinfunction "2_2") (pintype "passive"))
      (node (ref "R11") (pin "2") (pinfunction "2_2") (pintype "passive"))
      (node (ref "R12") (pin "2") (pinfunction "2_2") (pintype "passive"))
      (node (ref "R15") (pin "2") (pinfunction "2_2") (pintype "passive"))
      (node (ref "R19") (pin "2") (pinfunction "2_2") (pintype "passive"))
      (node (ref "R2") (pin "2") (pinfunction "2_2") (pintype "passive"))
      (node (ref "R48") (pin "2") (pinfunction "2_2") (pintype "passive"))
      (node (ref "R7") (pin "2") (pinfunction "2_2") (pintype "passive"))
      (node (ref "R8") (pin "2") (pinfunction "2_2") (pintype "passive"))
      (node (ref "R83") (pin "2") (pinfunction "2_2") (pintype "passive"))
      (node (ref "R9") (pin "2") (pinfunction "2_2") (pintype "passive"))
      (node (ref "U10") (pin "15") (pinfunction "VM_15") (pintype "bidirectional"))
      (node (ref "U12") (pin "15") (pinfunction "VM_15") (pintype "bidirectional"))
      (node (ref "U35") (pin "2") (pinfunction "VCC_1_2") (pintype "bidirectional"))
      (node (ref "U35") (pin "3") (pinfunction "VCC_2_3") (pintype "bidirectional"))
      (node (ref "U35") (pin "6") (pinfunction "VREF_6") (pintype "bidirectional"))
      (node (ref "U39") (pin "2") (pinfunction "VCC_1_2") (pintype "bidirectional"))
      (node (ref "U39") (pin "3") (pinfunction "VCC_2_3") (pintype "bidirectional"))
      (node (ref "U39") (pin "6") (pinfunction "VREF_6") (pintype "bidirectional"))
      (node (ref "U7") (pin "15") (pinfunction "VM_15") (pintype "bidirectional"))
      (node (ref "U9") (pin "2") (pinfunction "VCC_1_2") (pintype "bidirectional"))
      (node (ref "U9") (pin "3") (pinfunction "VCC_2_3") (pintype "bidirectional"))
      (node (ref "U9") (pin "6") (pinfunction "VREF_6") (pintype "bidirectional"))
    )
    (net (code "3") (name "BRKMOD_X") (class "Default")
      (node (ref "J4") (pin "2") (pinfunction "2_2") (pintype "passive"))
      (node (ref "U10") (pin "21") (pinfunction "BRKMOD_21") (pintype "bidirectional"))
    )
    (net (code "4") (name "BRKMOD_Y") (class "Default")
      (node (ref "J6") (pin "2") (pinfunction "2_2") (pintype "passive"))
      (node (ref "U7") (pin "21") (pinfunction "BRKMOD_21") (pintype "bidirectional"))
    )
    (net (code "5") (name "BRKMOD_Z") (class "Default")
      (node (ref "J5") (pin "2") (pinfunction "2_2") (pintype "passive"))
      (node (ref "U12") (pin "21") (pinfunction "BRKMOD_21") (pintype "bidirectional"))
    )
    (net (code "6") (name "CUR_OUT1") (class "Default")
      (node (ref "C64") (pin "2") (pinfunction "2_2") (pintype "passive"))
      (node (ref "R18") (pin "2") (pinfunction "2_2") (pintype "passive"))
      (node (ref "TP38") (pin "1") (pinfunction "TP_1") (pintype "input"))
      (node (ref "U2") (pin "2") (pinfunction "CH0_2") (pintype "input"))
      (node (ref "U8") (pin "1") (pinfunction "OUT_1") (pintype "output"))
    )
    (net (code "7") (name "CUR_OUT2") (class "Default")
      (node (ref "C124") (pin "2") (pinfunction "2_2") (pintype "passive"))
      (node (ref "R71") (pin "2") (pinfunction "2_2") (pintype "passive"))
      (node (ref "TP46") (pin "1") (pinfunction "TP_1") (pintype "input"))
      (node (ref "U2") (pin "3") (pinfunction "CH1_3") (pintype "input"))
      (node (ref "U5") (pin "1") (pinfunction "OUT_1") (pintype "output"))
    )
    (net (code "8") (name "CUR_OUT3") (class "Default")
      (node (ref "C132") (pin "2") (pinfunction "2_2") (pintype "passive"))
      (node (ref "R77") (pin "2") (pinfunction "2_2") (pintype "passive"))
      (node (ref "TP54") (pin "1") (pinfunction "TP_1") (pintype "input"))
      (node (ref "U1") (pin "1") (pinfunction "OUT_1") (pintype "output"))
      (node (ref "U2") (pin "4") (pinfunction "CH2_4") (pintype "input"))
    )
    (net (code "9") (name "GND") (class "Default")
      (node (ref "C102") (pin "2") (pinfunction "2_2") (pintype "passive"))
      (node (ref "C103") (pin "2") (pinfunction "2_2") (pintype "passive"))
      (node (ref "C104") (pin "2") (pinfunction "2_2") (pintype "passive"))
      (node (ref "C106") (pin "2") (pinfunction "2_2") (pintype "passive"))
      (node (ref "C107") (pin "2") (pinfunction "2_2") (pintype "passive"))
      (node (ref "C108") (pin "2") (pinfunction "2_2") (pintype "passive"))
      (node (ref "C109") (pin "2") (pinfunction "2_2") (pintype "passive"))
      (node (ref "C112") (pin "2") (pinfunction "2_2") (pintype "passive"))
      (node (ref "C113") (pin "2") (pinfunction "2_2") (pintype "passive"))
      (node (ref "C114") (pin "2") (pinfunction "2_2") (pintype "passive"))
      (node (ref "C121") (pin "2") (pinfunction "2_2") (pintype "passive"))
      (node (ref "C122") (pin "1") (pinfunction "1_1") (pintype "passive"))
      (node (ref "C123") (pin "2") (pinfunction "2_2") (pintype "passive"))
      (node (ref "C124") (pin "1") (pinfunction "1_1") (pintype "passive"))
      (node (ref "C125") (pin "2") (pinfunction "2_2") (pintype "passive"))
      (node (ref "C126") (pin "2") (pinfunction "2_2") (pintype "passive"))
      (node (ref "C127") (pin "2") (pinfunction "2_2") (pintype "passive"))
      (node (ref "C128") (pin "2") (pinfunction "2_2") (pintype "passive"))
      (node (ref "C129") (pin "2") (pinfunction "2_2") (pintype "passive"))
      (node (ref "C130") (pin "1") (pinfunction "1_1") (pintype "passive"))
      (node (ref "C131") (pin "2") (pinfunction "2_2") (pintype "passive"))
      (node (ref "C132") (pin "1") (pinfunction "1_1") (pintype "passive"))
      (node (ref "C141") (pin "2") (pinfunction "2_2") (pintype "passive"))
      (node (ref "C142") (pin "2") (pinfunction "2_2") (pintype "passive"))
      (node (ref "C143") (pin "2") (pinfunction "2_2") (pintype "passive"))
      (node (ref "C144") (pin "2") (pinfunction "2_2") (pintype "passive"))
      (node (ref "C15") (pin "2") (pinfunction "2_2") (pintype "passive"))
      (node (ref "C16") (pin "2") (pinfunction "2_2") (pintype "passive"))
      (node (ref "C17") (pin "2") (pinfunction "2_2") (pintype "passive"))
      (node (ref "C18") (pin "2") (pinfunction "2_2") (pintype "passive"))
      (node (ref "C21") (pin "2") (pinfunction "2_2") (pintype "passive"))
      (node (ref "C22") (pin "2") (pinfunction "2_2") (pintype "passive"))
      (node (ref "C23") (pin "2") (pinfunction "2_2") (pintype "passive"))
      (node (ref "C24") (pin "2") (pinfunction "2_2") (pintype "passive"))
      (node (ref "C25") (pin "2") (pinfunction "2_2") (pintype "passive"))
      (node (ref "C26") (pin "1") (pinfunction "1_1") (pintype "passive"))
      (node (ref "C27") (pin "2") (pinfunction "2_2") (pintype "passive"))
      (node (ref "C28") (pin "2") (pinfunction "2_2") (pintype "passive"))
      (node (ref "C29") (pin "2") (pinfunction "2_2") (pintype "passive"))
      (node (ref "C33") (pin "2") (pinfunction "2_2") (pintype "passive"))
      (node (ref "C37") (pin "2") (pinfunction "2_2") (pintype "passive"))
      (node (ref "C39") (pin "2") (pinfunction "2_2") (pintype "passive"))
      (node (ref "C40") (pin "2") (pinfunction "2_2") (pintype "passive"))
      (node (ref "C41") (pin "2") (pinfunction "2_2") (pintype "passive"))
      (node (ref "C42") (pin "2") (pinfunction "2_2") (pintype "passive"))
      (node (ref "C43") (pin "2") (pinfunction "2_2") (pintype "passive"))
      (node (ref "C44") (pin "2") (pinfunction "2_2") (pintype "passive"))
      (node (ref "C45") (pin "2") (pinfunction "2_2") (pintype "passive"))
      (node (ref "C46") (pin "2") (pinfunction "2_2") (pintype "passive"))
      (node (ref "C47") (pin "2") (pinfunction "2_2") (pintype "passive"))
      (node (ref "C48") (pin "2") (pinfunction "2_2") (pintype "passive"))
      (node (ref "C49") (pin "2") (pinfunction "2_2") (pintype "passive"))
      (node (ref "C50") (pin "2") (pinfunction "2_2") (pintype "passive"))
      (node (ref "C51") (pin "2") (pinfunction "2_2") (pintype "passive"))
      (node (ref "C52") (pin "2") (pinfunction "2_2") (pintype "passive"))
      (node (ref "C53") (pin "2") (pinfunction "2_2") (pintype "passive"))
      (node (ref "C55") (pin "2") (pinfunction "2_2") (pintype "passive"))
      (node (ref "C56") (pin "2") (pinfunction "2_2") (pintype "passive"))
      (node (ref "C64") (pin "1") (pinfunction "1_1") (pintype "passive"))
      (node (ref "C65") (pin "2") (pinfunction "2_2") (pintype "passive"))
      (node (ref "C66") (pin "2") (pinfunction "2_2") (pintype "passive"))
      (node (ref "C67") (pin "2") (pinfunction "2_2") (pintype "passive"))
      (node (ref "C68") (pin "2") (pinfunction "2_2") (pintype "passive"))
      (node (ref "C69") (pin "2") (pinfunction "2_2") (pintype "passive"))
      (node (ref "C72") (pin "2") (pinfunction "2_2") (pintype "passive"))
      (node (ref "C73") (pin "2") (pinfunction "2_2") (pintype "passive"))
      (node (ref "C74") (pin "2") (pinfunction "2_2") (pintype "passive"))
      (node (ref "C75") (pin "2") (pinfunction "2_2") (pintype "passive"))
      (node (ref "C76") (pin "2") (pinfunction "2_2") (pintype "passive"))
      (node (ref "C77") (pin "2") (pinfunction "2_2") (pintype "passive"))
      (node (ref "C78") (pin "2") (pinfunction "2_2") (pintype "passive"))
      (node (ref "C79") (pin "2") (pinfunction "2_2") (pintype "passive"))
      (node (ref "C80") (pin "2") (pinfunction "2_2") (pintype "passive"))
      (node (ref "C81") (pin "2") (pinfunction "2_2") (pintype "passive"))
      (node (ref "C82") (pin "2") (pinfunction "2_2") (pintype "passive"))
      (node (ref "C83") (pin "2") (pinfunction "2_2") (pintype "passive"))
      (node (ref "C85") (pin "2") (pinfunction "2_2") (pintype "passive"))
      (node (ref "C86") (pin "2") (pinfunction "2_2") (pintype "passive"))
      (node (ref "C87") (pin "2") (pinfunction "2_2") (pintype "passive"))
      (node (ref "C88") (pin "2") (pinfunction "2_2") (pintype "passive"))
      (node (ref "C89") (pin "2") (pinfunction "2_2") (pintype "passive"))
      (node (ref "C90") (pin "2") (pinfunction "2_2") (pintype "passive"))
      (node (ref "C91") (pin "2") (pinfunction "2_2") (pintype "passive"))
      (node (ref "C92") (pin "2") (pinfunction "2_2") (pintype "passive"))
      (node (ref "C93") (pin "2") (pinfunction "2_2") (pintype "passive"))
      (node (ref "C94") (pin "2") (pinfunction "2_2") (pintype "passive"))
      (node (ref "C95") (pin "2") (pinfunction "2_2") (pintype "passive"))
      (node (ref "C96") (pin "2") (pinfunction "2_2") (pintype "passive"))
      (node (ref "C97") (pin "2") (pinfunction "2_2") (pintype "passive"))
      (node (ref "C99") (pin "2") (pinfunction "2_2") (pintype "passive"))
      (node (ref "J1") (pin "3") (pinfunction "3_3") (pintype "passive"))
      (node (ref "J10") (pin "1") (pinfunction "1_1") (pintype "passive"))
      (node (ref "J11") (pin "1") (pinfunction "1_1") (pintype "passive"))
      (node (ref "J12") (pin "1") (pinfunction "1_1") (pintype "passive"))
      (node (ref "J13") (pin "1") (pinfunction "1_1") (pintype "passive"))
      (node (ref "J14") (pin "1") (pinfunction "1_1") (pintype "passive"))
      (node (ref "J15") (pin "1") (pinfunction "1_1") (pintype "passive"))
      (node (ref "J16") (pin "1") (pinfunction "1_1") (pintype "passive"))
      (node (ref "J17") (pin "1") (pinfunction "1_1") (pintype "passive"))
      (node (ref "J18") (pin "1") (pinfunction "1_1") (pintype "passive"))
      (node (ref "J19") (pin "5") (pinfunction "5_5") (pintype "bidirectional"))
      (node (ref "J19") (pin "TAB1") (pinfunction "TAB1_TAB1") (pintype "bidirectional"))
      (node (ref "J19") (pin "TAB2") (pinfunction "TAB2_TAB2") (pintype "bidirectional"))
      (node (ref "J20") (pin "5") (pinfunction "5_5") (pintype "bidirectional"))
      (node (ref "J20") (pin "TAB1") (pinfunction "TAB1_TAB1") (pintype "bidirectional"))
      (node (ref "J20") (pin "TAB2") (pinfunction "TAB2_TAB2") (pintype "bidirectional"))
      (node (ref "J21") (pin "5") (pinfunction "5_5") (pintype "bidirectional"))
      (node (ref "J21") (pin "TAB1") (pinfunction "TAB1_TAB1") (pintype "bidirectional"))
      (node (ref "J21") (pin "TAB2") (pinfunction "TAB2_TAB2") (pintype "bidirectional"))
      (node (ref "J4") (pin "1") (pinfunction "1_1") (pintype "passive"))
      (node (ref "J5") (pin "1") (pinfunction "1_1") (pintype "passive"))
      (node (ref "J6") (pin "1") (pinfunction "1_1") (pintype "passive"))
      (node (ref "J7") (pin "1") (pinfunction "1_1") (pintype "passive"))
      (node (ref "J8") (pin "1") (pinfunction "1_1") (pintype "passive"))
      (node (ref "J9") (pin "1") (pinfunction "1_1") (pintype "passive"))
      (node (ref "R16") (pin "1") (pinfunction "1_1") (pintype "passive"))
      (node (ref "R20") (pin "1") (pinfunction "1_1") (pintype "passive"))
      (node (ref "R21") (pin "1") (pinfunction "1_1") (pintype "passive"))
      (node (ref "R22") (pin "1") (pinfunction "1_1") (pintype "passive"))
      (node (ref "R25") (pin "1") (pinfunction "1_1") (pintype "passive"))
      (node (ref "R26") (pin "1") (pinfunction "1_1") (pintype "passive"))
      (node (ref "R27") (pin "1") (pinfunction "1_1") (pintype "passive"))
      (node (ref "R29") (pin "1") (pinfunction "1_1") (pintype "passive"))
      (node (ref "R32") (pin "1") (pinfunction "1_1") (pintype "passive"))
      (node (ref "R38") (pin "1") (pinfunction "1_1") (pintype "passive"))
      (node (ref "R44") (pin "1") (pinfunction "1_1") (pintype "passive"))
      (node (ref "R49") (pin "1") (pinfunction "1_1") (pintype "passive"))
      (node (ref "R50") (pin "1") (pinfunction "1_1") (pintype "passive"))
      (node (ref "R53") (pin "1") (pinfunction "1_1") (pintype "passive"))
      (node (ref "R56") (pin "1") (pinfunction "1_1") (pintype "passive"))
      (node (ref "R59") (pin "1") (pinfunction "1_1") (pintype "passive"))
      (node (ref "R62") (pin "1") (pinfunction "1_1") (pintype "passive"))
      (node (ref "R65") (pin "1") (pinfunction "1_1") (pintype "passive"))
      (node (ref "R68") (pin "1") (pinfunction "1_1") (pintype "passive"))
      (node (ref "R72") (pin "1") (pinfunction "1_1") (pintype "passive"))
      (node (ref "R75") (pin "1") (pinfunction "1_1") (pintype "passive"))
      (node (ref "R84") (pin "1") (pinfunction "1_1") (pintype "passive"))
      (node (ref "R85") (pin "1") (pinfunction "1_1") (pintype "passive"))
      (node (ref "U1") (pin "2") (pinfunction "VSS_2") (pintype "power_in"))
      (node (ref "U1") (pin "4") (pinfunction "IN-_4") (pintype "input"))
      (node (ref "U10") (pin "12") (pinfunction "GND_12") (pintype "bidirectional"))
      (node (ref "U10") (pin "25") (pinfunction "THERMALPAD_25") (pintype "bidirectional"))
      (node (ref "U12") (pin "12") (pinfunction "GND_12") (pintype "bidirectional"))
      (node (ref "U12") (pin "25") (pinfunction "THERMALPAD_25") (pintype "bidirectional"))
      (node (ref "U13") (pin "10") (pinfunction "GND_10") (pintype "power_in"))
      (node (ref "U13") (pin "11") (pinfunction "MODE_11") (pintype "passive"))
      (node (ref "U13") (pin "6") (pinfunction "COM_6") (pintype "input"))
      (node (ref "U15") (pin "2") (pinfunction "V-_2") (pintype "bidirectional"))
      (node (ref "U19") (pin "2") (pinfunction "V-_2") (pintype "bidirectional"))
      (node (ref "U2") (pin "10") (pinfunction "GND_10") (pintype "power_in"))
      (node (ref "U2") (pin "11") (pinfunction "MODE_11") (pintype "passive"))
      (node (ref "U2") (pin "6") (pinfunction "COM_6") (pintype "input"))
      (node (ref "U21") (pin "2") (pinfunction "V-_2") (pintype "bidirectional"))
      (node (ref "U23") (pin "2") (pinfunction "V-_2") (pintype "bidirectional"))
      (node (ref "U24") (pin "2") (pinfunction "V-_2") (pintype "bidirectional"))
      (node (ref "U25") (pin "10") (pinfunction "GND_10") (pintype "power_in"))
      (node (ref "U25") (pin "11") (pinfunction "MODE_11") (pintype "passive"))
      (node (ref "U25") (pin "6") (pinfunction "COM_6") (pintype "input"))
      (node (ref "U26") (pin "2") (pinfunction "V-_2") (pintype "bidirectional"))
      (node (ref "U27") (pin "10") (pinfunction "GND_10") (pintype "power_in"))
      (node (ref "U27") (pin "11") (pinfunction "MODE_11") (pintype "passive"))
      (node (ref "U27") (pin "6") (pinfunction "COM_6") (pintype "input"))
      (node (ref "U28") (pin "2") (pinfunction "V-_2") (pintype "bidirectional"))
      (node (ref "U29") (pin "2") (pinfunction "V-_2") (pintype "bidirectional"))
      (node (ref "U3") (pin "10") (pinfunction "GND_10") (pintype "power_in"))
      (node (ref "U3") (pin "11") (pinfunction "MODE_11") (pintype "passive"))
      (node (ref "U3") (pin "6") (pinfunction "COM_6") (pintype "input"))
      (node (ref "U30") (pin "2") (pinfunction "V-_2") (pintype "bidirectional"))
      (node (ref "U31") (pin "2") (pinfunction "V-_2") (pintype "bidirectional"))
      (node (ref "U32") (pin "2") (pinfunction "V-_2") (pintype "bidirectional"))
      (node (ref "U4") (pin "10") (pinfunction "GND_10") (pintype "power_in"))
      (node (ref "U4") (pin "11") (pinfunction "MODE_11") (pintype "passive"))
      (node (ref "U4") (pin "6") (pinfunction "COM_6") (pintype "input"))
      (node (ref "U5") (pin "2") (pinfunction "VSS_2") (pintype "power_in"))
      (node (ref "U5") (pin "4") (pinfunction "IN-_4") (pintype "input"))
      (node (ref "U6") (pin "2") (pinfunction "V-_2") (pintype "bidirectional"))
      (node (ref "U7") (pin "12") (pinfunction "GND_12") (pintype "bidirectional"))
      (node (ref "U7") (pin "25") (pinfunction "THERMALPAD_25") (pintype "bidirectional"))
      (node (ref "U8") (pin "2") (pinfunction "VSS_2") (pintype "power_in"))
      (node (ref "U8") (pin "4") (pinfunction "IN-_4") (pintype "input"))
    )
    (net (code "10") (name "MAG_CUR_SEN_X") (class "Default")
      (node (ref "R75") (pin "2") (pinfunction "2_2") (pintype "passive"))
      (node (ref "R76") (pin "2") (pinfunction "2_2") (pintype "passive"))
      (node (ref "TP37") (pin "1") (pinfunction "TP_1") (pintype "input"))
      (node (ref "U9") (pin "8") (pinfunction "GND_8") (pintype "bidirectional"))
    )
    (net (code "11") (name "MAG_CUR_SEN_Y") (class "Default")
      (node (ref "R29") (pin "2") (pinfunction "2_2") (pintype "passive"))
      (node (ref "R30") (pin "2") (pinfunction "2_2") (pintype "passive"))
      (node (ref "TP45") (pin "1") (pinfunction "TP_1") (pintype "input"))
      (node (ref "U35") (pin "8") (pinfunction "GND_8") (pintype "bidirectional"))
    )
    (net (code "12") (name "MAG_CUR_SEN_Z") (class "Default")
      (node (ref "R16") (pin "2") (pinfunction "2_2") (pintype "passive"))
      (node (ref "R17") (pin "2") (pinfunction "2_2") (pintype "passive"))
      (node (ref "TP53") (pin "1") (pinfunction "TP_1") (pintype "input"))
      (node (ref "U39") (pin "8") (pinfunction "GND_8") (pintype "bidirectional"))
    )
    (net (code "13") (name "MAG_X_FIN") (class "Default")
      (node (ref "J3") (pin "10") (pinfunction "10_10") (pintype "passive"))
      (node (ref "TP35") (pin "1") (pinfunction "TP_1") (pintype "input"))
      (node (ref "U9") (pin "4") (pinfunction "FIN_4") (pintype "bidirectional"))
    )
    (net (code "14") (name "MAG_X_RIN") (class "Default")
      (node (ref "J3") (pin "12") (pinfunction "12_12") (pintype "passive"))
      (node (ref "TP36") (pin "1") (pinfunction "TP_1") (pintype "input"))
      (node (ref "U9") (pin "5") (pinfunction "RIN_5") (pintype "bidirectional"))
    )
    (net (code "15") (name "MAG_Y_FIN") (class "Default")
      (node (ref "J3") (pin "6") (pinfunction "6_6") (pintype "passive"))
      (node (ref "TP43") (pin "1") (pinfunction "TP_1") (pintype "input"))
      (node (ref "U35") (pin "4") (pinfunction "FIN_4") (pintype "bidirectional"))
    )
    (net (code "16") (name "MAG_Y_RIN") (class "Default")
      (node (ref "J3") (pin "8") (pinfunction "8_8") (pintype "passive"))
      (node (ref "TP44") (pin "1") (pinfunction "TP_1") (pintype "input"))
      (node (ref "U35") (pin "5") (pinfunction "RIN_5") (pintype "bidirectional"))
    )
    (net (code "17") (name "MAG_Z_FIN") (class "Default")
      (node (ref "J3") (pin "2") (pinfunction "2_2") (pintype "passive"))
      (node (ref "TP51") (pin "1") (pinfunction "TP_1") (pintype "input"))
      (node (ref "U39") (pin "4") (pinfunction "FIN_4") (pintype "bidirectional"))
    )
    (net (code "18") (name "MAG_Z_RIN") (class "Default")
      (node (ref "J3") (pin "4") (pinfunction "4_4") (pintype "passive"))
      (node (ref "TP52") (pin "1") (pinfunction "TP_1") (pintype "input"))
      (node (ref "U39") (pin "5") (pinfunction "RIN_5") (pintype "bidirectional"))
    )
    (net (code "19") (name "Net-(LED1-PadC)") (class "Default")
      (node (ref "LED1") (pin "C") (pinfunction "C_C") (pintype "passive"))
      (node (ref "R26") (pin "2") (pinfunction "2_2") (pintype "passive"))
    )
    (net (code "20") (name "Net-(LED2-PadC)") (class "Default")
      (node (ref "LED2") (pin "C") (pinfunction "C_C") (pintype "passive"))
      (node (ref "R27") (pin "2") (pinfunction "2_2") (pintype "passive"))
    )
    (net (code "21") (name "Net-(TP1-TP)") (class "Default")
      (node (ref "TP1") (pin "1") (pinfunction "TP_1") (pintype "input"))
      (node (ref "U13") (pin "2") (pinfunction "CH0_2") (pintype "input"))
    )
    (net (code "22") (name "Net-(TP9-TP)") (class "Default")
      (node (ref "TP9") (pin "1") (pinfunction "TP_1") (pintype "input"))
      (node (ref "U25") (pin "2") (pinfunction "CH0_2") (pintype "input"))
    )
    (net (code "23") (name "Net-(TP13-TP)") (class "Default")
      (node (ref "TP13") (pin "1") (pinfunction "TP_1") (pintype "input"))
      (node (ref "U27") (pin "2") (pinfunction "CH0_2") (pintype "input"))
    )
    (net (code "24") (name "Net-(TP17-TP)") (class "Default")
      (node (ref "TP17") (pin "1") (pinfunction "TP_1") (pintype "input"))
      (node (ref "U4") (pin "2") (pinfunction "CH0_2") (pintype "input"))
    )
    (net (code "25") (name "Net-(TP31-TP)") (class "Default")
      (node (ref "TP31") (pin "1") (pinfunction "TP_1") (pintype "input"))
      (node (ref "U2") (pin "5") (pinfunction "CH3_5") (pintype "input"))
    )
    (net (code "26") (name "Net-(TP32-TP)") (class "Default")
      (node (ref "TP32") (pin "1") (pinfunction "TP_1") (pintype "input"))
      (node (ref "U3") (pin "5") (pinfunction "CH3_5") (pintype "input"))
    )
    (net (code "27") (name "Net-(U1-IN+)") (class "Default")
      (node (ref "R76") (pin "1") (pinfunction "1_1") (pintype "passive"))
      (node (ref "R77") (pin "1") (pinfunction "1_1") (pintype "passive"))
      (node (ref "U1") (pin "3") (pinfunction "IN+_3") (pintype "input"))
    )
    (net (code "28") (name "Net-(U2-~{SHDN})") (class "Default")
      (node (ref "C43") (pin "1") (pinfunction "1_1") (pintype "passive"))
      (node (ref "R13") (pin "1") (pinfunction "1_1") (pintype "passive"))
      (node (ref "U2") (pin "7") (pinfunction "~{SHDN}_7") (pintype "passive"))
    )
    (net (code "29") (name "Net-(U3-~{SHDN})") (class "Default")
      (node (ref "C23") (pin "1") (pinfunction "1_1") (pintype "passive"))
      (node (ref "R14") (pin "1") (pinfunction "1_1") (pintype "passive"))
      (node (ref "U3") (pin "7") (pinfunction "~{SHDN}_7") (pintype "passive"))
    )
    (net (code "30") (name "Net-(U4-~{SHDN})") (class "Default")
      (node (ref "C81") (pin "1") (pinfunction "1_1") (pintype "passive"))
      (node (ref "R6") (pin "1") (pinfunction "1_1") (pintype "passive"))
      (node (ref "U4") (pin "7") (pinfunction "~{SHDN}_7") (pintype "passive"))
    )
    (net (code "31") (name "Net-(U5-IN+)") (class "Default")
      (node (ref "R30") (pin "1") (pinfunction "1_1") (pintype "passive"))
      (node (ref "R71") (pin "1") (pinfunction "1_1") (pintype "passive"))
      (node (ref "U5") (pin "3") (pinfunction "IN+_3") (pintype "input"))
    )
    (net (code "32") (name "Net-(U6-+)") (class "Default")
      (node (ref "R22") (pin "2") (pinfunction "2_2") (pintype "passive"))
      (node (ref "R23") (pin "1") (pinfunction "1_1") (pintype "passive"))
      (node (ref "U6") (pin "1") (pinfunction "+_1") (pintype "bidirectional"))
    )
    (net (code "33") (name "Net-(U6--)") (class "Default")
      (node (ref "C84") (pin "1") (pinfunction "1_1") (pintype "passive"))
      (node (ref "J8") (pin "2") (pinfunction "2_2") (pintype "passive"))
      (node (ref "R24") (pin "1") (pinfunction "1_1") (pintype "passive"))
      (node (ref "U6") (pin "3") (pinfunction "-_3") (pintype "bidirectional"))
    )
    (net (code "34") (name "Net-(U7-CPN)") (class "Default")
      (node (ref "C13") (pin "2") (pinfunction "2_2") (pintype "passive"))
      (node (ref "U7") (pin "10") (pinfunction "CPN_10") (pintype "bidirectional"))
    )
    (net (code "35") (name "Net-(U7-CPP)") (class "Default")
      (node (ref "C13") (pin "1") (pinfunction "1_1") (pintype "passive"))
      (node (ref "U7") (pin "9") (pinfunction "CPP_9") (pintype "bidirectional"))
    )
    (net (code "36") (name "Net-(U7-RETRY)") (class "Default")
      (node (ref "C15") (pin "1") (pinfunction "1_1") (pintype "passive"))
      (node (ref "U7") (pin "22") (pinfunction "RETRY_22") (pintype "bidirectional"))
    )
    (net (code "37") (name "Net-(U7-VCP)") (class "Default")
      (node (ref "C14") (pin "2") (pinfunction "2_2") (pintype "passive"))
      (node (ref "U7") (pin "8") (pinfunction "VCP_8") (pintype "bidirectional"))
    )
    (net (code "38") (name "Net-(U7-VINT)") (class "Default")
      (node (ref "C41") (pin "1") (pinfunction "1_1") (pintype "passive"))
      (node (ref "U7") (pin "16") (pinfunction "VINT_16") (pintype "bidirectional"))
    )
    (net (code "39") (name "Net-(U8-IN+)") (class "Default")
      (node (ref "R17") (pin "1") (pinfunction "1_1") (pintype "passive"))
      (node (ref "R18") (pin "1") (pinfunction "1_1") (pintype "passive"))
      (node (ref "U8") (pin "3") (pinfunction "IN+_3") (pintype "input"))
    )
    (net (code "40") (name "Net-(U9-OUT2)") (class "Default")
      (node (ref "JP5") (pin "2") (pinfunction "2_2") (pintype "passive"))
      (node (ref "U9") (pin "7") (pinfunction "OUT2_7") (pintype "bidirectional"))
    )
    (net (code "41") (name "Net-(U10-CPN)") (class "Default")
      (node (ref "C119") (pin "2") (pinfunction "2_2") (pintype "passive"))
      (node (ref "U10") (pin "10") (pinfunction "CPN_10") (pintype "bidirectional"))
    )
    (net (code "42") (name "Net-(U10-CPP)") (class "Default")
      (node (ref "C119") (pin "1") (pinfunction "1_1") (pintype "passive"))
      (node (ref "U10") (pin "9") (pinfunction "CPP_9") (pintype "bidirectional"))
    )
    (net (code "43") (name "Net-(U10-RETRY)") (class "Default")
      (node (ref "C125") (pin "1") (pinfunction "1_1") (pintype "passive"))
      (node (ref "U10") (pin "22") (pinfunction "RETRY_22") (pintype "bidirectional"))
    )
    (net (code "44") (name "Net-(U10-VCP)") (class "Default")
      (node (ref "C120") (pin "2") (pinfunction "2_2") (pintype "passive"))
      (node (ref "U10") (pin "8") (pinfunction "VCP_8") (pintype "bidirectional"))
    )
    (net (code "45") (name "Net-(U10-VINT)") (class "Default")
      (node (ref "C127") (pin "1") (pinfunction "1_1") (pintype "passive"))
      (node (ref "U10") (pin "16") (pinfunction "VINT_16") (pintype "bidirectional"))
    )
    (net (code "46") (name "Net-(U12-CPN)") (class "Default")
      (node (ref "C139") (pin "2") (pinfunction "2_2") (pintype "passive"))
      (node (ref "U12") (pin "10") (pinfunction "CPN_10") (pintype "bidirectional"))
    )
    (net (code "47") (name "Net-(U12-CPP)") (class "Default")
      (node (ref "C139") (pin "1") (pinfunction "1_1") (pintype "passive"))
      (node (ref "U12") (pin "9") (pinfunction "CPP_9") (pintype "bidirectional"))
    )
    (net (code "48") (name "Net-(U12-RETRY)") (class "Default")
      (node (ref "C141") (pin "1") (pinfunction "1_1") (pintype "passive"))
      (node (ref "U12") (pin "22") (pinfunction "RETRY_22") (pintype "bidirectional"))
    )
    (net (code "49") (name "Net-(U12-VCP)") (class "Default")
      (node (ref "C140") (pin "2") (pinfunction "2_2") (pintype "passive"))
      (node (ref "U12") (pin "8") (pinfunction "VCP_8") (pintype "bidirectional"))
    )
    (net (code "50") (name "Net-(U12-VINT)") (class "Default")
      (node (ref "C143") (pin "1") (pinfunction "1_1") (pintype "passive"))
      (node (ref "U12") (pin "16") (pinfunction "VINT_16") (pintype "bidirectional"))
    )
    (net (code "51") (name "Net-(U13-~{SHDN})") (class "Default")
      (node (ref "C51") (pin "1") (pinfunction "1_1") (pintype "passive"))
      (node (ref "R4") (pin "1") (pinfunction "1_1") (pintype "passive"))
      (node (ref "U13") (pin "7") (pinfunction "~{SHDN}_7") (pintype "passive"))
    )
    (net (code "52") (name "Net-(U15-+)") (class "Default")
      (node (ref "R38") (pin "2") (pinfunction "2_2") (pintype "passive"))
      (node (ref "R39") (pin "1") (pinfunction "1_1") (pintype "passive"))
      (node (ref "U15") (pin "1") (pinfunction "+_1") (pintype "bidirectional"))
    )
    (net (code "53") (name "Net-(U15--)") (class "Default")
      (node (ref "C54") (pin "1") (pinfunction "1_1") (pintype "passive"))
      (node (ref "J15") (pin "2") (pinfunction "2_2") (pintype "passive"))
      (node (ref "R40") (pin "1") (pinfunction "1_1") (pintype "passive"))
      (node (ref "U15") (pin "3") (pinfunction "-_3") (pintype "bidirectional"))
    )
    (net (code "54") (name "Net-(U19-+)") (class "Default")
      (node (ref "R44") (pin "2") (pinfunction "2_2") (pintype "passive"))
      (node (ref "R45") (pin "1") (pinfunction "1_1") (pintype "passive"))
      (node (ref "U19") (pin "1") (pinfunction "+_1") (pintype "bidirectional"))
    )
    (net (code "55") (name "Net-(U19--)") (class "Default")
      (node (ref "C70") (pin "1") (pinfunction "1_1") (pintype "passive"))
      (node (ref "J14") (pin "2") (pinfunction "2_2") (pintype "passive"))
      (node (ref "R46") (pin "1") (pinfunction "1_1") (pintype "passive"))
      (node (ref "U19") (pin "3") (pinfunction "-_3") (pintype "bidirectional"))
    )
    (net (code "56") (name "Net-(U21-+)") (class "Default")
      (node (ref "R50") (pin "2") (pinfunction "2_2") (pintype "passive"))
      (node (ref "R51") (pin "1") (pinfunction "1_1") (pintype "passive"))
      (node (ref "U21") (pin "1") (pinfunction "+_1") (pintype "bidirectional"))
    )
    (net (code "57") (name "Net-(U21--)") (class "Default")
      (node (ref "C71") (pin "1") (pinfunction "1_1") (pintype "passive"))
      (node (ref "J13") (pin "2") (pinfunction "2_2") (pintype "passive"))
      (node (ref "R52") (pin "1") (pinfunction "1_1") (pintype "passive"))
      (node (ref "U21") (pin "3") (pinfunction "-_3") (pintype "bidirectional"))
    )
    (net (code "58") (name "Net-(U23-+)") (class "Default")
      (node (ref "R25") (pin "2") (pinfunction "2_2") (pintype "passive"))
      (node (ref "R28") (pin "1") (pinfunction "1_1") (pintype "passive"))
      (node (ref "U23") (pin "1") (pinfunction "+_1") (pintype "bidirectional"))
    )
    (net (code "59") (name "Net-(U23--)") (class "Default")
      (node (ref "C100") (pin "1") (pinfunction "1_1") (pintype "passive"))
      (node (ref "J7") (pin "2") (pinfunction "2_2") (pintype "passive"))
      (node (ref "R31") (pin "1") (pinfunction "1_1") (pintype "passive"))
      (node (ref "U23") (pin "3") (pinfunction "-_3") (pintype "bidirectional"))
    )
    (net (code "60") (name "Net-(U24-+)") (class "Default")
      (node (ref "R32") (pin "2") (pinfunction "2_2") (pintype "passive"))
      (node (ref "R33") (pin "1") (pinfunction "1_1") (pintype "passive"))
      (node (ref "U24") (pin "1") (pinfunction "+_1") (pintype "bidirectional"))
    )
    (net (code "61") (name "Net-(U24--)") (class "Default")
      (node (ref "C101") (pin "1") (pinfunction "1_1") (pintype "passive"))
      (node (ref "J9") (pin "2") (pinfunction "2_2") (pintype "passive"))
      (node (ref "R34") (pin "1") (pinfunction "1_1") (pintype "passive"))
      (node (ref "U24") (pin "3") (pinfunction "-_3") (pintype "bidirectional"))
    )
    (net (code "62") (name "Net-(U25-~{SHDN})") (class "Default")
      (node (ref "C102") (pin "1") (pinfunction "1_1") (pintype "passive"))
      (node (ref "R3") (pin "1") (pinfunction "1_1") (pintype "passive"))
      (node (ref "U25") (pin "7") (pinfunction "~{SHDN}_7") (pintype "passive"))
    )
    (net (code "63") (name "Net-(U26-+)") (class "Default")
      (node (ref "R53") (pin "2") (pinfunction "2_2") (pintype "passive"))
      (node (ref "R54") (pin "1") (pinfunction "1_1") (pintype "passive"))
      (node (ref "U26") (pin "1") (pinfunction "+_1") (pintype "bidirectional"))
    )
    (net (code "64") (name "Net-(U26--)") (class "Default")
      (node (ref "C105") (pin "1") (pinfunction "1_1") (pintype "passive"))
      (node (ref "J18") (pin "2") (pinfunction "2_2") (pintype "passive"))
      (node (ref "R55") (pin "1") (pinfunction "1_1") (pintype "passive"))
      (node (ref "U26") (pin "3") (pinfunction "-_3") (pintype "bidirectional"))
    )
    (net (code "65") (name "Net-(U27-~{SHDN})") (class "Default")
      (node (ref "C95") (pin "1") (pinfunction "1_1") (pintype "passive"))
      (node (ref "R5") (pin "1") (pinfunction "1_1") (pintype "passive"))
      (node (ref "U27") (pin "7") (pinfunction "~{SHDN}_7") (pintype "passive"))
    )
    (net (code "66") (name "Net-(U28-+)") (class "Default")
      (node (ref "R56") (pin "2") (pinfunction "2_2") (pintype "passive"))
      (node (ref "R57") (pin "1") (pinfunction "1_1") (pintype "passive"))
      (node (ref "U28") (pin "1") (pinfunction "+_1") (pintype "bidirectional"))
    )
    (net (code "67") (name "Net-(U28--)") (class "Default")
      (node (ref "C110") (pin "1") (pinfunction "1_1") (pintype "passive"))
      (node (ref "J17") (pin "2") (pinfunction "2_2") (pintype "passive"))
      (node (ref "R58") (pin "1") (pinfunction "1_1") (pintype "passive"))
      (node (ref "U28") (pin "3") (pinfunction "-_3") (pintype "bidirectional"))
    )
    (net (code "68") (name "Net-(U29-+)") (class "Default")
      (node (ref "R59") (pin "2") (pinfunction "2_2") (pintype "passive"))
      (node (ref "R60") (pin "1") (pinfunction "1_1") (pintype "passive"))
      (node (ref "U29") (pin "1") (pinfunction "+_1") (pintype "bidirectional"))
    )
    (net (code "69") (name "Net-(U29--)") (class "Default")
      (node (ref "C111") (pin "1") (pinfunction "1_1") (pintype "passive"))
      (node (ref "J16") (pin "2") (pinfunction "2_2") (pintype "passive"))
      (node (ref "R61") (pin "1") (pinfunction "1_1") (pintype "passive"))
      (node (ref "U29") (pin "3") (pinfunction "-_3") (pintype "bidirectional"))
    )
    (net (code "70") (name "Net-(U30-+)") (class "Default")
      (node (ref "R62") (pin "2") (pinfunction "2_2") (pintype "passive"))
      (node (ref "R63") (pin "1") (pinfunction "1_1") (pintype "passive"))
      (node (ref "U30") (pin "1") (pinfunction "+_1") (pintype "bidirectional"))
    )
    (net (code "71") (name "Net-(U30--)") (class "Default")
      (node (ref "C98") (pin "1") (pinfunction "1_1") (pintype "passive"))
      (node (ref "J12") (pin "2") (pinfunction "2_2") (pintype "passive"))
      (node (ref "R64") (pin "1") (pinfunction "1_1") (pintype "passive"))
      (node (ref "U30") (pin "3") (pinfunction "-_3") (pintype "bidirectional"))
    )
    (net (code "72") (name "Net-(U31-+)") (class "Default")
      (node (ref "R65") (pin "2") (pinfunction "2_2") (pintype "passive"))
      (node (ref "R66") (pin "1") (pinfunction "1_1") (pintype "passive"))
      (node (ref "U31") (pin "1") (pinfunction "+_1") (pintype "bidirectional"))
    )
    (net (code "73") (name "Net-(U31--)") (class "Default")
      (node (ref "C115") (pin "1") (pinfunction "1_1") (pintype "passive"))
      (node (ref "J11") (pin "2") (pinfunction "2_2") (pintype "passive"))
      (node (ref "R67") (pin "1") (pinfunction "1_1") (pintype "passive"))
      (node (ref "U31") (pin "3") (pinfunction "-_3") (pintype "bidirectional"))
    )
    (net (code "74") (name "Net-(U32-+)") (class "Default")
      (node (ref "R68") (pin "2") (pinfunction "2_2") (pintype "passive"))
      (node (ref "R69") (pin "1") (pinfunction "1_1") (pintype "passive"))
      (node (ref "U32") (pin "1") (pinfunction "+_1") (pintype "bidirectional"))
    )
    (net (code "75") (name "Net-(U32--)") (class "Default")
      (node (ref "C116") (pin "1") (pinfunction "1_1") (pintype "passive"))
      (node (ref "J10") (pin "2") (pinfunction "2_2") (pintype "passive"))
      (node (ref "R70") (pin "1") (pinfunction "1_1") (pintype "passive"))
      (node (ref "U32") (pin "3") (pinfunction "-_3") (pintype "bidirectional"))
    )
    (net (code "76") (name "Net-(U35-OUT2)") (class "Default")
      (node (ref "JP7") (pin "2") (pinfunction "2_2") (pintype "passive"))
      (node (ref "U35") (pin "7") (pinfunction "OUT2_7") (pintype "bidirectional"))
    )
    (net (code "77") (name "Net-(U39-OUT2)") (class "Default")
      (node (ref "JP9") (pin "2") (pinfunction "2_2") (pintype "passive"))
      (node (ref "U39") (pin "7") (pinfunction "OUT2_7") (pintype "bidirectional"))
    )
    (net (code "78") (name "OUT1_X") (class "Default")
      (node (ref "JX") (pin "1") (pinfunction "1_1") (pintype "passive"))
      (node (ref "U9") (pin "1") (pinfunction "OUT1_1") (pintype "bidirectional"))
    )
    (net (code "79") (name "OUT1_Y") (class "Default")
      (node (ref "JY") (pin "1") (pinfunction "1_1") (pintype "passive"))
      (node (ref "U35") (pin "1") (pinfunction "OUT1_1") (pintype "bidirectional"))
    )
    (net (code "80") (name "OUT1_Z") (class "Default")
      (node (ref "JZ") (pin "1") (pinfunction "1_1") (pintype "passive"))
      (node (ref "U39") (pin "1") (pinfunction "OUT1_1") (pintype "bidirectional"))
    )
    (net (code "81") (name "OUT2_X") (class "Default")
      (node (ref "JP5") (pin "1") (pinfunction "1_1") (pintype "passive"))
      (node (ref "JX") (pin "2") (pinfunction "2_2") (pintype "passive"))
    )
    (net (code "82") (name "OUT2_Y") (class "Default")
      (node (ref "JP7") (pin "1") (pinfunction "1_1") (pintype "passive"))
      (node (ref "JY") (pin "2") (pinfunction "2_2") (pintype "passive"))
    )
    (net (code "83") (name "OUT2_Z") (class "Default")
      (node (ref "JP9") (pin "1") (pinfunction "1_1") (pintype "passive"))
      (node (ref "JZ") (pin "2") (pinfunction "2_2") (pintype "passive"))
    )
    (net (code "84") (name "RW_X_DIR") (class "Default")
      (node (ref "J3") (pin "7") (pinfunction "7_7") (pintype "passive"))
      (node (ref "U10") (pin "23") (pinfunction "FR_23") (pintype "bidirectional"))
    )
    (net (code "85") (name "RW_X_I_SENS") (class "Default")
      (node (ref "R72") (pin "2") (pinfunction "2_2") (pintype "passive"))
      (node (ref "TP34") (pin "1") (pinfunction "TP_1") (pintype "input"))
      (node (ref "U10") (pin "17") (pinfunction "CS_17") (pintype "bidirectional"))
      (node (ref "U3") (pin "3") (pinfunction "CH1_3") (pintype "input"))
    )
    (net (code "86") (name "RW_X_LOCK") (class "Default")
      (node (ref "R74") (pin "2") (pinfunction "2_2") (pintype "passive"))
      (node (ref "U10") (pin "18") (pinfunction "RD_18") (pintype "bidirectional"))
    )
    (net (code "87") (name "RW_X_OUTFG") (class "Default")
      (node (ref "J3") (pin "13") (pinfunction "13_13") (pintype "passive"))
      (node (ref "R73") (pin "2") (pinfunction "2_2") (pintype "passive"))
      (node (ref "U10") (pin "24") (pinfunction "FG_24") (pintype "bidirectional"))
    )
    (net (code "88") (name "RW_X_SPEED_CTRL") (class "Default")
      (node (ref "J3") (pin "1") (pinfunction "1_1") (pintype "passive"))
      (node (ref "U10") (pin "19") (pinfunction "PWM_19") (pintype "bidirectional"))
    )
    (net (code "89") (name "RW_Y_DIR") (class "Default")
      (node (ref "J3") (pin "9") (pinfunction "9_9") (pintype "passive"))
      (node (ref "U7") (pin "23") (pinfunction "FR_23") (pintype "bidirectional"))
    )
    (net (code "90") (name "RW_Y_I_SENS") (class "Default")
      (node (ref "R21") (pin "2") (pinfunction "2_2") (pintype "passive"))
      (node (ref "TP30") (pin "1") (pinfunction "TP_1") (pintype "input"))
      (node (ref "U3") (pin "2") (pinfunction "CH0_2") (pintype "input"))
      (node (ref "U7") (pin "17") (pinfunction "CS_17") (pintype "bidirectional"))
    )
    (net (code "91") (name "RW_Y_LOCK") (class "Default")
      (node (ref "R36") (pin "2") (pinfunction "2_2") (pintype "passive"))
      (node (ref "U7") (pin "18") (pinfunction "RD_18") (pintype "bidirectional"))
    )
    (net (code "92") (name "RW_Y_OUTFG") (class "Default")
      (node (ref "J3") (pin "15") (pinfunction "15_15") (pintype "passive"))
      (node (ref "R35") (pin "2") (pinfunction "2_2") (pintype "passive"))
      (node (ref "U7") (pin "24") (pinfunction "FG_24") (pintype "bidirectional"))
    )
    (net (code "93") (name "RW_Y_SPEED_CTRL") (class "Default")
      (node (ref "J3") (pin "3") (pinfunction "3_3") (pintype "passive"))
      (node (ref "U7") (pin "19") (pinfunction "PWM_19") (pintype "bidirectional"))
    )
    (net (code "94") (name "RW_Z_DIR") (class "Default")
      (node (ref "J3") (pin "11") (pinfunction "11_11") (pintype "passive"))
      (node (ref "U12") (pin "23") (pinfunction "FR_23") (pintype "bidirectional"))
    )
    (net (code "95") (name "RW_Z_I_SENS") (class "Default")
      (node (ref "R85") (pin "2") (pinfunction "2_2") (pintype "passive"))
      (node (ref "TP40") (pin "1") (pinfunction "TP_1") (pintype "input"))
      (node (ref "U12") (pin "17") (pinfunction "CS_17") (pintype "bidirectional"))
      (node (ref "U3") (pin "4") (pinfunction "CH2_4") (pintype "input"))
    )
    (net (code "96") (name "RW_Z_LOCK") (class "Default")
      (node (ref "R87") (pin "2") (pinfunction "2_2") (pintype "passive"))
      (node (ref "U12") (pin "18") (pinfunction "RD_18") (pintype "bidirectional"))
    )
    (net (code "97") (name "RW_Z_OUTFG") (class "Default")
      (node (ref "J3") (pin "16") (pinfunction "16_16") (pintype "passive"))
      (node (ref "R86") (pin "2") (pinfunction "2_2") (pintype "passive"))
      (node (ref "U12") (pin "24") (pinfunction "FG_24") (pintype "bidirectional"))
    )
    (net (code "98") (name "RW_Z_SPEED_CTRL") (class "Default")
      (node (ref "J3") (pin "5") (pinfunction "5_5") (pintype "passive"))
      (node (ref "U12") (pin "19") (pinfunction "PWM_19") (pintype "bidirectional"))
    )
    (net (code "99") (name "UCB0_SPI_CLK") (class "Default")
      (node (ref "J2") (pin "2") (pinfunction "2_2") (pintype "passive"))
      (node (ref "U13") (pin "16") (pinfunction "DCLK_16") (pintype "input"))
      (node (ref "U2") (pin "16") (pinfunction "DCLK_16") (pintype "input"))
      (node (ref "U25") (pin "16") (pinfunction "DCLK_16") (pintype "input"))
      (node (ref "U27") (pin "16") (pinfunction "DCLK_16") (pintype "input"))
      (node (ref "U3") (pin "16") (pinfunction "DCLK_16") (pintype "input"))
      (node (ref "U4") (pin "16") (pinfunction "DCLK_16") (pintype "input"))
    )
    (net (code "100") (name "UCB0_SPI_MISO") (class "Default")
      (node (ref "J2") (pin "4") (pinfunction "4_4") (pintype "passive"))
      (node (ref "U13") (pin "12") (pinfunction "DOUT_12") (pintype "output"))
      (node (ref "U2") (pin "12") (pinfunction "DOUT_12") (pintype "output"))
      (node (ref "U25") (pin "12") (pinfunction "DOUT_12") (pintype "output"))
      (node (ref "U27") (pin "12") (pinfunction "DOUT_12") (pintype "output"))
      (node (ref "U3") (pin "12") (pinfunction "DOUT_12") (pintype "output"))
      (node (ref "U4") (pin "12") (pinfunction "DOUT_12") (pintype "output"))
    )
    (net (code "101") (name "UCB0_SPI_MOSI") (class "Default")
      (node (ref "J2") (pin "6") (pinfunction "6_6") (pintype "passive"))
      (node (ref "U13") (pin "14") (pinfunction "DIN_14") (pintype "input"))
      (node (ref "U2") (pin "14") (pinfunction "DIN_14") (pintype "input"))
      (node (ref "U25") (pin "14") (pinfunction "DIN_14") (pintype "input"))
      (node (ref "U27") (pin "14") (pinfunction "DIN_14") (pintype "input"))
      (node (ref "U3") (pin "14") (pinfunction "DIN_14") (pintype "input"))
      (node (ref "U4") (pin "14") (pinfunction "DIN_14") (pintype "input"))
    )
    (net (code "102") (name "VINT{slash}2_X") (class "Default")
      (node (ref "C126") (pin "1") (pinfunction "1_1") (pintype "passive"))
      (node (ref "R48") (pin "1") (pinfunction "1_1") (pintype "passive"))
      (node (ref "R49") (pin "2") (pinfunction "2_2") (pintype "passive"))
      (node (ref "U10") (pin "3") (pinfunction "U_HN_3") (pintype "bidirectional"))
      (node (ref "U10") (pin "5") (pinfunction "V_HN_5") (pintype "bidirectional"))
      (node (ref "U10") (pin "7") (pinfunction "W_HN_7") (pintype "bidirectional"))
    )
    (net (code "103") (name "VINT{slash}2_Y") (class "Default")
      (node (ref "C16") (pin "1") (pinfunction "1_1") (pintype "passive"))
      (node (ref "R19") (pin "1") (pinfunction "1_1") (pintype "passive"))
      (node (ref "R20") (pin "2") (pinfunction "2_2") (pintype "passive"))
      (node (ref "U7") (pin "3") (pinfunction "U_HN_3") (pintype "bidirectional"))
      (node (ref "U7") (pin "5") (pinfunction "V_HN_5") (pintype "bidirectional"))
      (node (ref "U7") (pin "7") (pinfunction "W_HN_7") (pintype "bidirectional"))
    )
    (net (code "104") (name "VINT{slash}2_Z") (class "Default")
      (node (ref "C142") (pin "1") (pinfunction "1_1") (pintype "passive"))
      (node (ref "R83") (pin "1") (pinfunction "1_1") (pintype "passive"))
      (node (ref "R84") (pin "2") (pinfunction "2_2") (pintype "passive"))
      (node (ref "U12") (pin "3") (pinfunction "U_HN_3") (pintype "bidirectional"))
      (node (ref "U12") (pin "5") (pinfunction "V_HN_5") (pintype "bidirectional"))
      (node (ref "U12") (pin "7") (pinfunction "W_HN_7") (pintype "bidirectional"))
    )
    (net (code "105") (name "X+_0_DEGREES") (class "Default")
      (node (ref "C105") (pin "2") (pinfunction "2_2") (pintype "passive"))
      (node (ref "R55") (pin "2") (pinfunction "2_2") (pintype "passive"))
      (node (ref "TP14") (pin "1") (pinfunction "TP_1") (pintype "input"))
      (node (ref "U25") (pin "3") (pinfunction "CH1_3") (pintype "input"))
      (node (ref "U26") (pin "4") (pinfunction "OUT_4") (pintype "bidirectional"))
    )
    (net (code "106") (name "X+_120_DEGREES") (class "Default")
      (node (ref "C110") (pin "2") (pinfunction "2_2") (pintype "passive"))
      (node (ref "R58") (pin "2") (pinfunction "2_2") (pintype "passive"))
      (node (ref "TP15") (pin "1") (pinfunction "TP_1") (pintype "input"))
      (node (ref "U25") (pin "4") (pinfunction "CH2_4") (pintype "input"))
      (node (ref "U28") (pin "4") (pinfunction "OUT_4") (pintype "bidirectional"))
    )
    (net (code "107") (name "X+_240_DEGREES") (class "Default")
      (node (ref "C111") (pin "2") (pinfunction "2_2") (pintype "passive"))
      (node (ref "R61") (pin "2") (pinfunction "2_2") (pintype "passive"))
      (node (ref "TP16") (pin "1") (pinfunction "TP_1") (pintype "input"))
      (node (ref "U25") (pin "5") (pinfunction "CH3_5") (pintype "input"))
      (node (ref "U29") (pin "4") (pinfunction "OUT_4") (pintype "bidirectional"))
    )
    (net (code "108") (name "X-_0_DEGREES") (class "Default")
      (node (ref "C54") (pin "2") (pinfunction "2_2") (pintype "passive"))
      (node (ref "R40") (pin "2") (pinfunction "2_2") (pintype "passive"))
      (node (ref "TP10") (pin "1") (pinfunction "TP_1") (pintype "input"))
      (node (ref "U13") (pin "3") (pinfunction "CH1_3") (pintype "input"))
      (node (ref "U15") (pin "4") (pinfunction "OUT_4") (pintype "bidirectional"))
    )
    (net (code "109") (name "X-_120_DEGREES") (class "Default")
      (node (ref "C70") (pin "2") (pinfunction "2_2") (pintype "passive"))
      (node (ref "R46") (pin "2") (pinfunction "2_2") (pintype "passive"))
      (node (ref "TP11") (pin "1") (pinfunction "TP_1") (pintype "input"))
      (node (ref "U13") (pin "4") (pinfunction "CH2_4") (pintype "input"))
      (node (ref "U19") (pin "4") (pinfunction "OUT_4") (pintype "bidirectional"))
    )
    (net (code "110") (name "X-_240_DEGREES") (class "Default")
      (node (ref "C71") (pin "2") (pinfunction "2_2") (pintype "passive"))
      (node (ref "R52") (pin "2") (pinfunction "2_2") (pintype "passive"))
      (node (ref "TP12") (pin "1") (pinfunction "TP_1") (pintype "input"))
      (node (ref "U13") (pin "5") (pinfunction "CH3_5") (pintype "input"))
      (node (ref "U21") (pin "4") (pinfunction "OUT_4") (pintype "bidirectional"))
    )
    (net (code "111") (name "X_HALL_A") (class "Default")
      (node (ref "J19") (pin "3") (pinfunction "3_3") (pintype "bidirectional"))
      (node (ref "R2") (pin "1") (pinfunction "1_1") (pintype "passive"))
      (node (ref "TP5") (pin "1") (pinfunction "TP_1") (pintype "input"))
      (node (ref "U10") (pin "2") (pinfunction "U_HP_2") (pintype "bidirectional"))
    )
    (net (code "112") (name "X_HALL_B") (class "Default")
      (node (ref "J19") (pin "4") (pinfunction "4_4") (pintype "bidirectional"))
      (node (ref "R1") (pin "1") (pinfunction "1_1") (pintype "passive"))
      (node (ref "TP4") (pin "1") (pinfunction "TP_1") (pintype "input"))
      (node (ref "U10") (pin "4") (pinfunction "V_HP_4") (pintype "bidirectional"))
    )
    (net (code "113") (name "X_HALL_C") (class "Default")
      (node (ref "J19") (pin "2") (pinfunction "2_2") (pintype "bidirectional"))
      (node (ref "R7") (pin "1") (pinfunction "1_1") (pintype "passive"))
      (node (ref "TP2") (pin "1") (pinfunction "TP_1") (pintype "input"))
      (node (ref "U10") (pin "6") (pinfunction "W_HP_6") (pintype "bidirectional"))
    )
    (net (code "114") (name "X_PHASE_A") (class "Default")
      (node (ref "J19") (pin "6") (pinfunction "6_6") (pintype "bidirectional"))
      (node (ref "J19") (pin "7") (pinfunction "7_7") (pintype "bidirectional"))
      (node (ref "U10") (pin "14") (pinfunction "U_14") (pintype "bidirectional"))
    )
    (net (code "115") (name "X_PHASE_B") (class "Default")
      (node (ref "J19") (pin "8") (pinfunction "8_8") (pintype "bidirectional"))
      (node (ref "J19") (pin "9") (pinfunction "9_9") (pintype "bidirectional"))
      (node (ref "U10") (pin "13") (pinfunction "V_13") (pintype "bidirectional"))
    )
    (net (code "116") (name "X_PHASE_C") (class "Default")
      (node (ref "J19") (pin "10") (pinfunction "10_10") (pintype "bidirectional"))
      (node (ref "J19") (pin "11") (pinfunction "11_11") (pintype "bidirectional"))
      (node (ref "U10") (pin "11") (pinfunction "W_11") (pintype "bidirectional"))
    )
    (net (code "117") (name "Y+_0_DEGREES") (class "Default")
      (node (ref "C98") (pin "2") (pinfunction "2_2") (pintype "passive"))
      (node (ref "R64") (pin "2") (pinfunction "2_2") (pintype "passive"))
      (node (ref "TP18") (pin "1") (pinfunction "TP_1") (pintype "input"))
      (node (ref "U27") (pin "3") (pinfunction "CH1_3") (pintype "input"))
      (node (ref "U30") (pin "4") (pinfunction "OUT_4") (pintype "bidirectional"))
    )
    (net (code "118") (name "Y+_120_DEGREES") (class "Default")
      (node (ref "C115") (pin "2") (pinfunction "2_2") (pintype "passive"))
      (node (ref "R67") (pin "2") (pinfunction "2_2") (pintype "passive"))
      (node (ref "TP19") (pin "1") (pinfunction "TP_1") (pintype "input"))
      (node (ref "U27") (pin "4") (pinfunction "CH2_4") (pintype "input"))
      (node (ref "U31") (pin "4") (pinfunction "OUT_4") (pintype "bidirectional"))
    )
    (net (code "119") (name "Y+_240_DEGREES") (class "Default")
      (node (ref "C116") (pin "2") (pinfunction "2_2") (pintype "passive"))
      (node (ref "R70") (pin "2") (pinfunction "2_2") (pintype "passive"))
      (node (ref "TP20") (pin "1") (pinfunction "TP_1") (pintype "input"))
      (node (ref "U27") (pin "5") (pinfunction "CH3_5") (pintype "input"))
      (node (ref "U32") (pin "4") (pinfunction "OUT_4") (pintype "bidirectional"))
    )
    (net (code "120") (name "Y-_0_DEGREES") (class "Default")
      (node (ref "C84") (pin "2") (pinfunction "2_2") (pintype "passive"))
      (node (ref "R24") (pin "2") (pinfunction "2_2") (pintype "passive"))
      (node (ref "TP3") (pin "1") (pinfunction "TP_1") (pintype "input"))
      (node (ref "U4") (pin "3") (pinfunction "CH1_3") (pintype "input"))
      (node (ref "U6") (pin "4") (pinfunction "OUT_4") (pintype "bidirectional"))
    )
    (net (code "121") (name "Y-_120_DEGREES") (class "Default")
      (node (ref "C100") (pin "2") (pinfunction "2_2") (pintype "passive"))
      (node (ref "R31") (pin "2") (pinfunction "2_2") (pintype "passive"))
      (node (ref "TP6") (pin "1") (pinfunction "TP_1") (pintype "input"))
      (node (ref "U23") (pin "4") (pinfunction "OUT_4") (pintype "bidirectional"))
      (node (ref "U4") (pin "4") (pinfunction "CH2_4") (pintype "input"))
    )
    (net (code "122") (name "Y-_240_DEGREES") (class "Default")
      (node (ref "C101") (pin "2") (pinfunction "2_2") (pintype "passive"))
      (node (ref "R34") (pin "2") (pinfunction "2_2") (pintype "passive"))
      (node (ref "TP8") (pin "1") (pinfunction "TP_1") (pintype "input"))
      (node (ref "U24") (pin "4") (pinfunction "OUT_4") (pintype "bidirectional"))
      (node (ref "U4") (pin "5") (pinfunction "CH3_5") (pintype "input"))
    )
    (net (code "123") (name "Y_HALL_A") (class "Default")
      (node (ref "J20") (pin "3") (pinfunction "3_3") (pintype "bidirectional"))
      (node (ref "R9") (pin "1") (pinfunction "1_1") (pintype "passive"))
      (node (ref "TP25") (pin "1") (pinfunction "TP_1") (pintype "input"))
      (node (ref "U7") (pin "2") (pinfunction "U_HP_2") (pintype "bidirectional"))
    )
    (net (code "124") (name "Y_HALL_B") (class "Default")
      (node (ref "J20") (pin "4") (pinfunction "4_4") (pintype "bidirectional"))
      (node (ref "R8") (pin "1") (pinfunction "1_1") (pintype "passive"))
      (node (ref "TP24") (pin "1") (pinfunction "TP_1") (pintype "input"))
      (node (ref "U7") (pin "4") (pinfunction "V_HP_4") (pintype "bidirectional"))
    )
    (net (code "125") (name "Y_HALL_C") (class "Default")
      (node (ref "J20") (pin "2") (pinfunction "2_2") (pintype "bidirectional"))
      (node (ref "R10") (pin "1") (pinfunction "1_1") (pintype "passive"))
      (node (ref "TP23") (pin "1") (pinfunction "TP_1") (pintype "input"))
      (node (ref "U7") (pin "6") (pinfunction "W_HP_6") (pintype "bidirectional"))
    )
    (net (code "126") (name "Y_PHASE_A") (class "Default")
      (node (ref "J20") (pin "6") (pinfunction "6_6") (pintype "bidirectional"))
      (node (ref "J20") (pin "7") (pinfunction "7_7") (pintype "bidirectional"))
      (node (ref "U7") (pin "14") (pinfunction "U_14") (pintype "bidirectional"))
    )
    (net (code "127") (name "Y_PHASE_B") (class "Default")
      (node (ref "J20") (pin "8") (pinfunction "8_8") (pintype "bidirectional"))
      (node (ref "J20") (pin "9") (pinfunction "9_9") (pintype "bidirectional"))
      (node (ref "U7") (pin "13") (pinfunction "V_13") (pintype "bidirectional"))
    )
    (net (code "128") (name "Y_PHASE_C") (class "Default")
      (node (ref "J20") (pin "10") (pinfunction "10_10") (pintype "bidirectional"))
      (node (ref "J20") (pin "11") (pinfunction "11_11") (pintype "bidirectional"))
      (node (ref "U7") (pin "11") (pinfunction "W_11") (pintype "bidirectional"))
    )
    (net (code "129") (name "Z_HALL_A") (class "Default")
      (node (ref "J21") (pin "3") (pinfunction "3_3") (pintype "bidirectional"))
      (node (ref "R12") (pin "1") (pinfunction "1_1") (pintype "passive"))
      (node (ref "TP22") (pin "1") (pinfunction "TP_1") (pintype "input"))
      (node (ref "U12") (pin "2") (pinfunction "U_HP_2") (pintype "bidirectional"))
    )
    (net (code "130") (name "Z_HALL_B") (class "Default")
      (node (ref "J21") (pin "4") (pinfunction "4_4") (pintype "bidirectional"))
      (node (ref "R11") (pin "1") (pinfunction "1_1") (pintype "passive"))
      (node (ref "TP21") (pin "1") (pinfunction "TP_1") (pintype "input"))
      (node (ref "U12") (pin "4") (pinfunction "V_HP_4") (pintype "bidirectional"))
    )
    (net (code "131") (name "Z_HALL_C") (class "Default")
      (node (ref "J21") (pin "2") (pinfunction "2_2") (pintype "bidirectional"))
      (node (ref "R15") (pin "1") (pinfunction "1_1") (pintype "passive"))
      (node (ref "TP7") (pin "1") (pinfunction "TP_1") (pintype "input"))
      (node (ref "U12") (pin "6") (pinfunction "W_HP_6") (pintype "bidirectional"))
    )
    (net (code "132") (name "Z_PHASE_A") (class "Default")
      (node (ref "J21") (pin "6") (pinfunction "6_6") (pintype "bidirectional"))
      (node (ref "J21") (pin "7") (pinfunction "7_7") (pintype "bidirectional"))
      (node (ref "U12") (pin "14") (pinfunction "U_14") (pintype "bidirectional"))
    )
    (net (code "133") (name "Z_PHASE_B") (class "Default")
      (node (ref "J21") (pin "8") (pinfunction "8_8") (pintype "bidirectional"))
      (node (ref "J21") (pin "9") (pinfunction "9_9") (pintype "bidirectional"))
      (node (ref "U12") (pin "13") (pinfunction "V_13") (pintype "bidirectional"))
    )
    (net (code "134") (name "Z_PHASE_C") (class "Default")
      (node (ref "J21") (pin "10") (pinfunction "10_10") (pintype "bidirectional"))
      (node (ref "J21") (pin "11") (pinfunction "11_11") (pintype "bidirectional"))
      (node (ref "U12") (pin "11") (pinfunction "W_11") (pintype "bidirectional"))
    )
    (net (code "135") (name "unconnected-(J2-Pad5)") (class "Default")
      (node (ref "J2") (pin "5") (pinfunction "5_5") (pintype "passive"))
    )
    (net (code "136") (name "unconnected-(J2-Pad7)") (class "Default")
      (node (ref "J2") (pin "7") (pinfunction "7_7") (pintype "passive"))
    )
    (net (code "137") (name "unconnected-(J2-Pad8)") (class "Default")
      (node (ref "J2") (pin "8") (pinfunction "8_8") (pintype "passive"))
    )
    (net (code "138") (name "unconnected-(J2-Pad9)") (class "Default")
      (node (ref "J2") (pin "9") (pinfunction "9_9") (pintype "passive"))
    )
    (net (code "139") (name "unconnected-(J2-Pad10)") (class "Default")
      (node (ref "J2") (pin "10") (pinfunction "10_10") (pintype "passive"))
    )
    (net (code "140") (name "unconnected-(J2-Pad12)") (class "Default")
      (node (ref "J2") (pin "12") (pinfunction "12_12") (pintype "passive"))
    )
    (net (code "141") (name "unconnected-(MH5-MOUNT-Pad1)") (class "Default")
      (node (ref "MH5") (pin "1") (pinfunction "MOUNT_1") (pintype "no_connect"))
    )
    (net (code "142") (name "unconnected-(MH6-MOUNT-Pad1)") (class "Default")
      (node (ref "MH6") (pin "1") (pinfunction "MOUNT_1") (pintype "no_connect"))
    )
    (net (code "143") (name "unconnected-(MH7-MOUNT-Pad1)") (class "Default")
      (node (ref "MH7") (pin "1") (pinfunction "MOUNT_1") (pintype "no_connect"))
    )
    (net (code "144") (name "unconnected-(MH8-MOUNT-Pad1)") (class "Default")
      (node (ref "MH8") (pin "1") (pinfunction "MOUNT_1") (pintype "no_connect"))
    )
    (net (code "145") (name "unconnected-(U2-BUSY-Pad13)") (class "Default")
      (node (ref "U2") (pin "13") (pinfunction "BUSY_13") (pintype "output"))
    )
    (net (code "146") (name "unconnected-(U3-BUSY-Pad13)") (class "Default")
      (node (ref "U3") (pin "13") (pinfunction "BUSY_13") (pintype "output"))
    )
    (net (code "147") (name "unconnected-(U4-BUSY-Pad13)") (class "Default")
      (node (ref "U4") (pin "13") (pinfunction "BUSY_13") (pintype "output"))
    )
    (net (code "148") (name "unconnected-(U7-CMTMOD-Pad20)") (class "Default")
      (node (ref "U7") (pin "20") (pinfunction "CMTMOD_20") (pintype "bidirectional"))
    )
    (net (code "149") (name "unconnected-(U7-DAA-Pad1)") (class "Default")
      (node (ref "U7") (pin "1") (pinfunction "DAA_1") (pintype "bidirectional"))
    )
    (net (code "150") (name "unconnected-(U10-CMTMOD-Pad20)") (class "Default")
      (node (ref "U10") (pin "20") (pinfunction "CMTMOD_20") (pintype "bidirectional"))
    )
    (net (code "151") (name "unconnected-(U10-DAA-Pad1)") (class "Default")
      (node (ref "U10") (pin "1") (pinfunction "DAA_1") (pintype "bidirectional"))
    )
    (net (code "152") (name "unconnected-(U12-CMTMOD-Pad20)") (class "Default")
      (node (ref "U12") (pin "20") (pinfunction "CMTMOD_20") (pintype "bidirectional"))
    )
    (net (code "153") (name "unconnected-(U12-DAA-Pad1)") (class "Default")
      (node (ref "U12") (pin "1") (pinfunction "DAA_1") (pintype "bidirectional"))
    )
    (net (code "154") (name "unconnected-(U13-BUSY-Pad13)") (class "Default")
      (node (ref "U13") (pin "13") (pinfunction "BUSY_13") (pintype "output"))
    )
    (net (code "155") (name "unconnected-(U25-BUSY-Pad13)") (class "Default")
      (node (ref "U25") (pin "13") (pinfunction "BUSY_13") (pintype "output"))
    )
    (net (code "156") (name "unconnected-(U27-BUSY-Pad13)") (class "Default")
      (node (ref "U27") (pin "13") (pinfunction "BUSY_13") (pintype "output"))
    )
    (net (code "157") (name "~{CS}_CUR_SENSE_MAG") (class "Default")
      (node (ref "J2") (pin "11") (pinfunction "11_11") (pintype "passive"))
      (node (ref "U2") (pin "15") (pinfunction "~{CS}_15") (pintype "input"))
    )
    (net (code "158") (name "~{CS}_CUR_SENSE_RW") (class "Default")
      (node (ref "J2") (pin "13") (pinfunction "13_13") (pintype "passive"))
      (node (ref "U3") (pin "15") (pinfunction "~{CS}_15") (pintype "input"))
    )
    (net (code "159") (name "~{CS}_SUN_X+") (class "Default")
      (node (ref "J2") (pin "16") (pinfunction "16_16") (pintype "passive"))
      (node (ref "U25") (pin "15") (pinfunction "~{CS}_15") (pintype "input"))
    )
    (net (code "160") (name "~{CS}_SUN_X-") (class "Default")
      (node (ref "J2") (pin "14") (pinfunction "14_14") (pintype "passive"))
      (node (ref "U13") (pin "15") (pinfunction "~{CS}_15") (pintype "input"))
    )
    (net (code "161") (name "~{CS}_SUN_Y+") (class "Default")
      (node (ref "J2") (pin "3") (pinfunction "3_3") (pintype "passive"))
      (node (ref "U27") (pin "15") (pinfunction "~{CS}_15") (pintype "input"))
    )
    (net (code "162") (name "~{CS}_SUN_Y-") (class "Default")
      (node (ref "J2") (pin "1") (pinfunction "1_1") (pintype "passive"))
      (node (ref "U4") (pin "15") (pinfunction "~{CS}_15") (pintype "input"))
    )
  )
)
